# PCB_KioskMB_r3_3-04.net
KiCad netlist of a schematic drawn in EAGLE
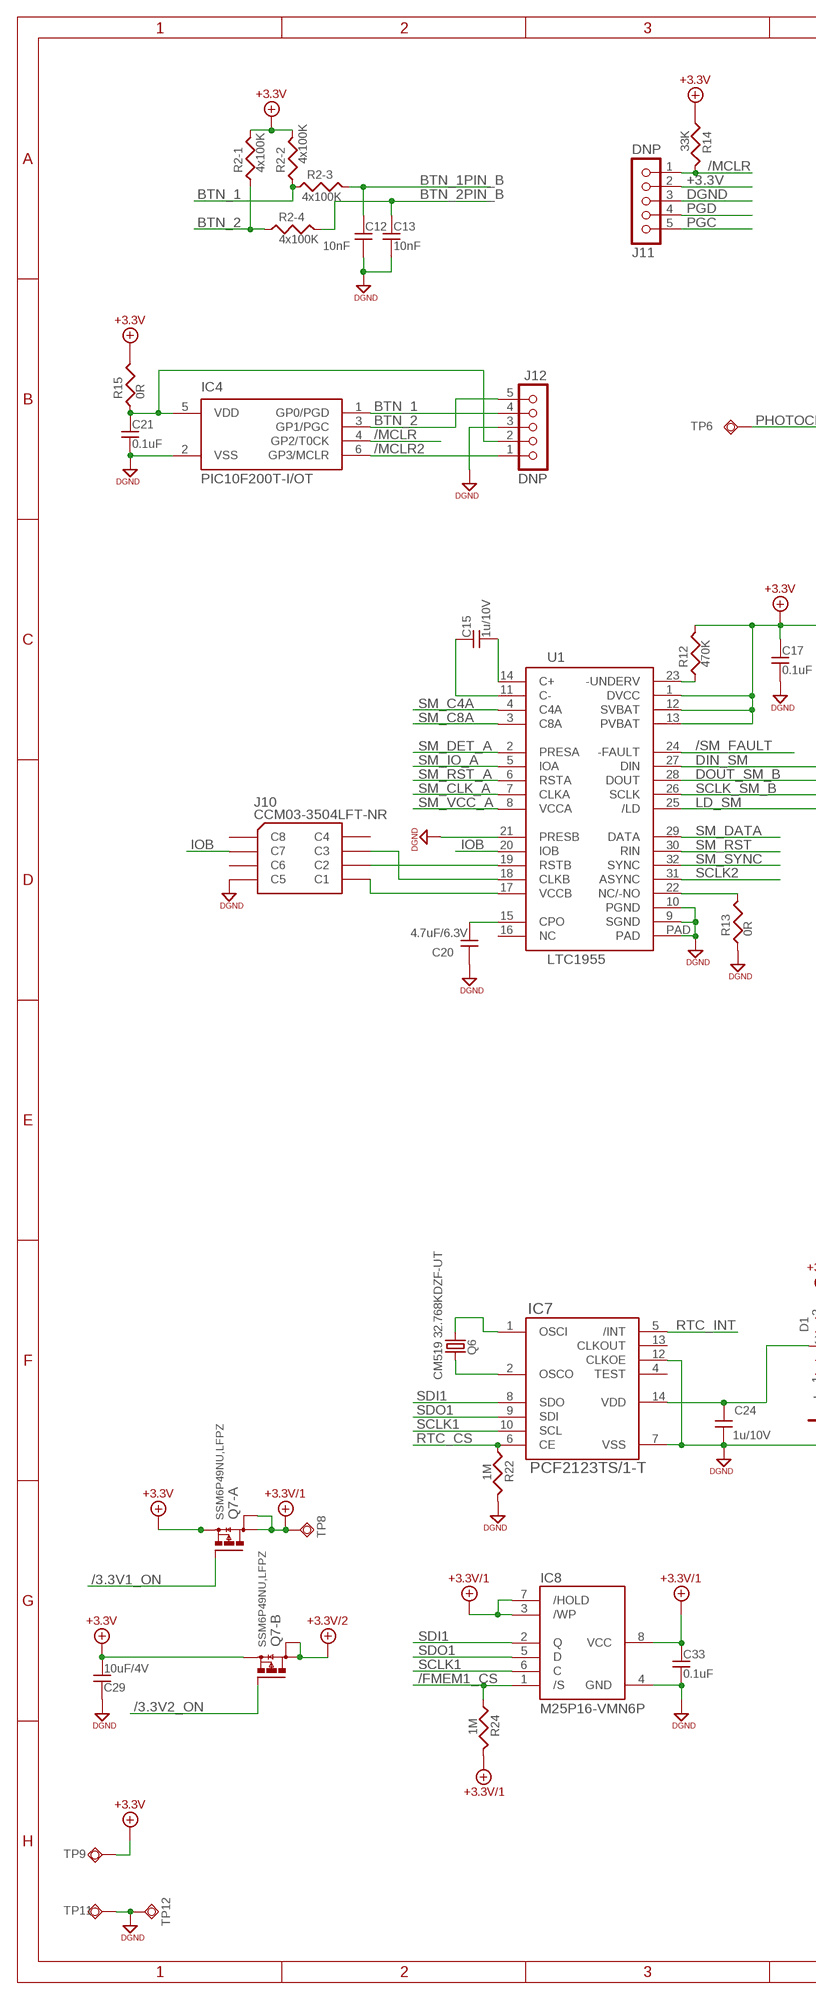
[diagram p0: schematic, sheet 1, part 1 of 2]
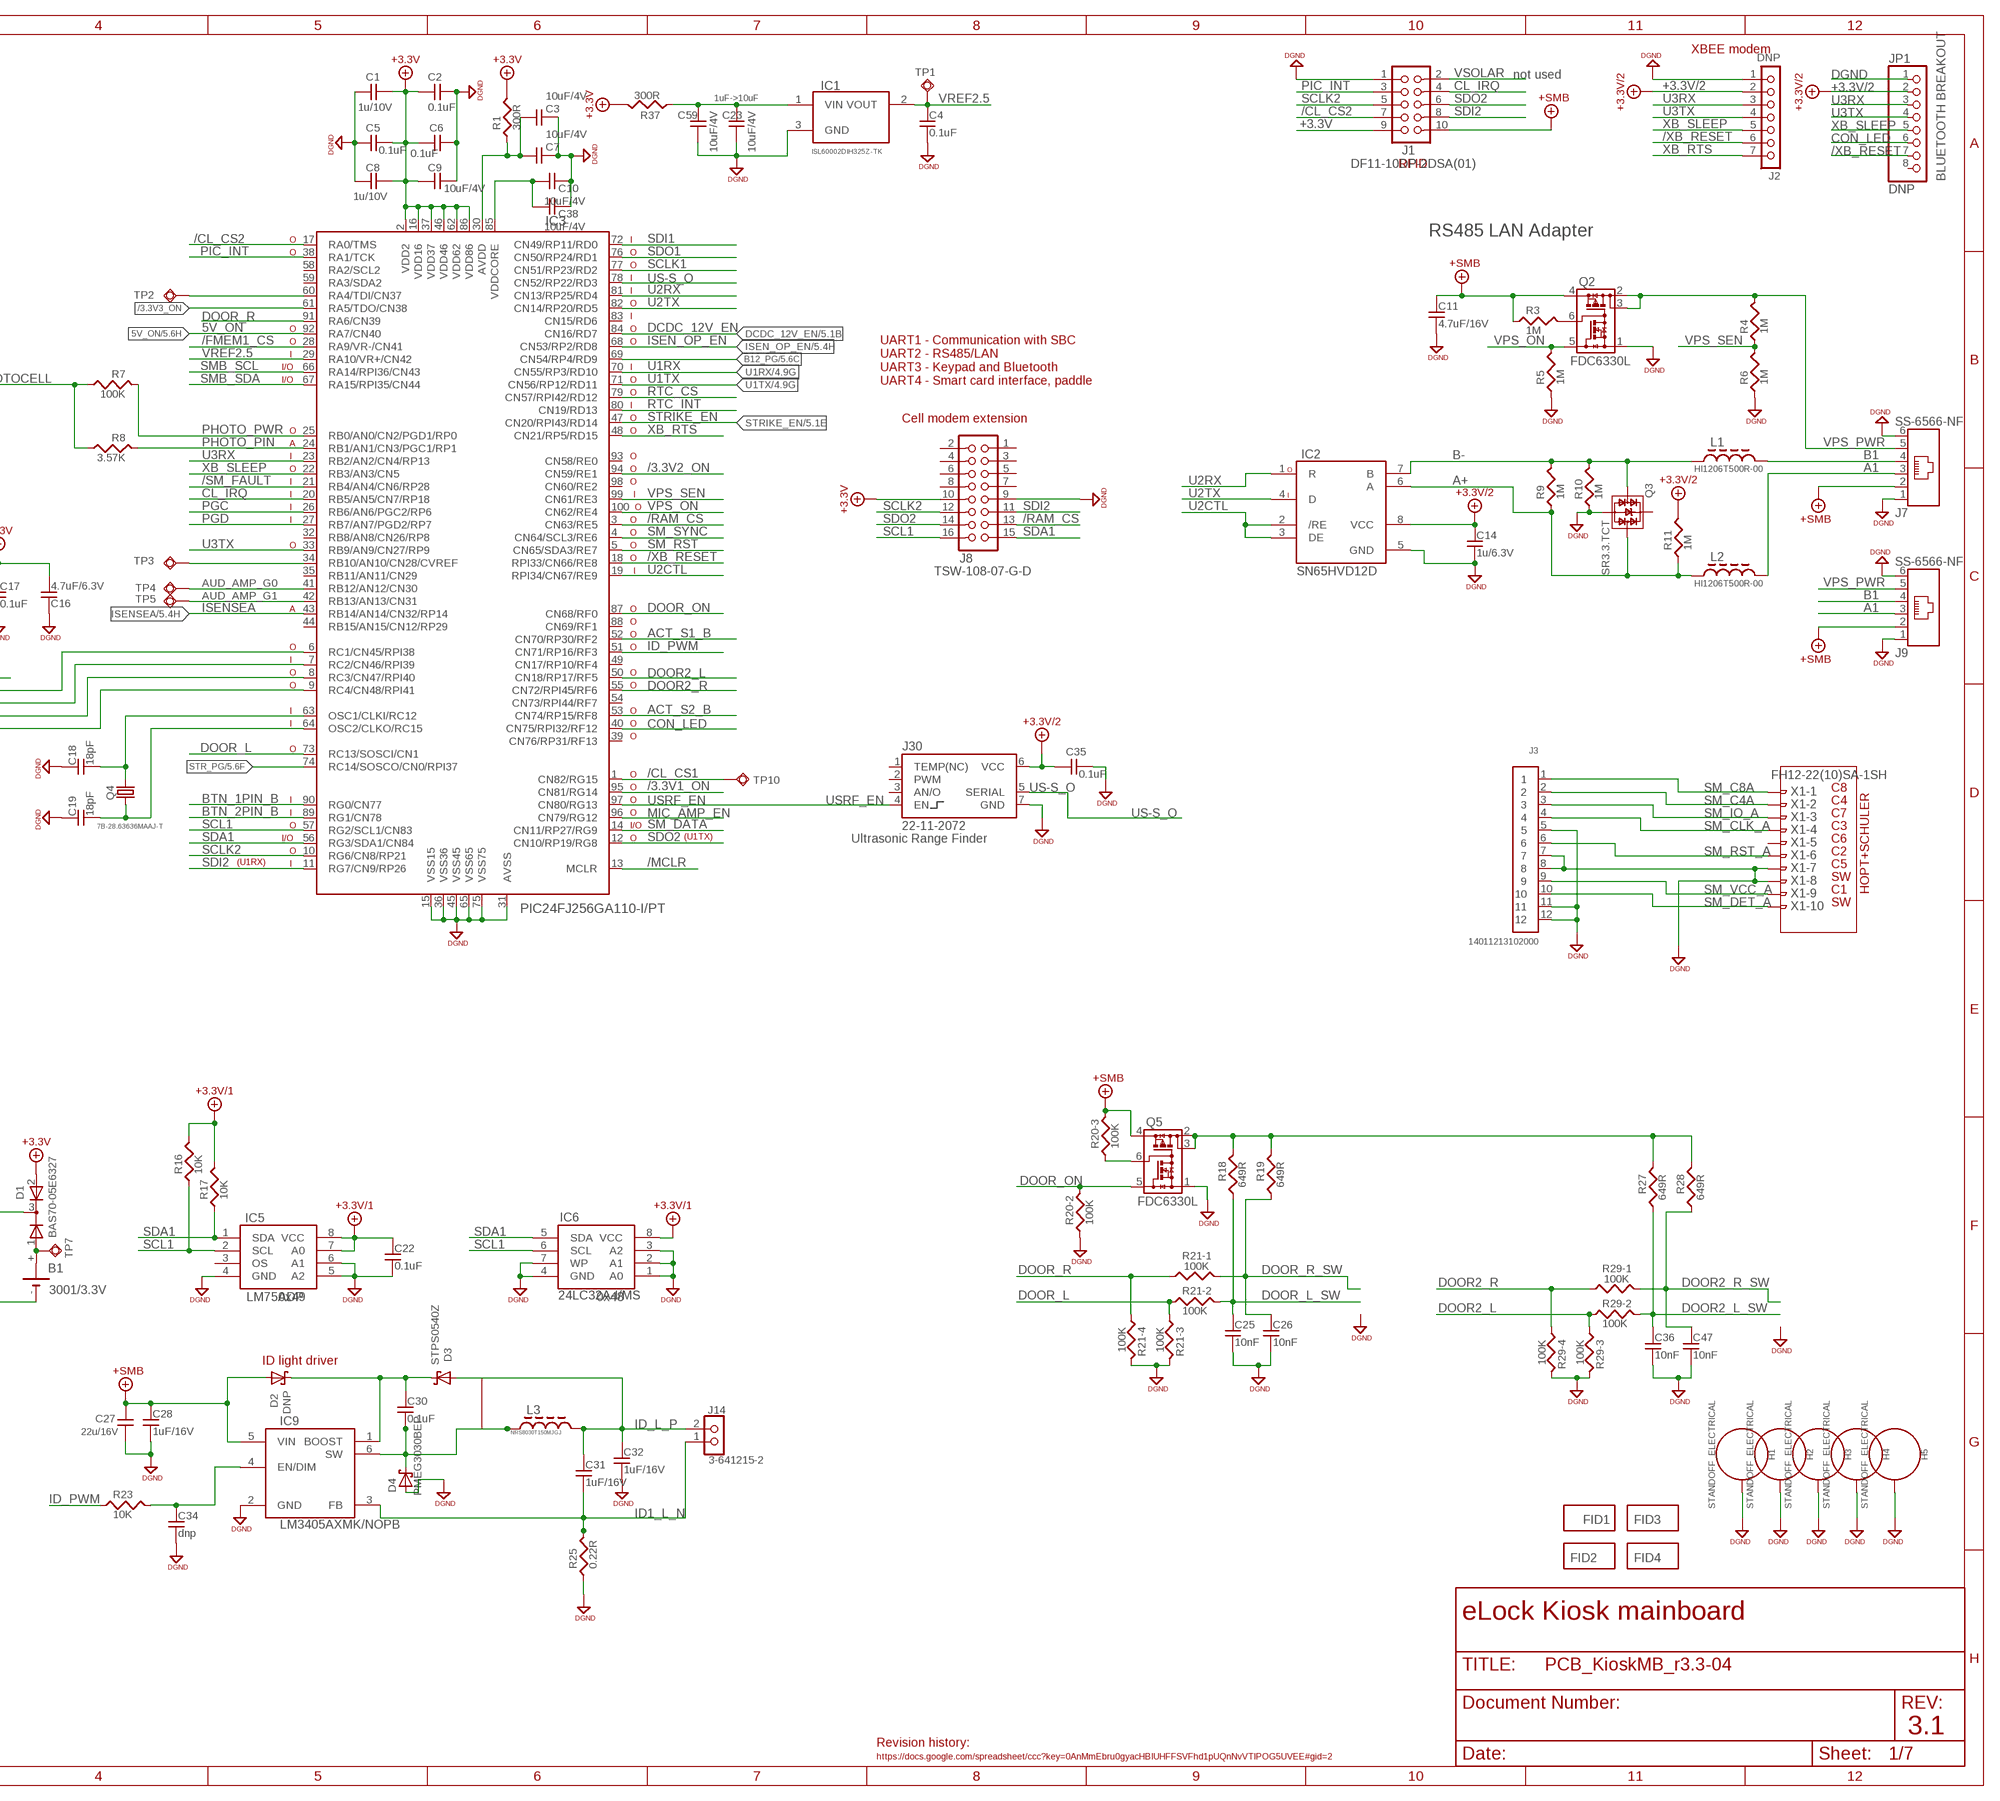
[diagram p1: schematic, sheet 1, part 2 of 2]
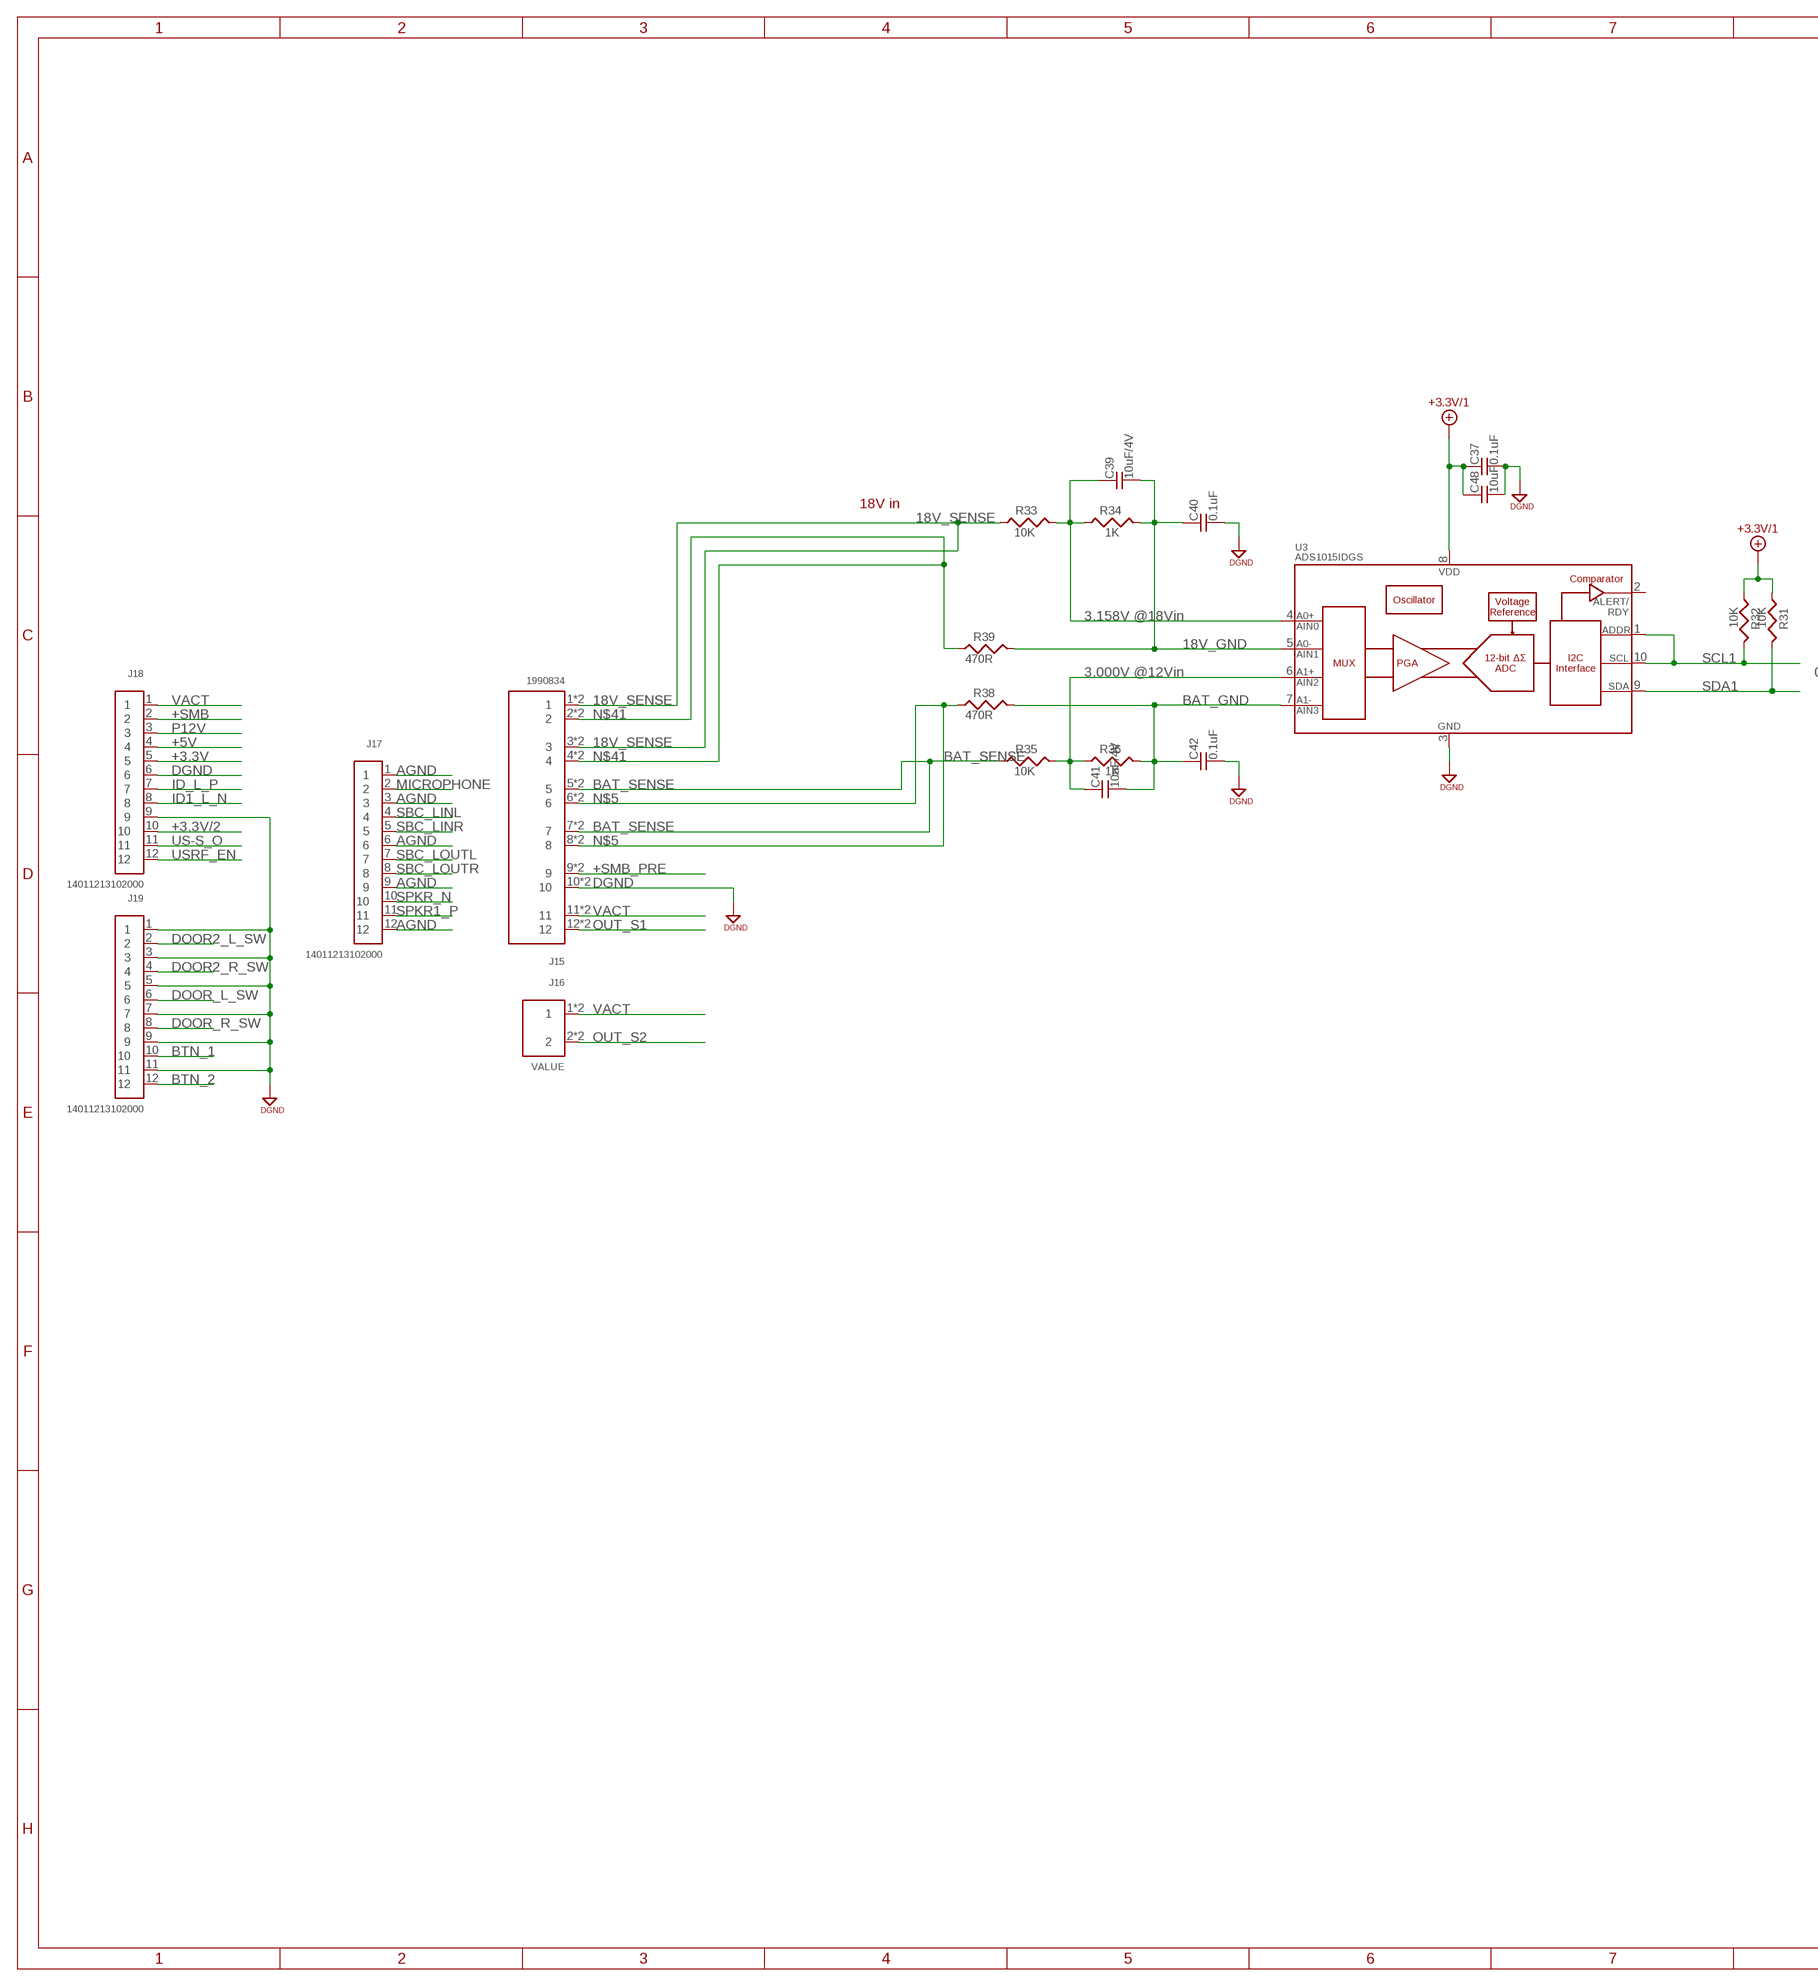
[diagram p2: schematic, sheet 2, part 1 of 2]
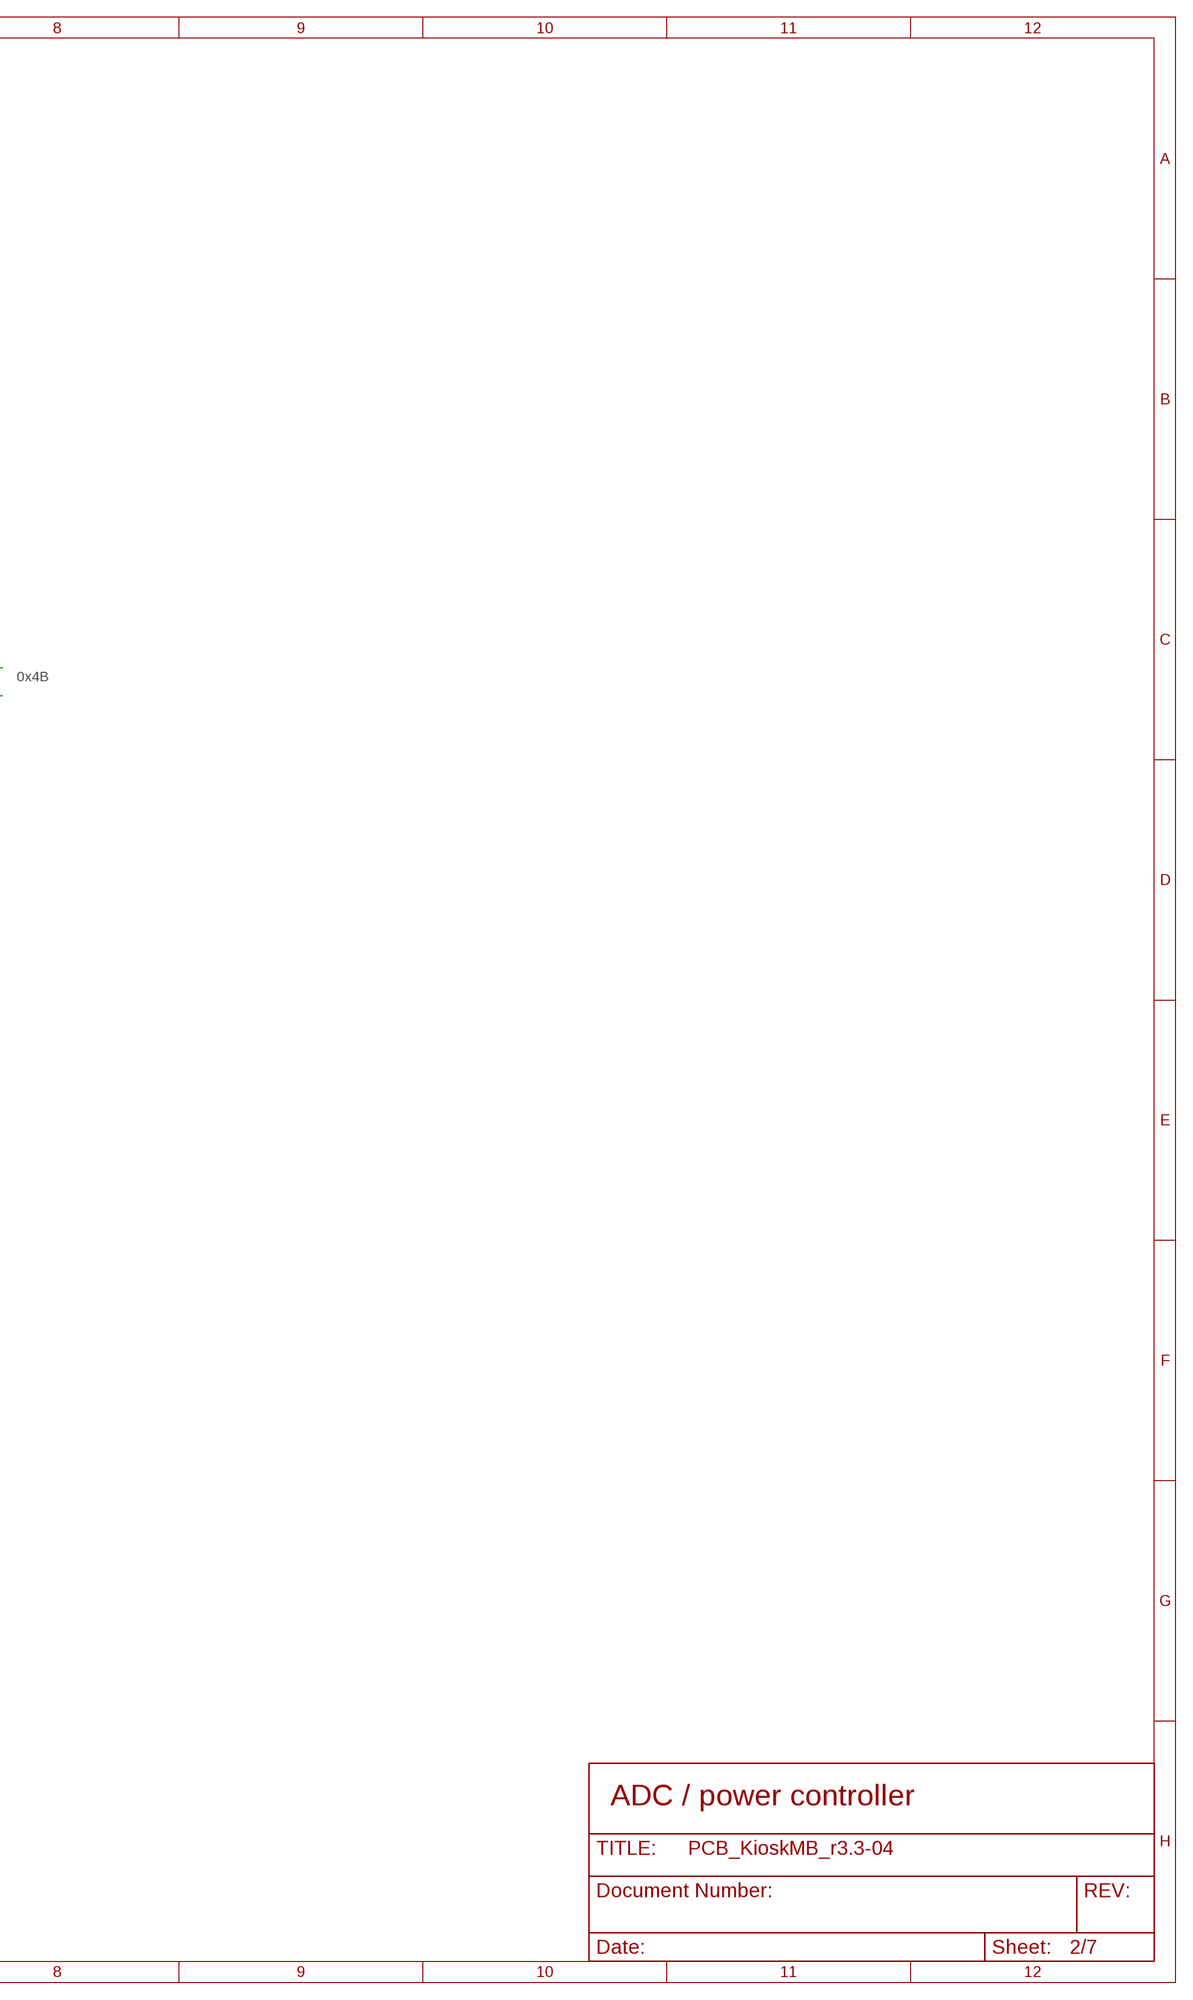
[diagram p3: schematic, sheet 2, part 2 of 2]
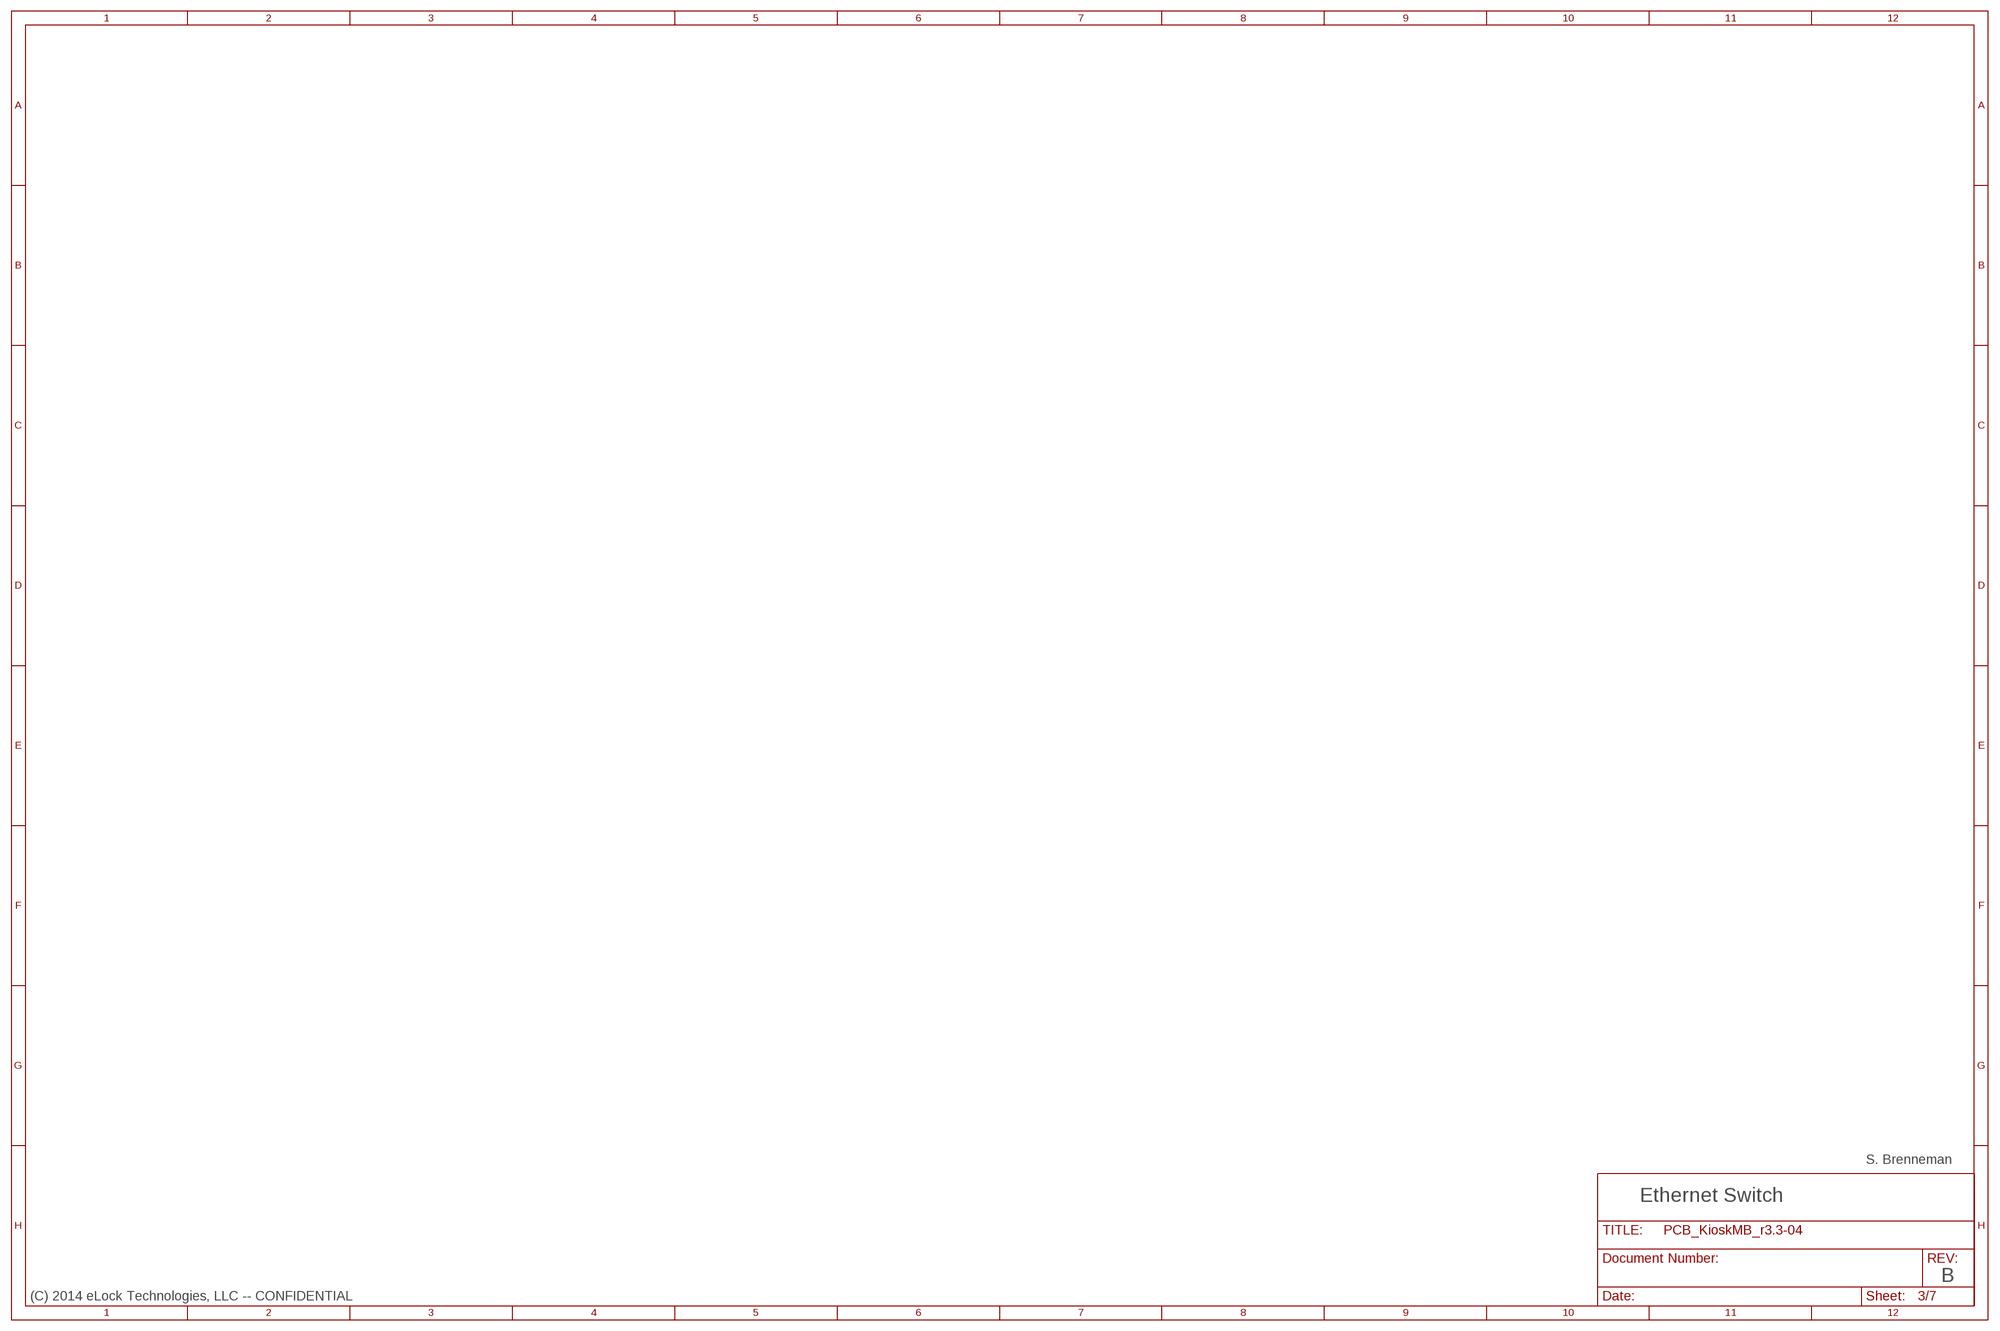
[diagram p4: schematic, sheet 3]
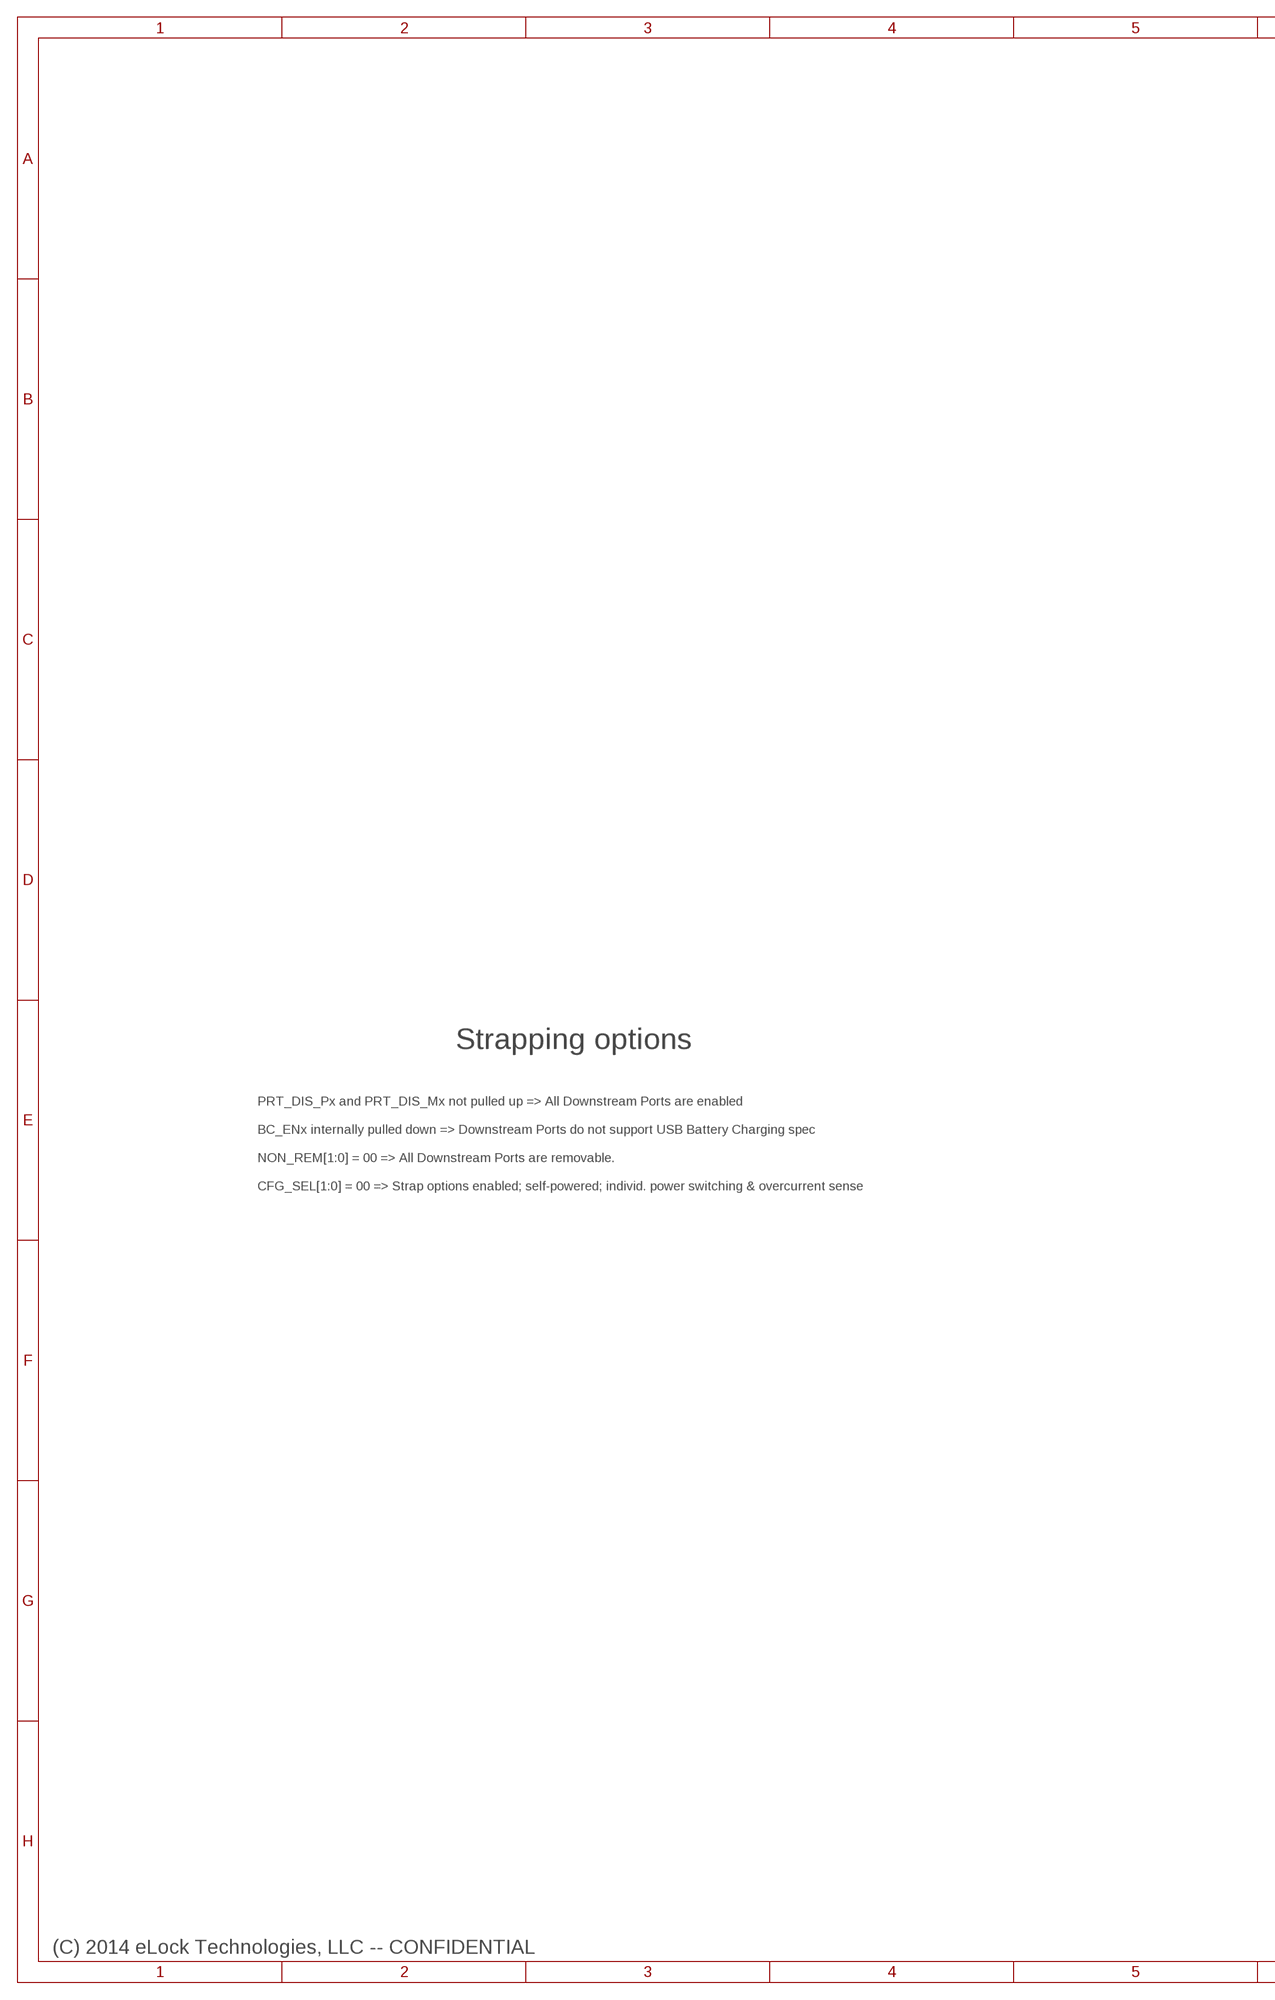
[diagram p5: schematic, sheet 4, part 1 of 2]
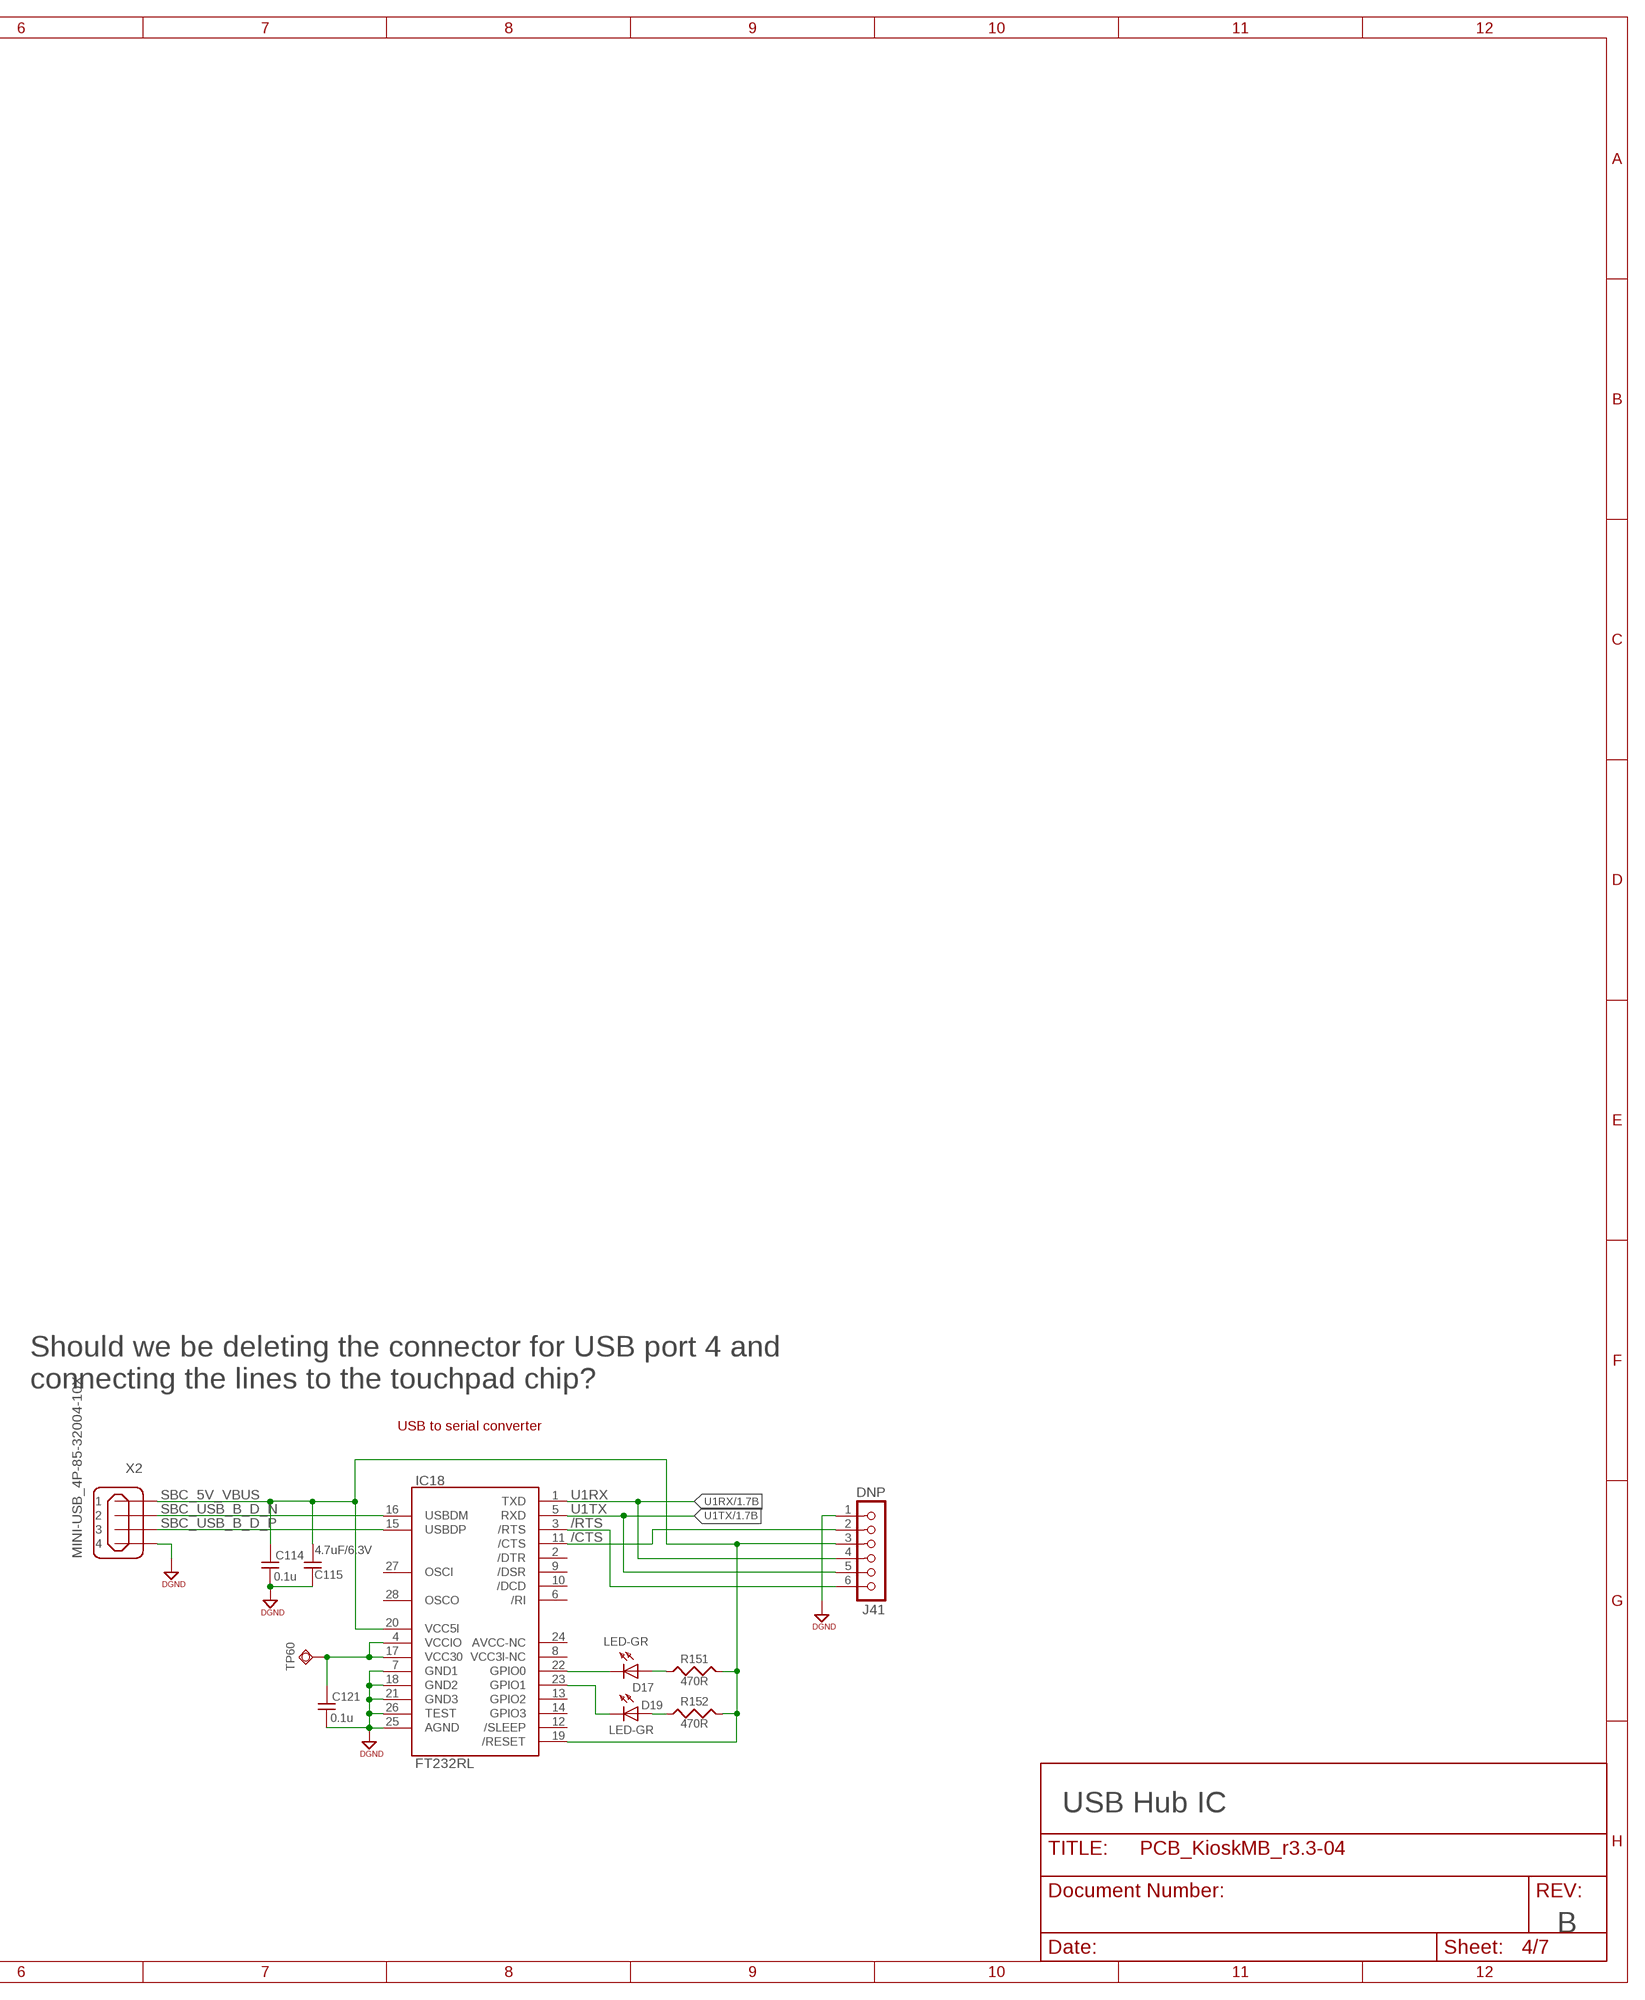
[diagram p6: schematic, sheet 4, part 2 of 2]
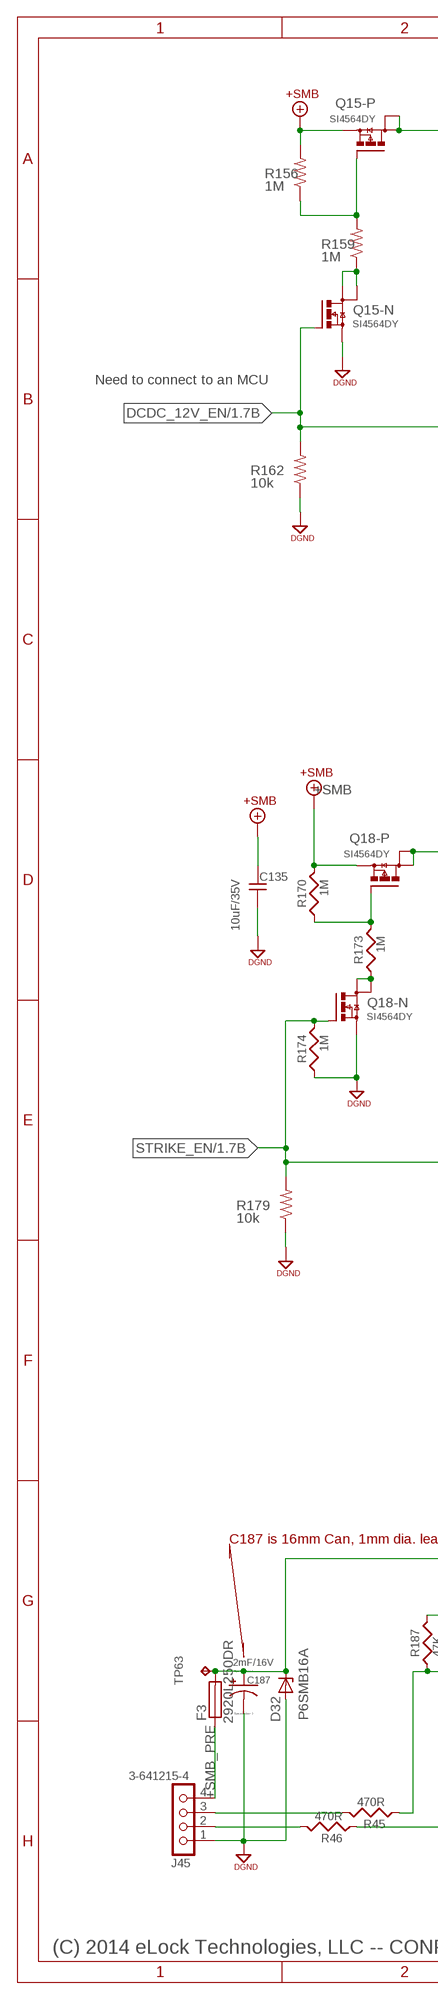
[diagram p7: schematic, sheet 5, part 1 of 2]
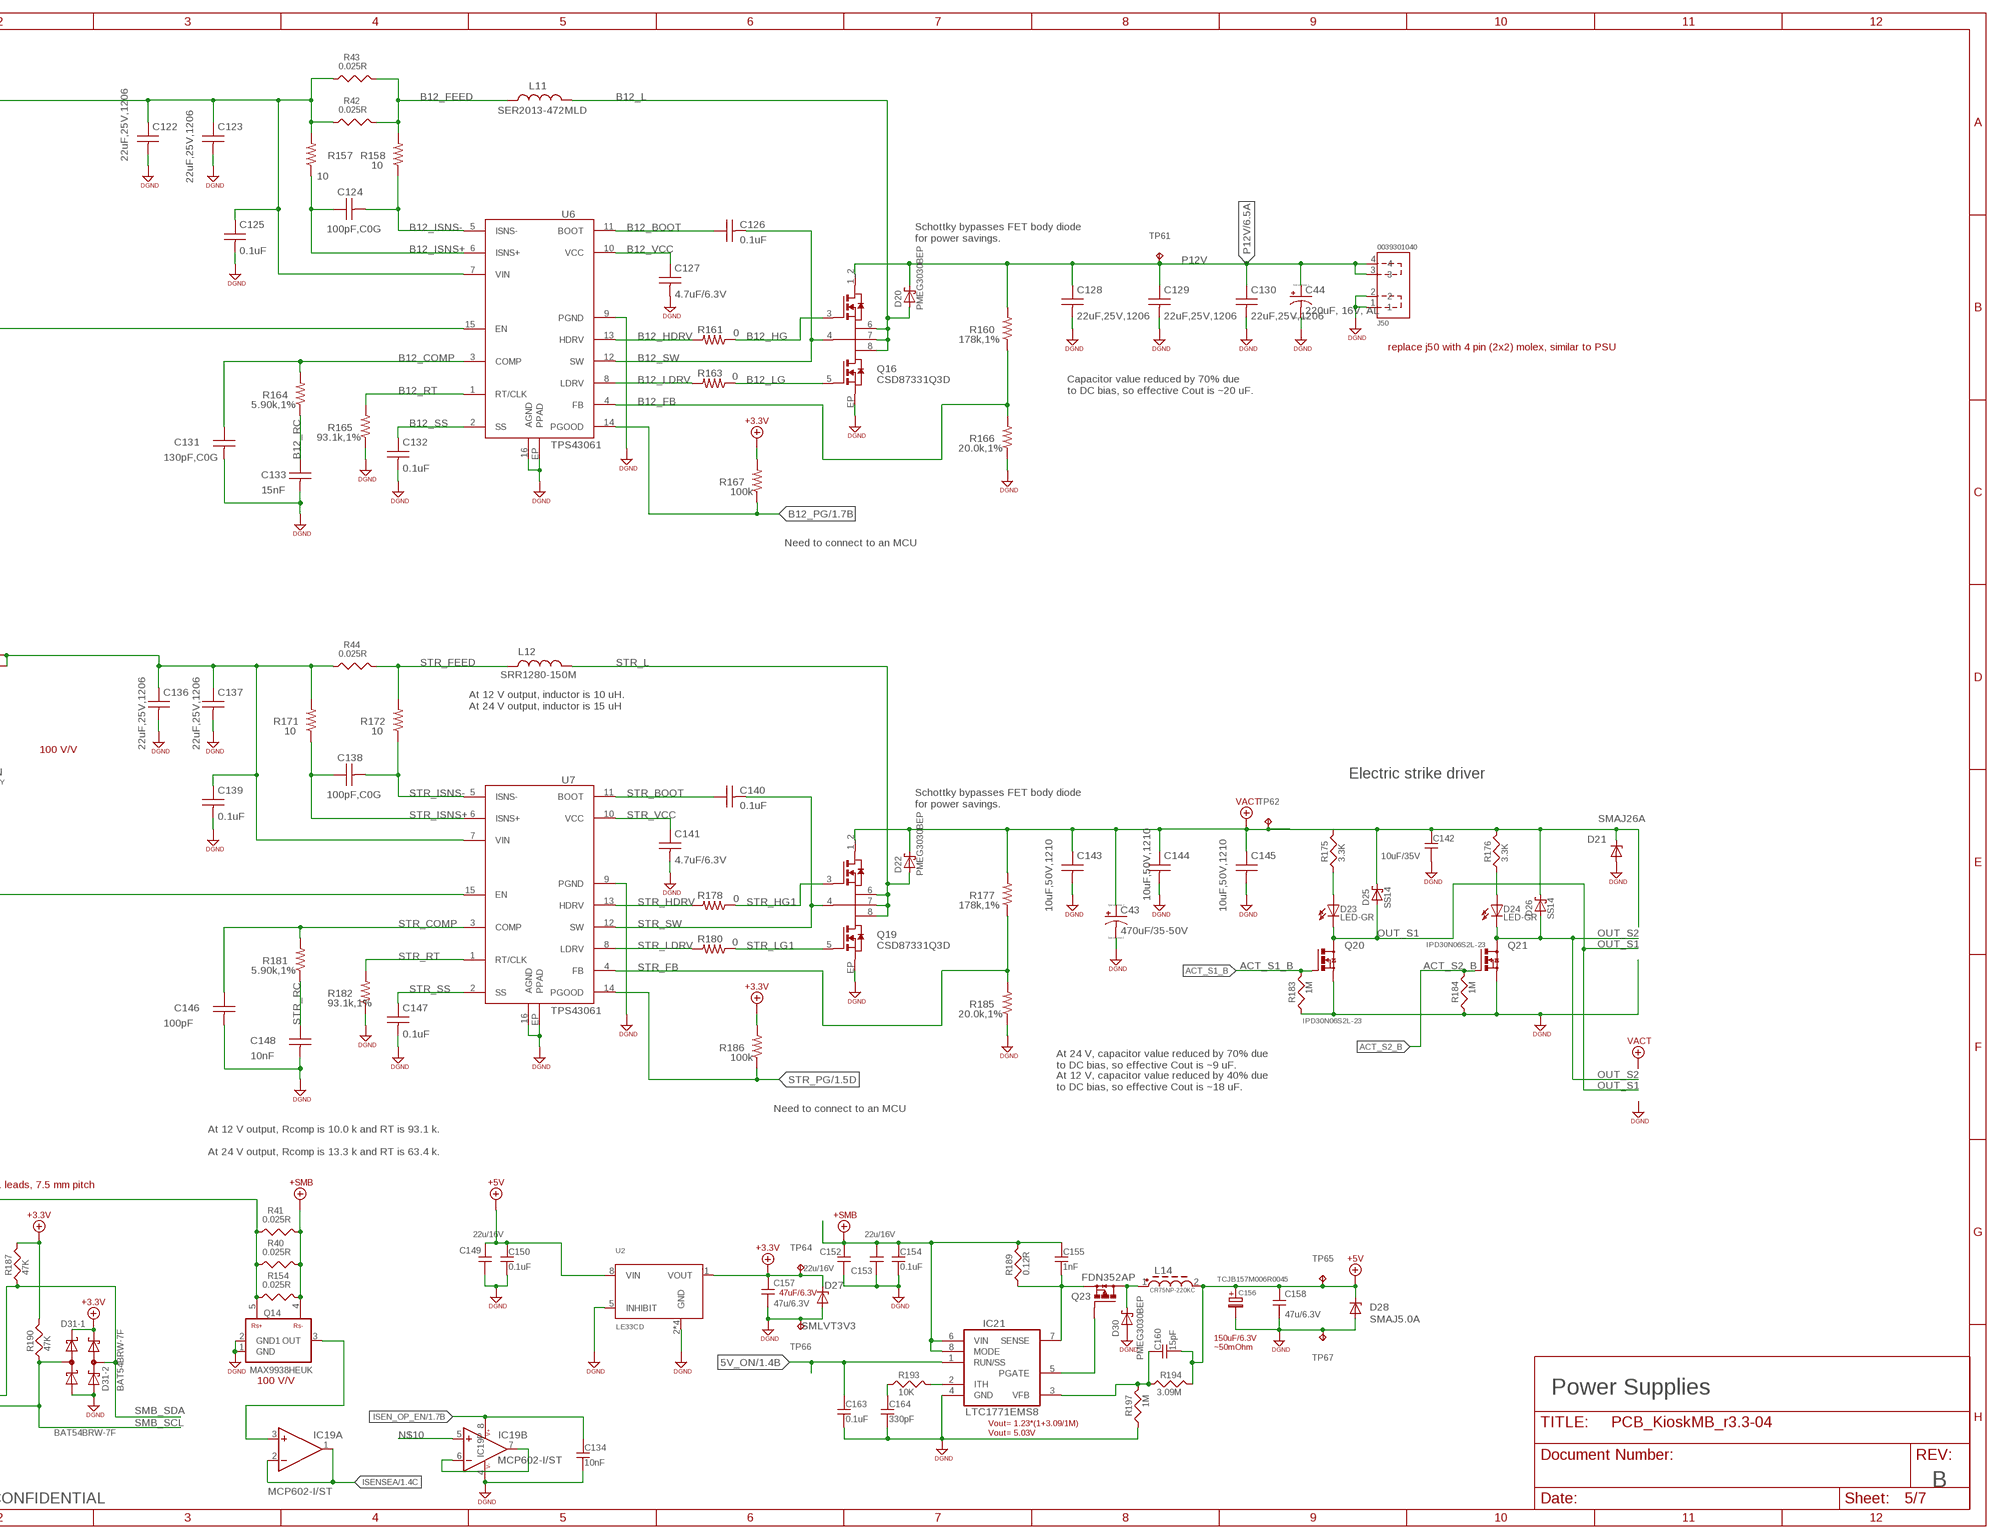
[diagram p8: schematic, sheet 5, part 2 of 2]
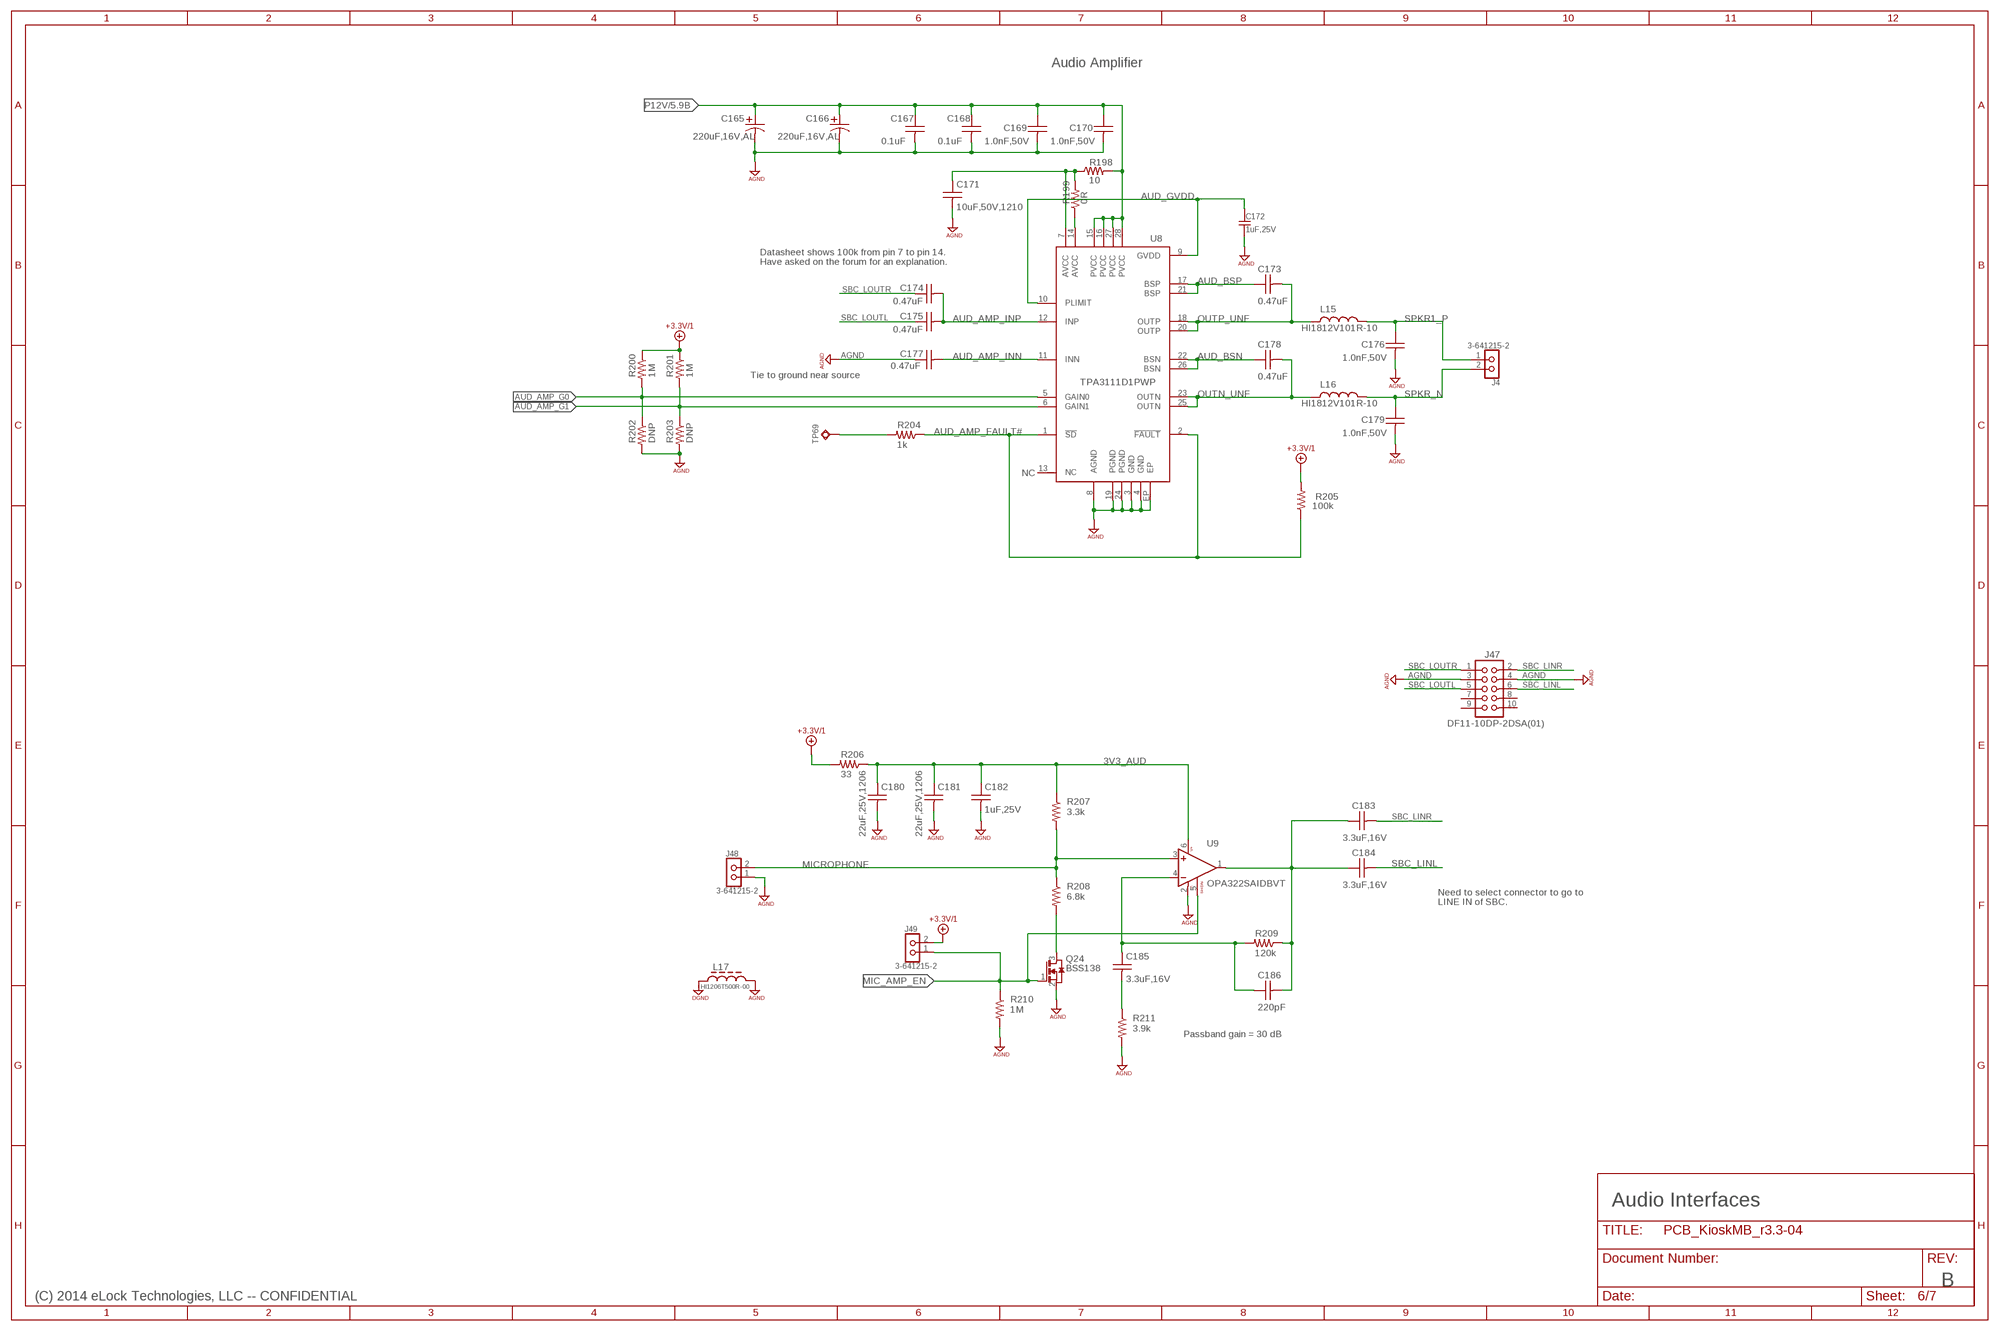
[diagram p9: schematic, sheet 6]
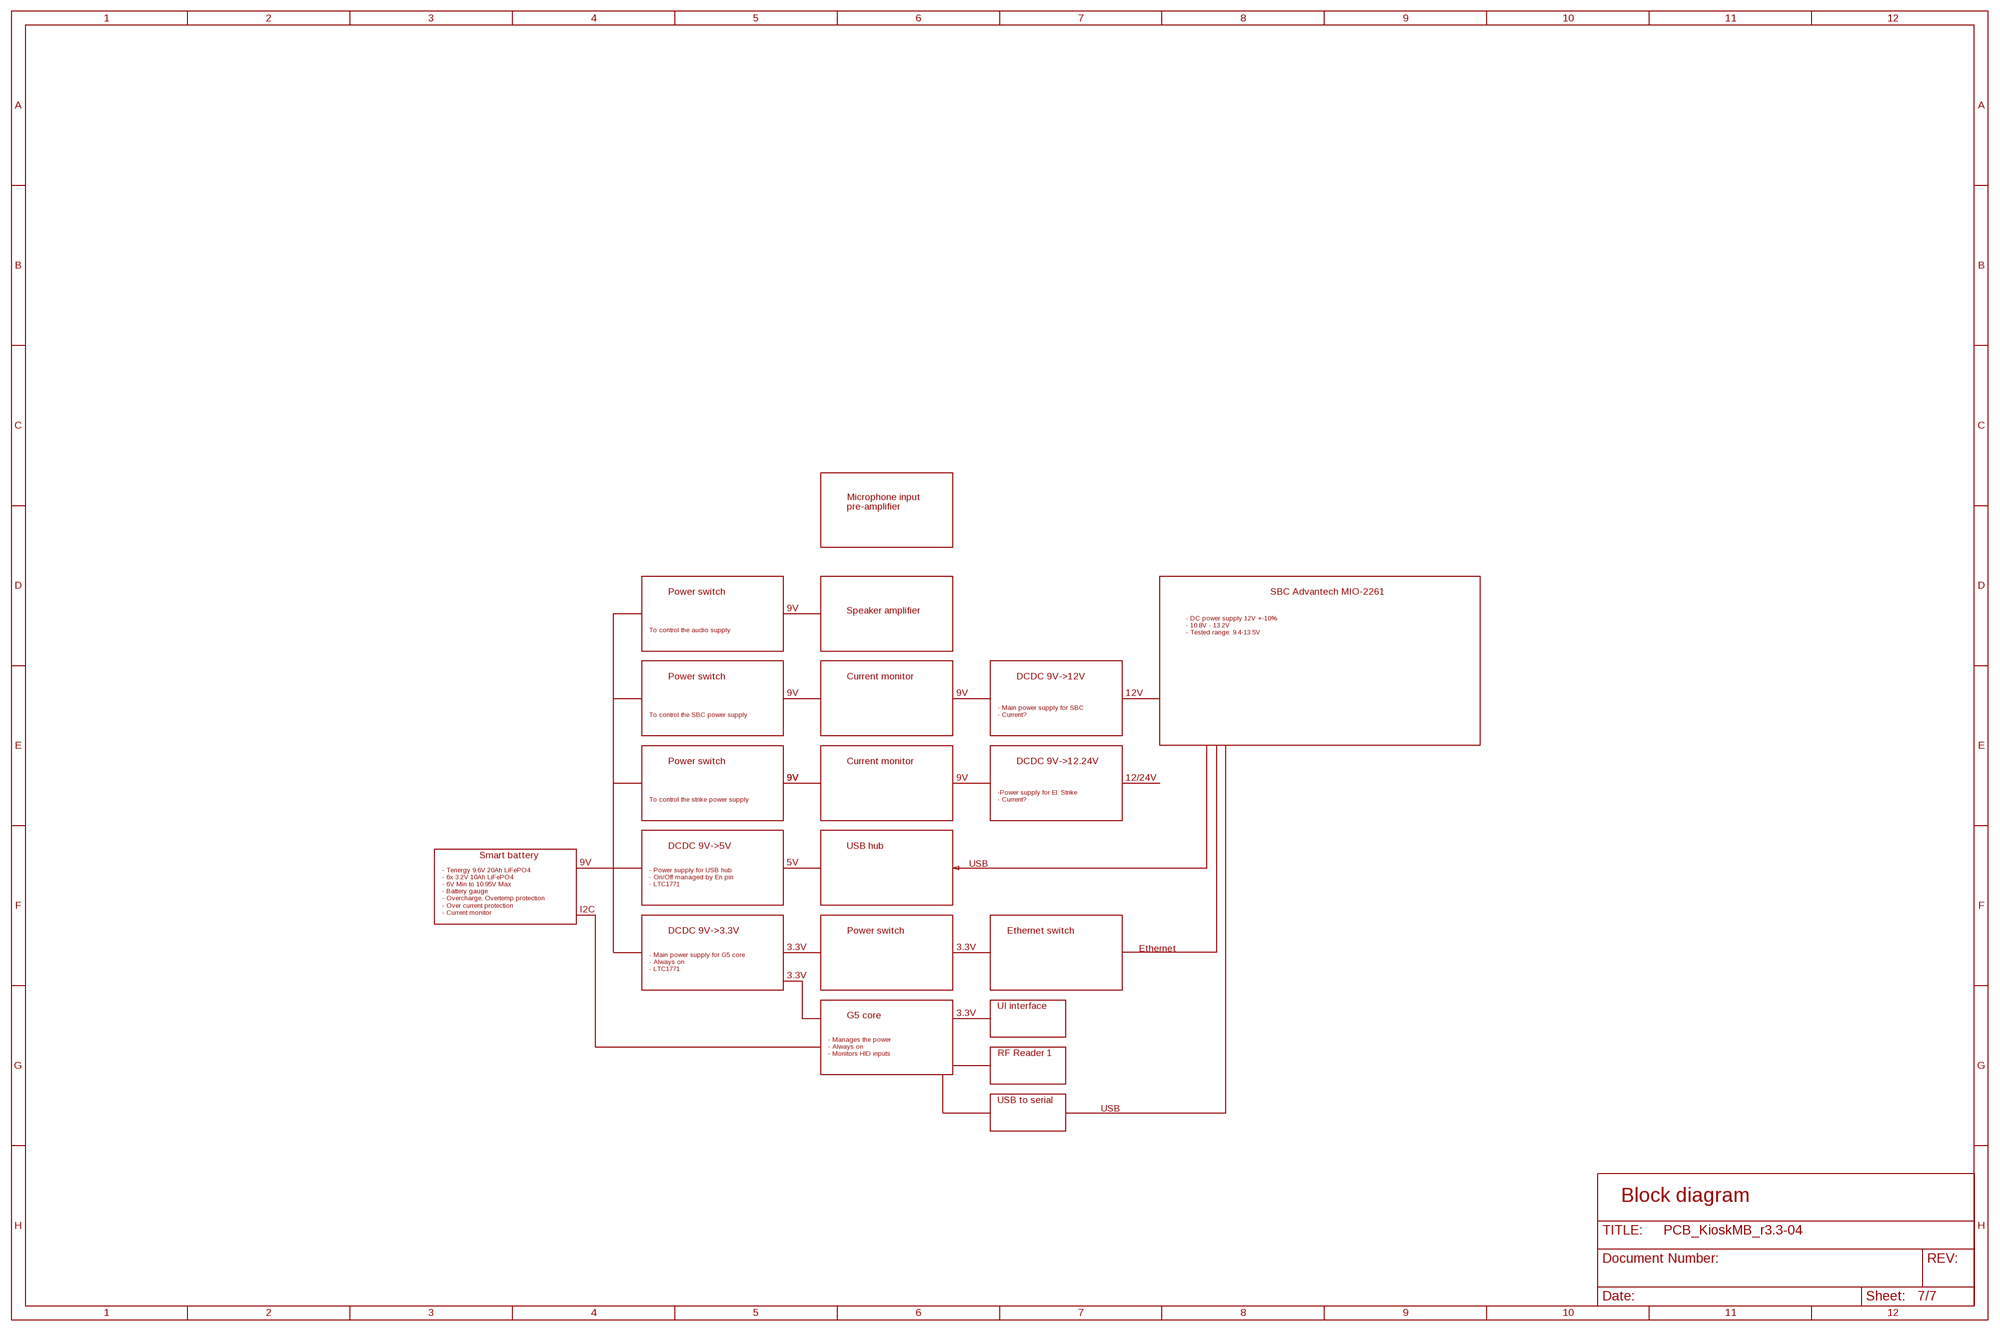
[diagram p10: schematic, sheet 7]

(export (version "E")
  (design (tool "Eeschema 10.0.6"))
  (components
    (comp (ref "C37")
      (value "0.1uF")
      (footprint "eagle-import:0603")
      (libsource (lib "eagle-import") (part "C-0603"))
    )
    (comp (ref "C39")
      (value "10uF/4V")
      (footprint "eagle-import:0603")
      (libsource (lib "eagle-import") (part "C-0603"))
    )
    (comp (ref "C40")
      (value "0.1uF")
      (footprint "eagle-import:0603")
      (libsource (lib "eagle-import") (part "C-0603"))
    )
    (comp (ref "C41")
      (value "10uF/4V")
      (footprint "eagle-import:0603")
      (libsource (lib "eagle-import") (part "C-0603"))
    )
    (comp (ref "C42")
      (value "0.1uF")
      (footprint "eagle-import:0603")
      (libsource (lib "eagle-import") (part "C-0603"))
    )
    (comp (ref "C48")
      (value "10uF")
      (footprint "eagle-import:0603")
      (libsource (lib "eagle-import") (part "C-0603"))
    )
    (comp (ref "J15")
      (value "1990834")
      (footprint "eagle-import:1990834")
      (libsource (lib "eagle-import") (part "1990834"))
    )
    (comp (ref "J16")
      (value "1990737")
      (footprint "eagle-import:1990737")
      (libsource (lib "eagle-import") (part "1990737"))
    )
    (comp (ref "J17")
      (value "14011213102000")
      (footprint "eagle-import:14011213102000")
      (libsource (lib "eagle-import") (part "14011213102000"))
    )
    (comp (ref "J18")
      (value "14011213102000")
      (footprint "eagle-import:14011213102000")
      (libsource (lib "eagle-import") (part "14011213102000"))
    )
    (comp (ref "J19")
      (value "14011213102000")
      (footprint "eagle-import:14011213102000")
      (libsource (lib "eagle-import") (part "14011213102000"))
    )
    (comp (ref "R31")
      (value "10K")
      (footprint "eagle-import:0603")
      (libsource (lib "eagle-import") (part "R-0603"))
    )
    (comp (ref "R32")
      (value "10K")
      (footprint "eagle-import:0603")
      (libsource (lib "eagle-import") (part "R-0603"))
    )
    (comp (ref "R33")
      (value "10K")
      (footprint "eagle-import:0603")
      (libsource (lib "eagle-import") (part "R-0603"))
    )
    (comp (ref "R34")
      (value "1K")
      (footprint "eagle-import:0603")
      (libsource (lib "eagle-import") (part "R-0603"))
    )
    (comp (ref "R35")
      (value "10K")
      (footprint "eagle-import:0603")
      (libsource (lib "eagle-import") (part "R-0603"))
    )
    (comp (ref "R36")
      (value "1K")
      (footprint "eagle-import:0603")
      (libsource (lib "eagle-import") (part "R-0603"))
    )
    (comp (ref "R38")
      (value "470R")
      (footprint "eagle-import:0603")
      (libsource (lib "eagle-import") (part "R-0603"))
    )
    (comp (ref "R39")
      (value "470R")
      (footprint "eagle-import:0603")
      (libsource (lib "eagle-import") (part "R-0603"))
    )
    (comp (ref "U3")
      (value "ADS1015IDGS")
      (footprint "eagle-import:MSOP10")
      (libsource (lib "eagle-import") (part "ADS1015"))
    )
    (comp (ref "B1")
      (value "3001/3.3V")
      (footprint "eagle-import:3001")
      (libsource (lib "eagle-import") (part "3001"))
    )
    (comp (ref "C1")
      (value "1u/10V")
      (footprint "eagle-import:0603")
      (libsource (lib "eagle-import") (part "C-0603"))
    )
    (comp (ref "C2")
      (value "0.1uF")
      (footprint "eagle-import:0603")
      (libsource (lib "eagle-import") (part "C-0603"))
    )
    (comp (ref "C3")
      (value "10uF/4V")
      (footprint "eagle-import:0603")
      (libsource (lib "eagle-import") (part "C-0603"))
    )
    (comp (ref "C4")
      (value "0.1uF")
      (footprint "eagle-import:0603")
      (libsource (lib "eagle-import") (part "C-0603"))
    )
    (comp (ref "C5")
      (value "0.1uF")
      (footprint "eagle-import:0603")
      (libsource (lib "eagle-import") (part "C-0603"))
    )
    (comp (ref "C6")
      (value "0.1uF")
      (footprint "eagle-import:0603")
      (libsource (lib "eagle-import") (part "C-0603"))
    )
    (comp (ref "C7")
      (value "10uF/4V")
      (footprint "eagle-import:0603")
      (libsource (lib "eagle-import") (part "C-0603"))
    )
    (comp (ref "C8")
      (value "1u/10V")
      (footprint "eagle-import:0603")
      (libsource (lib "eagle-import") (part "C-0603"))
    )
    (comp (ref "C9")
      (value "10uF/4V")
      (footprint "eagle-import:0603")
      (libsource (lib "eagle-import") (part "C-0603"))
    )
    (comp (ref "C10")
      (value "10uF/4V")
      (footprint "eagle-import:0603")
      (libsource (lib "eagle-import") (part "C-0603"))
    )
    (comp (ref "C11")
      (value "4.7uF/16V")
      (footprint "eagle-import:0805")
      (libsource (lib "eagle-import") (part "C-0805"))
    )
    (comp (ref "C12")
      (value "10nF")
      (footprint "eagle-import:0603")
      (libsource (lib "eagle-import") (part "C-0603"))
    )
    (comp (ref "C13")
      (value "10nF")
      (footprint "eagle-import:0603")
      (libsource (lib "eagle-import") (part "C-0603"))
    )
    (comp (ref "C14")
      (value "1u/6.3V")
      (footprint "eagle-import:0603")
      (libsource (lib "eagle-import") (part "C-0603"))
    )
    (comp (ref "C15")
      (value "1u/10V")
      (footprint "eagle-import:0603")
      (libsource (lib "eagle-import") (part "C-0603"))
    )
    (comp (ref "C16")
      (value "4.7uF/6.3V")
      (footprint "eagle-import:0603")
      (libsource (lib "eagle-import") (part "C-0603"))
    )
    (comp (ref "C17")
      (value "0.1uF")
      (footprint "eagle-import:0603")
      (libsource (lib "eagle-import") (part "C-0603"))
    )
    (comp (ref "C18")
      (value "18pF")
      (footprint "eagle-import:0603")
      (libsource (lib "eagle-import") (part "C-0603"))
    )
    (comp (ref "C19")
      (value "18pF")
      (footprint "eagle-import:0603")
      (libsource (lib "eagle-import") (part "C-0603"))
    )
    (comp (ref "C20")
      (value "4.7uF/6.3V")
      (footprint "eagle-import:0603")
      (libsource (lib "eagle-import") (part "C-0603"))
    )
    (comp (ref "C21")
      (value "0.1uF")
      (footprint "eagle-import:0603")
      (libsource (lib "eagle-import") (part "C-0603"))
    )
    (comp (ref "C22")
      (value "0.1uF")
      (footprint "eagle-import:0603")
      (libsource (lib "eagle-import") (part "C-0603"))
    )
    (comp (ref "C23")
      (value "10uF/4V")
      (footprint "eagle-import:0603")
      (libsource (lib "eagle-import") (part "C-0603"))
    )
    (comp (ref "C24")
      (value "1u/10V")
      (footprint "eagle-import:0603")
      (libsource (lib "eagle-import") (part "C-0603"))
    )
    (comp (ref "C25")
      (value "10nF")
      (footprint "eagle-import:0603")
      (libsource (lib "eagle-import") (part "C-0603"))
    )
    (comp (ref "C26")
      (value "10nF")
      (footprint "eagle-import:0603")
      (libsource (lib "eagle-import") (part "C-0603"))
    )
    (comp (ref "C27")
      (value "22u/16V")
      (footprint "eagle-import:1210")
      (libsource (lib "eagle-import") (part "C-1210"))
    )
    (comp (ref "C28")
      (value "1uF/16V")
      (footprint "eagle-import:0603")
      (libsource (lib "eagle-import") (part "C-0603"))
    )
    (comp (ref "C29")
      (value "10uF/4V")
      (footprint "eagle-import:0603")
      (libsource (lib "eagle-import") (part "C-0603"))
    )
    (comp (ref "C30")
      (value "0.1uF")
      (footprint "eagle-import:0603")
      (libsource (lib "eagle-import") (part "C-0603"))
    )
    (comp (ref "C31")
      (value "1uF/16V")
      (footprint "eagle-import:0603")
      (libsource (lib "eagle-import") (part "C-0603"))
    )
    (comp (ref "C32")
      (value "1uF/16V")
      (footprint "eagle-import:0603")
      (libsource (lib "eagle-import") (part "C-0603"))
    )
    (comp (ref "C33")
      (value "0.1uF")
      (footprint "eagle-import:0603")
      (libsource (lib "eagle-import") (part "C-0603"))
    )
    (comp (ref "C34")
      (value "dnp")
      (footprint "eagle-import:0603")
      (libsource (lib "eagle-import") (part "C-0603"))
    )
    (comp (ref "C35")
      (value "0.1uF")
      (footprint "eagle-import:0603")
      (libsource (lib "eagle-import") (part "C-0603"))
    )
    (comp (ref "C36")
      (value "10nF")
      (footprint "eagle-import:0603")
      (libsource (lib "eagle-import") (part "C-0603"))
    )
    (comp (ref "C38")
      (value "10uF/4V")
      (footprint "eagle-import:0603")
      (libsource (lib "eagle-import") (part "C-0603"))
    )
    (comp (ref "C47")
      (value "10nF")
      (footprint "eagle-import:0603")
      (libsource (lib "eagle-import") (part "C-0603"))
    )
    (comp (ref "C59")
      (value "10uF/4V")
      (footprint "eagle-import:0603")
      (libsource (lib "eagle-import") (part "C-0603"))
    )
    (comp (ref "D1")
      (value "BAS70-05E6327")
      (footprint "eagle-import:SOT-23")
      (libsource (lib "eagle-import") (part "BAS70-05E6327"))
    )
    (comp (ref "D2")
      (value "DNP")
      (footprint "eagle-import:SOD-123")
      (libsource (lib "eagle-import") (part "STPS0540Z"))
    )
    (comp (ref "D3")
      (value "STPS0540Z")
      (footprint "eagle-import:SOD-123")
      (libsource (lib "eagle-import") (part "STPS0540Z"))
    )
    (comp (ref "D4")
      (value "PMEG3030BEP")
      (footprint "eagle-import:SOD-128")
      (libsource (lib "eagle-import") (part "PMEG3030BEP"))
    )
    (comp (ref "FID1")
      (value "REF")
      (footprint "eagle-import:REF")
      (libsource (lib "eagle-import") (part "REF"))
    )
    (comp (ref "FID2")
      (value "REF")
      (footprint "eagle-import:REF")
      (libsource (lib "eagle-import") (part "REF"))
    )
    (comp (ref "FID3")
      (value "REF")
      (footprint "eagle-import:REF")
      (libsource (lib "eagle-import") (part "REF"))
    )
    (comp (ref "FID4")
      (value "REF")
      (footprint "eagle-import:REF")
      (libsource (lib "eagle-import") (part "REF"))
    )
    (comp (ref "H1")
      (value "STANDOFF_ELECTRICAL")
      (footprint "eagle-import:STANDOFF-ELECTRICAL")
      (libsource (lib "eagle-import") (part "STANDOFF_ELECTRICAL"))
    )
    (comp (ref "H2")
      (value "STANDOFF_ELECTRICAL")
      (footprint "eagle-import:STANDOFF-ELECTRICAL")
      (libsource (lib "eagle-import") (part "STANDOFF_ELECTRICAL"))
    )
    (comp (ref "H3")
      (value "STANDOFF_ELECTRICAL")
      (footprint "eagle-import:STANDOFF-ELECTRICAL")
      (libsource (lib "eagle-import") (part "STANDOFF_ELECTRICAL"))
    )
    (comp (ref "H4")
      (value "STANDOFF_ELECTRICAL")
      (footprint "eagle-import:STANDOFF-ELECTRICAL")
      (libsource (lib "eagle-import") (part "STANDOFF_ELECTRICAL"))
    )
    (comp (ref "H5")
      (value "STANDOFF_ELECTRICAL")
      (footprint "eagle-import:STANDOFF-ELECTRICAL")
      (libsource (lib "eagle-import") (part "STANDOFF_ELECTRICAL"))
    )
    (comp (ref "IC1")
      (value "ISL60002DIH325Z-TK")
      (footprint "eagle-import:SOT-23")
      (libsource (lib "eagle-import") (part "ISL60002DIH325Z-TK"))
    )
    (comp (ref "IC2")
      (value "SN65HVD12D")
      (footprint "eagle-import:SO08")
      (libsource (lib "eagle-import") (part "SN65HVD3082ED"))
    )
    (comp (ref "IC3")
      (value "PIC24FJ256GA110-I/PT")
      (footprint "eagle-import:SQFP-S-12X12-100")
      (libsource (lib "eagle-import") (part "PIC24FJ256GA110-I/PT"))
    )
    (comp (ref "IC4")
      (value "PIC10F200T-I/OT")
      (footprint "eagle-import:SOT23-6")
      (libsource (lib "eagle-import") (part "PIC10F200T-I/OT"))
    )
    (comp (ref "IC5")
      (value "LM75ADP")
      (footprint "eagle-import:TSSOP08-3")
      (libsource (lib "eagle-import") (part "LM75ADP"))
    )
    (comp (ref "IC6")
      (value "24LC32A-I/MS")
      (footprint "eagle-import:MSOP-08")
      (libsource (lib "eagle-import") (part "24-I/MS"))
    )
    (comp (ref "IC7")
      (value "PCF2123TS/1-T")
      (footprint "eagle-import:TSSOP014")
      (libsource (lib "eagle-import") (part "PCF2123TS/1-T"))
    )
    (comp (ref "IC8")
      (value "M25P16-VMN6P")
      (footprint "eagle-import:SO-08")
      (libsource (lib "eagle-import") (part "M25P16-VMN6P"))
    )
    (comp (ref "IC9")
      (value "LM3405AXMK/NOPB")
      (footprint "eagle-import:SOT23-6")
      (libsource (lib "eagle-import") (part "LM3405AXMK/NOPB"))
    )
    (comp (ref "J1")
      (value "DF11-10DP-2DSA(01)")
      (footprint "eagle-import:DF11-10DP-2DSA")
      (libsource (lib "eagle-import") (part "DF11-10DP-2DSA(01)"))
    )
    (comp (ref "J2")
      (value "DNP")
      (footprint "eagle-import:MA07-1")
      (libsource (lib "eagle-import") (part "MA07-1"))
    )
    (comp (ref "J3")
      (value "14011213102000")
      (footprint "eagle-import:14011213102000")
      (libsource (lib "eagle-import") (part "14011213102000"))
    )
    (comp (ref "J7")
      (value "SS-6566-NF")
      (footprint "eagle-import:SS-6566-NF")
      (libsource (lib "eagle-import") (part "SS-6566-NF"))
    )
    (comp (ref "J8")
      (value "TSW-108-07-G-D")
      (footprint "eagle-import:MA08-2")
      (libsource (lib "eagle-import") (part "MA08-2"))
    )
    (comp (ref "J9")
      (value "SS-6566-NF")
      (footprint "eagle-import:SS-6566-NF")
      (libsource (lib "eagle-import") (part "SS-6566-NF"))
    )
    (comp (ref "J10")
      (value "CCM03-3504LFT-NR")
      (footprint "eagle-import:CCM03-3504LFT-NR")
      (libsource (lib "eagle-import") (part "CCM03-3504LFT-NR"))
    )
    (comp (ref "J11")
      (value "DNP")
      (footprint "eagle-import:MA05-1")
      (libsource (lib "eagle-import") (part "MA05-1"))
    )
    (comp (ref "J12")
      (value "DNP")
      (footprint "eagle-import:MA05-1")
      (libsource (lib "eagle-import") (part "MA05-1"))
    )
    (comp (ref "J14")
      (value "3-641215-2")
      (footprint "eagle-import:3-641215-2")
      (libsource (lib "eagle-import") (part "3-641215-2"))
    )
    (comp (ref "J30")
      (value "22-11-2072")
      (footprint "eagle-import:HRXL-MAXSONAR-WRC-MB7387")
      (libsource (lib "eagle-import") (part "HRXL-MAXSONAR-WRC-MB7387"))
    )
    (comp (ref "JP1")
      (value "DNP")
      (footprint "eagle-import:1X08-LOCK")
      (libsource (lib "eagle-import") (part "PINHD-1X8LOCK"))
    )
    (comp (ref "L1")
      (value "HI1206T500R-00")
      (footprint "eagle-import:1206")
      (libsource (lib "eagle-import") (part "L-1206"))
    )
    (comp (ref "L2")
      (value "HI1206T500R-00")
      (footprint "eagle-import:1206")
      (libsource (lib "eagle-import") (part "L-1206"))
    )
    (comp (ref "L3")
      (value "NRS8030T150MJGJ")
      (footprint "eagle-import:NRS8030")
      (libsource (lib "eagle-import") (part "NRS8030T150MJGJ"))
    )
    (comp (ref "Q2")
      (value "FDC6330L")
      (footprint "eagle-import:SSOT-6")
      (libsource (lib "eagle-import") (part "FDC6330L"))
    )
    (comp (ref "Q3")
      (value "SR3.3.TCT")
      (footprint "eagle-import:SOT-143")
      (libsource (lib "eagle-import") (part "SR05.TCT"))
    )
    (comp (ref "Q4")
      (value "7B-28.63636MAAJ-T")
      (footprint "eagle-import:7B")
      (libsource (lib "eagle-import") (part "7B-27.120MAAJ-T"))
    )
    (comp (ref "Q5")
      (value "FDC6330L")
      (footprint "eagle-import:SSOT-6")
      (libsource (lib "eagle-import") (part "FDC6324L"))
    )
    (comp (ref "Q6")
      (value "CM519 32.768KDZF-UT")
      (footprint "eagle-import:CM519")
      (libsource (lib "eagle-import") (part "CM519"))
    )
    (comp (ref "Q7")
      (value "SSM6P49NU,LFPZ")
      (footprint "eagle-import:MICRO_FET")
      (libsource (lib "eagle-import") (part "SSM6P49PZNU,LF"))
    )
    (comp (ref "R1")
      (value "300R")
      (footprint "eagle-import:0603")
      (libsource (lib "eagle-import") (part "R-0603"))
    )
    (comp (ref "R2")
      (value "4x100K")
      (footprint "eagle-import:0603-ARRAY")
      (libsource (lib "eagle-import") (part "EXB-38"))
    )
    (comp (ref "R3")
      (value "1M")
      (footprint "eagle-import:0603")
      (libsource (lib "eagle-import") (part "R-0603"))
    )
    (comp (ref "R4")
      (value "1M")
      (footprint "eagle-import:0603")
      (libsource (lib "eagle-import") (part "R-0603"))
    )
    (comp (ref "R5")
      (value "1M")
      (footprint "eagle-import:0603")
      (libsource (lib "eagle-import") (part "R-0603"))
    )
    (comp (ref "R6")
      (value "1M")
      (footprint "eagle-import:0603")
      (libsource (lib "eagle-import") (part "R-0603"))
    )
    (comp (ref "R7")
      (value "100K")
      (footprint "eagle-import:0603")
      (libsource (lib "eagle-import") (part "R-0603"))
    )
    (comp (ref "R8")
      (value "3.57K")
      (footprint "eagle-import:0603")
      (libsource (lib "eagle-import") (part "R-0603"))
    )
    (comp (ref "R9")
      (value "1M")
      (footprint "eagle-import:0603")
      (libsource (lib "eagle-import") (part "R-0603"))
    )
    (comp (ref "R10")
      (value "1M")
      (footprint "eagle-import:0603")
      (libsource (lib "eagle-import") (part "R-0603"))
    )
    (comp (ref "R11")
      (value "1M")
      (footprint "eagle-import:0603")
      (libsource (lib "eagle-import") (part "R-0603"))
    )
    (comp (ref "R12")
      (value "470K")
      (footprint "eagle-import:0603-0RTOP")
      (libsource (lib "eagle-import") (part "R-0603-0RTOP"))
    )
    (comp (ref "R13")
      (value "0R")
      (footprint "eagle-import:0603-0RTOP")
      (libsource (lib "eagle-import") (part "R-0603-0RTOP"))
    )
    (comp (ref "R14")
      (value "33K")
      (footprint "eagle-import:0603")
      (libsource (lib "eagle-import") (part "R-0603"))
    )
    (comp (ref "R15")
      (value "0R")
      (footprint "eagle-import:0603-0RTOP")
      (libsource (lib "eagle-import") (part "R-0603-0RTOP"))
    )
    (comp (ref "R16")
      (value "10K")
      (footprint "eagle-import:0603-0RTOP")
      (libsource (lib "eagle-import") (part "R-0603-0RTOP"))
    )
    (comp (ref "R17")
      (value "10K")
      (footprint "eagle-import:0603-0RTOP")
      (libsource (lib "eagle-import") (part "R-0603-0RTOP"))
    )
    (comp (ref "R18")
      (value "649R")
      (footprint "eagle-import:0603")
      (libsource (lib "eagle-import") (part "R-0603"))
    )
    (comp (ref "R19")
      (value "649R")
      (footprint "eagle-import:0603")
      (libsource (lib "eagle-import") (part "R-0603"))
    )
    (comp (ref "R20")
      (value "100K")
      (footprint "eagle-import:0603-ARRAY")
      (libsource (lib "eagle-import") (part "EXB-38"))
    )
    (comp (ref "R21")
      (value "100K")
      (footprint "eagle-import:0603-ARRAY")
      (libsource (lib "eagle-import") (part "EXB-38"))
    )
    (comp (ref "R22")
      (value "1M")
      (footprint "eagle-import:0603")
      (libsource (lib "eagle-import") (part "R-0603"))
    )
    (comp (ref "R23")
      (value "10K")
      (footprint "eagle-import:0603-0RTOP")
      (libsource (lib "eagle-import") (part "R-0603-0RTOP"))
    )
    (comp (ref "R24")
      (value "1M")
      (footprint "eagle-import:0603")
      (libsource (lib "eagle-import") (part "R-0603"))
    )
    (comp (ref "R25")
      (value "0.22R")
      (footprint "eagle-import:0603-0RTOP")
      (libsource (lib "eagle-import") (part "R-0603-0RTOP"))
    )
    (comp (ref "R27")
      (value "649R")
      (footprint "eagle-import:0603")
      (libsource (lib "eagle-import") (part "R-0603"))
    )
    (comp (ref "R28")
      (value "649R")
      (footprint "eagle-import:0603")
      (libsource (lib "eagle-import") (part "R-0603"))
    )
    (comp (ref "R29")
      (value "100K")
      (footprint "eagle-import:0603-ARRAY")
      (libsource (lib "eagle-import") (part "EXB-38"))
    )
    (comp (ref "R37")
      (value "300R")
      (footprint "eagle-import:0603")
      (libsource (lib "eagle-import") (part "R-0603"))
    )
    (comp (ref "TP1")
      (value "ROUND_SMD1MM")
      (footprint "eagle-import:SMD_ROUND_1MM")
      (libsource (lib "eagle-import") (part "ROUND_SMD1MM"))
    )
    (comp (ref "TP2")
      (value "ROUND_SMD1MM")
      (footprint "eagle-import:SMD_ROUND_1MM")
      (libsource (lib "eagle-import") (part "ROUND_SMD1MM"))
    )
    (comp (ref "TP3")
      (value "ROUND_SMD1MM")
      (footprint "eagle-import:SMD_ROUND_1MM")
      (libsource (lib "eagle-import") (part "ROUND_SMD1MM"))
    )
    (comp (ref "TP4")
      (value "ROUND_SMD1MM")
      (footprint "eagle-import:SMD_ROUND_1MM")
      (libsource (lib "eagle-import") (part "ROUND_SMD1MM"))
    )
    (comp (ref "TP5")
      (value "ROUND_SMD1MM")
      (footprint "eagle-import:SMD_ROUND_1MM")
      (libsource (lib "eagle-import") (part "ROUND_SMD1MM"))
    )
    (comp (ref "TP6")
      (value "ROUND_SMD1MM")
      (footprint "eagle-import:SMD_ROUND_1MM")
      (libsource (lib "eagle-import") (part "ROUND_SMD1MM"))
    )
    (comp (ref "TP7")
      (value "ROUND_SMD1MM")
      (footprint "eagle-import:SMD_ROUND_1MM")
      (libsource (lib "eagle-import") (part "ROUND_SMD1MM"))
    )
    (comp (ref "TP8")
      (value "ROUND_SMD1MM")
      (footprint "eagle-import:SMD_ROUND_1MM")
      (libsource (lib "eagle-import") (part "ROUND_SMD1MM"))
    )
    (comp (ref "TP9")
      (value "ROUND_SMD0.7MM")
      (footprint "eagle-import:SMD_ROUND_07MM")
      (libsource (lib "eagle-import") (part "ROUND_SMD0.7MM"))
    )
    (comp (ref "TP10")
      (value "ROUND_SMD1MM")
      (footprint "eagle-import:SMD_ROUND_1MM")
      (libsource (lib "eagle-import") (part "ROUND_SMD1MM"))
    )
    (comp (ref "TP11")
      (value "ROUND_SMD0.7MM")
      (footprint "eagle-import:SMD_ROUND_07MM")
      (libsource (lib "eagle-import") (part "ROUND_SMD0.7MM"))
    )
    (comp (ref "TP12")
      (value "TP_0812")
      (footprint "eagle-import:TP_0.8_1.2")
      (libsource (lib "eagle-import") (part "TP_0812"))
    )
    (comp (ref "U1")
      (value "LTC1955")
      (footprint "eagle-import:LFCSP_5X5_032")
      (libsource (lib "eagle-import") (part "LTC1955"))
    )
    (comp (ref "X1")
      (value "FH12-22(10)SA-1SH")
      (footprint "eagle-import:CON-FPC-1.0MM-10POS")
      (libsource (lib "eagle-import") (part "FH12-10S-0.5S1.00MM"))
    )
    (comp (ref "C165")
      (value "220uF,16V,AL")
      (footprint "eagle-import:CAP_6.3MM_DIA_SMT")
      (fields (field (name "MANUFACTURER") "Kemet") (field (name "MFR_PN") "EEV227M016A9HAA"))
      (libsource (lib "eagle-import") (part "CAP_ELEC_6.3MM_SMD"))
    )
    (comp (ref "C166")
      (value "220uF,16V,AL")
      (footprint "eagle-import:CAP_6.3MM_DIA_SMT")
      (fields (field (name "MANUFACTURER") "Kemet") (field (name "MFR_PN") "EEV227M016A9HAA"))
      (libsource (lib "eagle-import") (part "CAP_ELEC_6.3MM_SMD"))
    )
    (comp (ref "C167")
      (value "0.1uF")
      (footprint "eagle-import:C0603")
      (libsource (lib "eagle-import") (part "C-US-NP0603"))
    )
    (comp (ref "C168")
      (value "0.1uF")
      (footprint "eagle-import:C0603")
      (libsource (lib "eagle-import") (part "C-US-NP0603"))
    )
    (comp (ref "C169")
      (value "1.0nF,50V")
      (footprint "eagle-import:C0603")
      (fields (field (name "MANUFACTURER") "Samsung"))
      (libsource (lib "eagle-import") (part "C-US-NP0603"))
    )
    (comp (ref "C170")
      (value "1.0nF,50V")
      (footprint "eagle-import:C0603")
      (fields (field (name "MANUFACTURER") "Samsung"))
      (libsource (lib "eagle-import") (part "C-US-NP0603"))
    )
    (comp (ref "C171")
      (value "10uF,50V,1210")
      (footprint "eagle-import:C1210")
      (fields (field (name "MANUFACTURER") "Samsung"))
      (libsource (lib "eagle-import") (part "C-US-NP1210"))
    )
    (comp (ref "C172")
      (value "1uF,25V")
      (footprint "eagle-import:0603")
      (libsource (lib "eagle-import") (part "C-0603"))
    )
    (comp (ref "C173")
      (value "0.47uF")
      (footprint "eagle-import:C0603")
      (fields (field (name "MANUFACTURER") "Taiyo Yuden"))
      (libsource (lib "eagle-import") (part "C-US-NP0603"))
    )
    (comp (ref "C174")
      (value "0.47uF")
      (footprint "eagle-import:C0603")
      (fields (field (name "MANUFACTURER") "Samsung"))
      (libsource (lib "eagle-import") (part "C-US-NP0603"))
    )
    (comp (ref "C175")
      (value "0.47uF")
      (footprint "eagle-import:C0603")
      (fields (field (name "MANUFACTURER") "Samsung"))
      (libsource (lib "eagle-import") (part "C-US-NP0603"))
    )
    (comp (ref "C176")
      (value "1.0nF,50V")
      (footprint "eagle-import:C0603")
      (fields (field (name "MANUFACTURER") "Samsung"))
      (libsource (lib "eagle-import") (part "C-US-NP0603"))
    )
    (comp (ref "C177")
      (value "0.47uF")
      (footprint "eagle-import:C0603")
      (fields (field (name "MANUFACTURER") "Samsung"))
      (libsource (lib "eagle-import") (part "C-US-NP0603"))
    )
    (comp (ref "C178")
      (value "0.47uF")
      (footprint "eagle-import:C0603")
      (fields (field (name "MANUFACTURER") "Taiyo Yuden"))
      (libsource (lib "eagle-import") (part "C-US-NP0603"))
    )
    (comp (ref "C179")
      (value "1.0nF,50V")
      (footprint "eagle-import:C0603")
      (fields (field (name "MANUFACTURER") "Samsung"))
      (libsource (lib "eagle-import") (part "C-US-NP0603"))
    )
    (comp (ref "C180")
      (value "22uF,25V,1206")
      (footprint "eagle-import:C1206")
      (fields (field (name "MANUFACTURER") "Samsung"))
      (libsource (lib "eagle-import") (part "C-US-NP1206"))
    )
    (comp (ref "C181")
      (value "22uF,25V,1206")
      (footprint "eagle-import:C1206")
      (fields (field (name "MANUFACTURER") "Samsung"))
      (libsource (lib "eagle-import") (part "C-US-NP1206"))
    )
    (comp (ref "C182")
      (value "1uF,25V")
      (footprint "eagle-import:C0603")
      (libsource (lib "eagle-import") (part "C-US-NP0603"))
    )
    (comp (ref "C183")
      (value "3.3uF,16V")
      (footprint "eagle-import:C0603")
      (libsource (lib "eagle-import") (part "C-US-NP0603"))
    )
    (comp (ref "C184")
      (value "3.3uF,16V")
      (footprint "eagle-import:C0603")
      (libsource (lib "eagle-import") (part "C-US-NP0603"))
    )
    (comp (ref "C185")
      (value "3.3uF,16V")
      (footprint "eagle-import:C0603")
      (libsource (lib "eagle-import") (part "C-US-NP0603"))
    )
    (comp (ref "C186")
      (value "220pF")
      (footprint "eagle-import:C0603")
      (libsource (lib "eagle-import") (part "C-US-NP0603"))
    )
    (comp (ref "J4")
      (value "3-641215-2")
      (footprint "eagle-import:3-641215-2")
      (libsource (lib "eagle-import") (part "3-641215-2"))
    )
    (comp (ref "J47")
      (value "DF11-10DP-2DSA(01)")
      (footprint "eagle-import:DF11-10DP-2DSA")
      (libsource (lib "eagle-import") (part "DF11-10DP-2DSA(01)"))
    )
    (comp (ref "J48")
      (value "3-641215-2")
      (footprint "eagle-import:3-641215-2")
      (libsource (lib "eagle-import") (part "3-641215-2"))
    )
    (comp (ref "J49")
      (value "3-641215-2")
      (footprint "eagle-import:3-641215-2")
      (libsource (lib "eagle-import") (part "3-641215-2"))
    )
    (comp (ref "L15")
      (value "HI1812V101R-10")
      (footprint "eagle-import:L1812")
      (fields (field (name "MANUFACTURER") "Laird") (field (name "MFR_PN") "HI1812V101R-10"))
      (libsource (lib "eagle-import") (part "L1812"))
    )
    (comp (ref "L16")
      (value "HI1812V101R-10")
      (footprint "eagle-import:L1812")
      (fields (field (name "MANUFACTURER") "Laird") (field (name "MFR_PN") "HI1812V101R-10"))
      (libsource (lib "eagle-import") (part "L1812"))
    )
    (comp (ref "L17")
      (value "HI1206T500R-00")
      (footprint "eagle-import:1206")
      (libsource (lib "eagle-import") (part "L-1206"))
    )
    (comp (ref "Q24")
      (value "BSS138")
      (footprint "eagle-import:SOT23")
      (libsource (lib "eagle-import") (part "BSS138"))
    )
    (comp (ref "R198")
      (value "10")
      (footprint "eagle-import:R0603")
      (fields (field (name "MANUFACTURER") "Rohm"))
      (libsource (lib "eagle-import") (part "R-US_R0603"))
    )
    (comp (ref "R199")
      (value "0R")
      (footprint "eagle-import:R0603")
      (fields (field (name "MANUFACTURER") "Rohm"))
      (libsource (lib "eagle-import") (part "R-US_R0603"))
    )
    (comp (ref "R200")
      (value "1M")
      (footprint "eagle-import:R0603")
      (libsource (lib "eagle-import") (part "R-US_R0603"))
    )
    (comp (ref "R201")
      (value "1M")
      (footprint "eagle-import:R0603")
      (libsource (lib "eagle-import") (part "R-US_R0603"))
    )
    (comp (ref "R202")
      (value "DNP")
      (footprint "eagle-import:R0603")
      (libsource (lib "eagle-import") (part "R-US_R0603"))
    )
    (comp (ref "R203")
      (value "DNP")
      (footprint "eagle-import:R0603")
      (libsource (lib "eagle-import") (part "R-US_R0603"))
    )
    (comp (ref "R204")
      (value "1k")
      (footprint "eagle-import:R0603")
      (libsource (lib "eagle-import") (part "R-US_R0603"))
    )
    (comp (ref "R205")
      (value "100k")
      (footprint "eagle-import:R0603")
      (libsource (lib "eagle-import") (part "R-US_R0603"))
    )
    (comp (ref "R206")
      (value "33")
      (footprint "eagle-import:R0603")
      (libsource (lib "eagle-import") (part "R-US_R0603"))
    )
    (comp (ref "R207")
      (value "3.3k")
      (footprint "eagle-import:R0603")
      (libsource (lib "eagle-import") (part "R-US_R0603"))
    )
    (comp (ref "R208")
      (value "6.8k")
      (footprint "eagle-import:R0603")
      (libsource (lib "eagle-import") (part "R-US_R0603"))
    )
    (comp (ref "R209")
      (value "120k")
      (footprint "eagle-import:R0603")
      (libsource (lib "eagle-import") (part "R-US_R0603"))
    )
    (comp (ref "R210")
      (value "1M")
      (footprint "eagle-import:R0603")
      (libsource (lib "eagle-import") (part "R-US_R0603"))
    )
    (comp (ref "R211")
      (value "3.9k")
      (footprint "eagle-import:R0603")
      (libsource (lib "eagle-import") (part "R-US_R0603"))
    )
    (comp (ref "TP69")
      (value "P1-13")
      (footprint "eagle-import:P1-13@1")
      (libsource (lib "eagle-import") (part "P1-13"))
    )
    (comp (ref "U8")
      (value "TPA3111D1PWP")
      (footprint "eagle-import:TSSOP28_EP")
      (fields (field (name "MANUFACTURER") "TI"))
      (libsource (lib "eagle-import") (part "IC_TI_TPA3111D1PWP"))
    )
    (comp (ref "U9")
      (value "OPA322SAIDBVT")
      (footprint "eagle-import:SOT23-6")
      (fields (field (name "MANUFACTURER") "TI"))
      (libsource (lib "eagle-import") (part "IC_TI_OPA322SDBVAI"))
    )
    (comp (ref "C43")
      (value "470uF/35-50V")
      (footprint "eagle-import:E5-13")
      (libsource (lib "eagle-import") (part "CPOL-USE5-13"))
    )
    (comp (ref "C44")
      (value "220uF, 16V, AL")
      (footprint "eagle-import:153CLV-0605")
      (libsource (lib "eagle-import") (part "CPOL-US153CLV-0605"))
    )
    (comp (ref "C122")
      (value "22uF,25V,1206")
      (footprint "eagle-import:C1206")
      (fields (field (name "MANUFACTURER") "Samsung"))
      (libsource (lib "eagle-import") (part "C-US-NP1206"))
    )
    (comp (ref "C123")
      (value "22uF,25V,1206")
      (footprint "eagle-import:C1206")
      (fields (field (name "MANUFACTURER") "Samsung"))
      (libsource (lib "eagle-import") (part "C-US-NP1206"))
    )
    (comp (ref "C124")
      (value "100pF,C0G")
      (footprint "eagle-import:C0603")
      (fields (field (name "MANUFACTURER") "Samsung"))
      (libsource (lib "eagle-import") (part "C-US-NP0603"))
    )
    (comp (ref "C125")
      (value "0.1uF")
      (footprint "eagle-import:C0603")
      (fields (field (name "MANUFACTURER") "Murata"))
      (libsource (lib "eagle-import") (part "C-US-NP0603"))
    )
    (comp (ref "C126")
      (value "0.1uF")
      (footprint "eagle-import:C0603")
      (fields (field (name "MANUFACTURER") "Murata"))
      (libsource (lib "eagle-import") (part "C-US-NP0603"))
    )
    (comp (ref "C127")
      (value "4.7uF/6.3V")
      (footprint "eagle-import:C0603")
      (fields (field (name "MANUFACTURER") "Samsung"))
      (libsource (lib "eagle-import") (part "C-US-NP0603"))
    )
    (comp (ref "C128")
      (value "22uF,25V,1206")
      (footprint "eagle-import:C1206")
      (fields (field (name "MANUFACTURER") "Samsung"))
      (libsource (lib "eagle-import") (part "C-US-NP1206"))
    )
    (comp (ref "C129")
      (value "22uF,25V,1206")
      (footprint "eagle-import:C1206")
      (fields (field (name "MANUFACTURER") "Samsung"))
      (libsource (lib "eagle-import") (part "C-US-NP1206"))
    )
    (comp (ref "C130")
      (value "22uF,25V,1206")
      (footprint "eagle-import:C1206")
      (fields (field (name "MANUFACTURER") "Samsung"))
      (libsource (lib "eagle-import") (part "C-US-NP1206"))
    )
    (comp (ref "C131")
      (value "130pF,C0G")
      (footprint "eagle-import:C0603")
      (fields (field (name "MANUFACTURER") "Samsung"))
      (libsource (lib "eagle-import") (part "C-US-NP0603"))
    )
    (comp (ref "C132")
      (value "0.1uF")
      (footprint "eagle-import:C0603")
      (fields (field (name "MANUFACTURER") "Murata"))
      (libsource (lib "eagle-import") (part "C-US-NP0603"))
    )
    (comp (ref "C133")
      (value "15nF")
      (footprint "eagle-import:C0603")
      (fields (field (name "MANUFACTURER") "Samsung"))
      (libsource (lib "eagle-import") (part "C-US-NP0603"))
    )
    (comp (ref "C134")
      (value "10nF")
      (footprint "eagle-import:0603")
      (libsource (lib "eagle-import") (part "C-0603"))
    )
    (comp (ref "C135")
      (value "10uF/35V")
      (footprint "eagle-import:1206")
      (libsource (lib "eagle-import") (part "C-1206"))
    )
    (comp (ref "C136")
      (value "22uF,25V,1206")
      (footprint "eagle-import:C1206")
      (fields (field (name "MANUFACTURER") "Samsung"))
      (libsource (lib "eagle-import") (part "C-US-NP1206"))
    )
    (comp (ref "C137")
      (value "22uF,25V,1206")
      (footprint "eagle-import:C1206")
      (fields (field (name "MANUFACTURER") "Samsung"))
      (libsource (lib "eagle-import") (part "C-US-NP1206"))
    )
    (comp (ref "C138")
      (value "100pF,C0G")
      (footprint "eagle-import:C0603")
      (fields (field (name "MANUFACTURER") "Samsung"))
      (libsource (lib "eagle-import") (part "C-US-NP0603"))
    )
    (comp (ref "C139")
      (value "0.1uF")
      (footprint "eagle-import:C0603")
      (fields (field (name "MANUFACTURER") "Murata"))
      (libsource (lib "eagle-import") (part "C-US-NP0603"))
    )
    (comp (ref "C140")
      (value "0.1uF")
      (footprint "eagle-import:C0603")
      (fields (field (name "MANUFACTURER") "Murata"))
      (libsource (lib "eagle-import") (part "C-US-NP0603"))
    )
    (comp (ref "C141")
      (value "4.7uF/6.3V")
      (footprint "eagle-import:C0603")
      (fields (field (name "MANUFACTURER") "Samsung"))
      (libsource (lib "eagle-import") (part "C-US-NP0603"))
    )
    (comp (ref "C142")
      (value "10uF/35V")
      (footprint "eagle-import:1206")
      (libsource (lib "eagle-import") (part "C-1206"))
    )
    (comp (ref "C143")
      (value "10uF,50V,1210")
      (footprint "eagle-import:C1210")
      (fields (field (name "MANUFACTURER") "Samsung"))
      (libsource (lib "eagle-import") (part "C-US-NP1210"))
    )
    (comp (ref "C144")
      (value "10uF,50V,1210")
      (footprint "eagle-import:C1210")
      (fields (field (name "MANUFACTURER") "Samsung"))
      (libsource (lib "eagle-import") (part "C-US-NP1210"))
    )
    (comp (ref "C145")
      (value "10uF,50V,1210")
      (footprint "eagle-import:C1210")
      (fields (field (name "MANUFACTURER") "Samsung"))
      (libsource (lib "eagle-import") (part "C-US-NP1210"))
    )
    (comp (ref "C146")
      (value "100pF")
      (footprint "eagle-import:C0603")
      (fields (field (name "MANUFACTURER") "Samsung"))
      (libsource (lib "eagle-import") (part "C-US-NP0603"))
    )
    (comp (ref "C147")
      (value "0.1uF")
      (footprint "eagle-import:C0603")
      (fields (field (name "MANUFACTURER") "Murata"))
      (libsource (lib "eagle-import") (part "C-US-NP0603"))
    )
    (comp (ref "C148")
      (value "10nF")
      (footprint "eagle-import:C0603")
      (fields (field (name "MANUFACTURER") "Samsung"))
      (libsource (lib "eagle-import") (part "C-US-NP0603"))
    )
    (comp (ref "C149")
      (value "22u/16V")
      (footprint "eagle-import:1210")
      (libsource (lib "eagle-import") (part "C-1210"))
    )
    (comp (ref "C150")
      (value "0.1uF")
      (footprint "eagle-import:0603")
      (libsource (lib "eagle-import") (part "C-0603"))
    )
    (comp (ref "C152")
      (value "22u/16V")
      (footprint "eagle-import:1210")
      (libsource (lib "eagle-import") (part "C-1210"))
    )
    (comp (ref "C153")
      (value "22u/16V")
      (footprint "eagle-import:1210")
      (libsource (lib "eagle-import") (part "C-1210"))
    )
    (comp (ref "C154")
      (value "0.1uF")
      (footprint "eagle-import:0603")
      (libsource (lib "eagle-import") (part "C-0603"))
    )
    (comp (ref "C155")
      (value "1nF")
      (footprint "eagle-import:0603")
      (libsource (lib "eagle-import") (part "C-0603"))
    )
    (comp (ref "C156")
      (value "TCJB157M006R0045")
      (footprint "eagle-import:3528-POL")
      (libsource (lib "eagle-import") (part "C-POL-3528"))
    )
    (comp (ref "C157")
      (value "47u/6.3V")
      (footprint "eagle-import:1210")
      (libsource (lib "eagle-import") (part "C-1210"))
    )
    (comp (ref "C158")
      (value "47u/6.3V")
      (footprint "eagle-import:1210")
      (libsource (lib "eagle-import") (part "C-1210"))
    )
    (comp (ref "C160")
      (value "15pF")
      (footprint "eagle-import:0603")
      (libsource (lib "eagle-import") (part "C-0603"))
    )
    (comp (ref "C163")
      (value "0.1uF")
      (footprint "eagle-import:0603")
      (libsource (lib "eagle-import") (part "C-0603"))
    )
    (comp (ref "C164")
      (value "330pF")
      (footprint "eagle-import:0603")
      (libsource (lib "eagle-import") (part "C-0603"))
    )
    (comp (ref "C187")
      (value "2mF/16V")
      (footprint "eagle-import:E7,5-18")
      (libsource (lib "eagle-import") (part "CPOL-USE7.5-18"))
    )
    (comp (ref "D20")
      (value "PMEG3030BEP")
      (footprint "eagle-import:SOD-128")
      (libsource (lib "eagle-import") (part "PMEG3030BEP"))
    )
    (comp (ref "D21")
      (value "SMAJ26A")
      (footprint "eagle-import:SMA")
      (libsource (lib "eagle-import") (part "SMAJ5.0A"))
    )
    (comp (ref "D22")
      (value "PMEG3030BEP")
      (footprint "eagle-import:SOD-128")
      (libsource (lib "eagle-import") (part "PMEG3030BEP"))
    )
    (comp (ref "D23")
      (value "LED-GR")
      (footprint "eagle-import:0805-POL")
      (libsource (lib "eagle-import") (part "LED-0805"))
    )
    (comp (ref "D24")
      (value "LED-GR")
      (footprint "eagle-import:0805-POL")
      (libsource (lib "eagle-import") (part "LED-0805"))
    )
    (comp (ref "D25")
      (value "SS14")
      (footprint "eagle-import:SMA")
      (libsource (lib "eagle-import") (part "SS14"))
    )
    (comp (ref "D26")
      (value "SS14")
      (footprint "eagle-import:SMA")
      (libsource (lib "eagle-import") (part "SS14"))
    )
    (comp (ref "D27")
      (value "SMLVT3V3")
      (footprint "eagle-import:SMA")
      (libsource (lib "eagle-import") (part "SMLVT3V3"))
    )
    (comp (ref "D28")
      (value "SMAJ5.0A")
      (footprint "eagle-import:SMA")
      (libsource (lib "eagle-import") (part "SMAJ5.0A"))
    )
    (comp (ref "D30")
      (value "PMEG3030BEP")
      (footprint "eagle-import:SOD-128")
      (libsource (lib "eagle-import") (part "PMEG3030BEP"))
    )
    (comp (ref "D31")
      (value "BAT54BRW-7F")
      (footprint "eagle-import:SOT-363")
      (libsource (lib "eagle-import") (part "BAT54BRW-7F"))
    )
    (comp (ref "D32")
      (value "P6SMB16A")
      (footprint "eagle-import:SMB")
      (libsource (lib "eagle-import") (part "P6SMB16A"))
    )
    (comp (ref "F3")
      (value "2920L250DR")
      (footprint "eagle-import:1812")
      (libsource (lib "eagle-import") (part "1812L014DR"))
    )
    (comp (ref "IC19")
      (value "MCP602-I/ST")
      (footprint "eagle-import:TSSOP8")
      (libsource (lib "eagle-import") (part "MCP6022-I/ST"))
    )
    (comp (ref "IC21")
      (value "LTC1771EMS8")
      (footprint "eagle-import:MSOP-08")
      (libsource (lib "eagle-import") (part "LTC1771EMS8"))
    )
    (comp (ref "J45")
      (value "3-641215-4")
      (footprint "eagle-import:3-641215-4")
      (libsource (lib "eagle-import") (part "3-641215-4"))
    )
    (comp (ref "J50")
      (value "0039301040")
      (footprint "eagle-import:0039301040")
      (libsource (lib "eagle-import") (part "0039301040"))
    )
    (comp (ref "L11")
      (value "SER2013-472MLD")
      (footprint "eagle-import:L_SER20XX")
      (fields (field (name "MANUFACTURER") "Coilcraft"))
      (libsource (lib "eagle-import") (part "LSER20XX"))
    )
    (comp (ref "L12")
      (value "SRR1280-150M")
      (footprint "eagle-import:L_SRR1280")
      (fields (field (name "MANUFACTURER") "Bourns") (field (name "MFR_PN") "SRR1280-1x0M"))
      (libsource (lib "eagle-import") (part "LSRR1280"))
    )
    (comp (ref "L14")
      (value "CR75NP-220KC")
      (footprint "eagle-import:CR75")
      (libsource (lib "eagle-import") (part "CR75-330KC"))
    )
    (comp (ref "Q14")
      (value "MAX9938HEUK")
      (footprint "eagle-import:SOT23-5")
      (libsource (lib "eagle-import") (part "TSM9938HEUK+T"))
    )
    (comp (ref "Q15")
      (value "SI4564DY")
      (footprint "eagle-import:SO-08")
      (libsource (lib "eagle-import") (part "SI4564DY"))
    )
    (comp (ref "Q16")
      (value "CSD87331Q3D")
      (footprint "eagle-import:SON8_3.3X3.3_TI")
      (fields (field (name "MANUFACTURER") "TI") (field (name "MFR_PN") "CSD87331Q3D"))
      (libsource (lib "eagle-import") (part "TRANS_DUAL_NFET_HALF-BRQ3D"))
    )
    (comp (ref "Q18")
      (value "SI4564DY")
      (footprint "eagle-import:SO-08")
      (libsource (lib "eagle-import") (part "SI4564DY"))
    )
    (comp (ref "Q19")
      (value "CSD87331Q3D")
      (footprint "eagle-import:SON8_3.3X3.3_TI")
      (fields (field (name "MANUFACTURER") "TI") (field (name "MFR_PN") "CSD87331Q3D"))
      (libsource (lib "eagle-import") (part "TRANS_DUAL_NFET_HALF-BRQ3D"))
    )
    (comp (ref "Q20")
      (value "IPD30N06S2L-23")
      (footprint "eagle-import:TO252")
      (libsource (lib "eagle-import") (part "IPD30N06S2L-23"))
    )
    (comp (ref "Q21")
      (value "IPD30N06S2L-23")
      (footprint "eagle-import:TO252")
      (libsource (lib "eagle-import") (part "IPD30N06S2L-23"))
    )
    (comp (ref "Q23")
      (value "FDN352AP")
      (footprint "eagle-import:SOT-23")
      (libsource (lib "eagle-import") (part "FDN352AP"))
    )
    (comp (ref "R40")
      (value "0.025R")
      (footprint "eagle-import:0805")
      (libsource (lib "eagle-import") (part "R-0805"))
    )
    (comp (ref "R41")
      (value "0.025R")
      (footprint "eagle-import:0805")
      (libsource (lib "eagle-import") (part "R-0805"))
    )
    (comp (ref "R42")
      (value "0.025R")
      (footprint "eagle-import:0805")
      (libsource (lib "eagle-import") (part "R-0805"))
    )
    (comp (ref "R43")
      (value "0.025R")
      (footprint "eagle-import:0805")
      (libsource (lib "eagle-import") (part "R-0805"))
    )
    (comp (ref "R44")
      (value "0.025R")
      (footprint "eagle-import:0805")
      (libsource (lib "eagle-import") (part "R-0805"))
    )
    (comp (ref "R45")
      (value "470R")
      (footprint "eagle-import:0603")
      (libsource (lib "eagle-import") (part "R-0603"))
    )
    (comp (ref "R46")
      (value "470R")
      (footprint "eagle-import:0603")
      (libsource (lib "eagle-import") (part "R-0603"))
    )
    (comp (ref "R154")
      (value "0.025R")
      (footprint "eagle-import:0805")
      (libsource (lib "eagle-import") (part "R-0805"))
    )
    (comp (ref "R156")
      (value "1M")
      (footprint "eagle-import:R0603")
      (fields (field (name "MANUFACTURER") "Panasonic"))
      (libsource (lib "eagle-import") (part "R-US_R0603"))
    )
    (comp (ref "R157")
      (value "10")
      (footprint "eagle-import:R0603")
      (fields (field (name "MANUFACTURER") "Rohm"))
      (libsource (lib "eagle-import") (part "R-US_R0603"))
    )
    (comp (ref "R158")
      (value "10")
      (footprint "eagle-import:R0603")
      (fields (field (name "MANUFACTURER") "Rohm"))
      (libsource (lib "eagle-import") (part "R-US_R0603"))
    )
    (comp (ref "R159")
      (value "1M")
      (footprint "eagle-import:R0603")
      (fields (field (name "MANUFACTURER") "Panasonic"))
      (libsource (lib "eagle-import") (part "R-US_R0603"))
    )
    (comp (ref "R160")
      (value "178k,1%")
      (footprint "eagle-import:R0603")
      (fields (field (name "MANUFACTURER") "Panasonic"))
      (libsource (lib "eagle-import") (part "R-US_R0603"))
    )
    (comp (ref "R161")
      (value "0")
      (footprint "eagle-import:R0603")
      (fields (field (name "MANUFACTURER") "Panasonic"))
      (libsource (lib "eagle-import") (part "R-US_R0603"))
    )
    (comp (ref "R162")
      (value "10k")
      (footprint "eagle-import:R0603")
      (fields (field (name "MANUFACTURER") "Panasonic"))
      (libsource (lib "eagle-import") (part "R-US_R0603"))
    )
    (comp (ref "R163")
      (value "0")
      (footprint "eagle-import:R0603")
      (fields (field (name "MANUFACTURER") "Panasonic"))
      (libsource (lib "eagle-import") (part "R-US_R0603"))
    )
    (comp (ref "R164")
      (value "5.90k,1%")
      (footprint "eagle-import:R0603")
      (fields (field (name "MANUFACTURER") "Panasonic"))
      (libsource (lib "eagle-import") (part "R-US_R0603"))
    )
    (comp (ref "R165")
      (value "93.1k,1%")
      (footprint "eagle-import:R0603")
      (fields (field (name "MANUFACTURER") "Panasonic"))
      (libsource (lib "eagle-import") (part "R-US_R0603"))
    )
    (comp (ref "R166")
      (value "20.0k,1%")
      (footprint "eagle-import:R0603")
      (fields (field (name "MANUFACTURER") "Panasonic"))
      (libsource (lib "eagle-import") (part "R-US_R0603"))
    )
    (comp (ref "R167")
      (value "100k")
      (footprint "eagle-import:R0603")
      (fields (field (name "MANUFACTURER") "Panasonic"))
      (libsource (lib "eagle-import") (part "R-US_R0603"))
    )
    (comp (ref "R170")
      (value "1M")
      (footprint "eagle-import:0603")
      (libsource (lib "eagle-import") (part "R-0603"))
    )
    (comp (ref "R171")
      (value "10")
      (footprint "eagle-import:R0603")
      (fields (field (name "MANUFACTURER") "Rohm"))
      (libsource (lib "eagle-import") (part "R-US_R0603"))
    )
    (comp (ref "R172")
      (value "10")
      (footprint "eagle-import:R0603")
      (fields (field (name "MANUFACTURER") "Rohm"))
      (libsource (lib "eagle-import") (part "R-US_R0603"))
    )
    (comp (ref "R173")
      (value "1M")
      (footprint "eagle-import:0603")
      (libsource (lib "eagle-import") (part "R-0603"))
    )
    (comp (ref "R174")
      (value "1M")
      (footprint "eagle-import:0603")
      (libsource (lib "eagle-import") (part "R-0603"))
    )
    (comp (ref "R175")
      (value "3.3K")
      (footprint "eagle-import:0805")
      (libsource (lib "eagle-import") (part "R-0805"))
    )
    (comp (ref "R176")
      (value "3.3K")
      (footprint "eagle-import:0805")
      (libsource (lib "eagle-import") (part "R-0805"))
    )
    (comp (ref "R177")
      (value "178k,1%")
      (footprint "eagle-import:R0603")
      (fields (field (name "MANUFACTURER") "Panasonic"))
      (libsource (lib "eagle-import") (part "R-US_R0603"))
    )
    (comp (ref "R178")
      (value "0")
      (footprint "eagle-import:R0603")
      (fields (field (name "MANUFACTURER") "Panasonic"))
      (libsource (lib "eagle-import") (part "R-US_R0603"))
    )
    (comp (ref "R179")
      (value "10k")
      (footprint "eagle-import:R0603")
      (fields (field (name "MANUFACTURER") "Panasonic"))
      (libsource (lib "eagle-import") (part "R-US_R0603"))
    )
    (comp (ref "R180")
      (value "0")
      (footprint "eagle-import:R0603")
      (fields (field (name "MANUFACTURER") "Panasonic"))
      (libsource (lib "eagle-import") (part "R-US_R0603"))
    )
    (comp (ref "R181")
      (value "5.90k,1%")
      (footprint "eagle-import:R0603")
      (fields (field (name "MANUFACTURER") "Panasonic"))
      (libsource (lib "eagle-import") (part "R-US_R0603"))
    )
    (comp (ref "R182")
      (value "93.1k,1%")
      (footprint "eagle-import:R0603")
      (fields (field (name "MANUFACTURER") "Panasonic"))
      (libsource (lib "eagle-import") (part "R-US_R0603"))
    )
    (comp (ref "R183")
      (value "1M")
      (footprint "eagle-import:0603")
      (libsource (lib "eagle-import") (part "R-0603"))
    )
    (comp (ref "R184")
      (value "1M")
      (footprint "eagle-import:0603")
      (libsource (lib "eagle-import") (part "R-0603"))
    )
    (comp (ref "R185")
      (value "20.0k,1%")
      (footprint "eagle-import:R0603")
      (fields (field (name "MANUFACTURER") "Panasonic"))
      (libsource (lib "eagle-import") (part "R-US_R0603"))
    )
    (comp (ref "R186")
      (value "100k")
      (footprint "eagle-import:R0603")
      (fields (field (name "MANUFACTURER") "Panasonic"))
      (libsource (lib "eagle-import") (part "R-US_R0603"))
    )
    (comp (ref "R187")
      (value "47K")
      (footprint "eagle-import:0603")
      (libsource (lib "eagle-import") (part "R-0603"))
    )
    (comp (ref "R189")
      (value "0.12R")
      (footprint "eagle-import:0805")
      (libsource (lib "eagle-import") (part "R-0805"))
    )
    (comp (ref "R190")
      (value "47K")
      (footprint "eagle-import:0603")
      (libsource (lib "eagle-import") (part "R-0603"))
    )
    (comp (ref "R193")
      (value "10K")
      (footprint "eagle-import:0603")
      (libsource (lib "eagle-import") (part "R-0603"))
    )
    (comp (ref "R194")
      (value "3.09M")
      (footprint "eagle-import:0603")
      (libsource (lib "eagle-import") (part "R-0603"))
    )
    (comp (ref "R197")
      (value "1M")
      (footprint "eagle-import:0603")
      (libsource (lib "eagle-import") (part "R-0603"))
    )
    (comp (ref "TP61")
      (value "TPB1,27")
      (footprint "eagle-import:B1,27")
      (libsource (lib "eagle-import") (part "TPB1,27"))
    )
    (comp (ref "TP62")
      (value "TPB1,27")
      (footprint "eagle-import:B1,27")
      (libsource (lib "eagle-import") (part "TPB1,27"))
    )
    (comp (ref "TP63")
      (value "TPB1,27")
      (footprint "eagle-import:B1,27")
      (libsource (lib "eagle-import") (part "TPB1,27"))
    )
    (comp (ref "TP64")
      (value "TPB1,27")
      (footprint "eagle-import:B1,27")
      (libsource (lib "eagle-import") (part "TPB1,27"))
    )
    (comp (ref "TP65")
      (value "TPB1,27")
      (footprint "eagle-import:B1,27")
      (libsource (lib "eagle-import") (part "TPB1,27"))
    )
    (comp (ref "TP66")
      (value "TPB1,27")
      (footprint "eagle-import:B1,27")
      (libsource (lib "eagle-import") (part "TPB1,27"))
    )
    (comp (ref "TP67")
      (value "TPB1,27")
      (footprint "eagle-import:B1,27")
      (libsource (lib "eagle-import") (part "TPB1,27"))
    )
    (comp (ref "U2")
      (value "LE33CD")
      (footprint "eagle-import:LE33")
      (libsource (lib "eagle-import") (part "LE33"))
    )
    (comp (ref "U6")
      (value "TPS43061")
      (footprint "eagle-import:QFN16_3X3_EP")
      (fields (field (name "MANUFACTURER") "TI"))
      (libsource (lib "eagle-import") (part "IC_TI_TPS43061RTE"))
    )
    (comp (ref "U7")
      (value "TPS43061")
      (footprint "eagle-import:QFN16_3X3_EP")
      (fields (field (name "MANUFACTURER") "TI"))
      (libsource (lib "eagle-import") (part "IC_TI_TPS43061RTE"))
    )
    (comp (ref "C114")
      (value "0.1u")
      (footprint "eagle-import:0603")
      (libsource (lib "eagle-import") (part "C-0603"))
    )
    (comp (ref "C115")
      (value "4.7uF/6.3V")
      (footprint "eagle-import:0603")
      (libsource (lib "eagle-import") (part "C-0603"))
    )
    (comp (ref "C121")
      (value "0.1u")
      (footprint "eagle-import:0603")
      (libsource (lib "eagle-import") (part "C-0603"))
    )
    (comp (ref "D17")
      (value "LED-GR")
      (footprint "eagle-import:0805-POL")
      (libsource (lib "eagle-import") (part "LED-0805"))
    )
    (comp (ref "D19")
      (value "LED-GR")
      (footprint "eagle-import:0805-POL")
      (libsource (lib "eagle-import") (part "LED-0805"))
    )
    (comp (ref "IC18")
      (value "FT232RL")
      (footprint "eagle-import:SSOP28DB")
      (libsource (lib "eagle-import") (part "FT232RL"))
    )
    (comp (ref "J41")
      (value "DNP")
      (footprint "eagle-import:MA06-1")
      (libsource (lib "eagle-import") (part "MA06-1"))
    )
    (comp (ref "R151")
      (value "470R")
      (footprint "eagle-import:0603")
      (libsource (lib "eagle-import") (part "R-0603"))
    )
    (comp (ref "R152")
      (value "470R")
      (footprint "eagle-import:0603")
      (libsource (lib "eagle-import") (part "R-0603"))
    )
    (comp (ref "TP60")
      (value "ROUND_SMD0.7MM")
      (footprint "eagle-import:SMD_ROUND_07MM")
      (libsource (lib "eagle-import") (part "ROUND_SMD0.7MM"))
    )
    (comp (ref "X2")
      (value "MINI-USB_4P-85-32004-10X")
      (footprint "eagle-import:85-32004-10X")
      (libsource (lib "eagle-import") (part "MINI-USB_4P-85-32004-10X"))
    )
  )
  (nets
    (net (code "1") (name "+3.3V") (class "Default")
      (node (ref "C1") (pin "1") (pinfunction "1_1") (pintype "passive"))
      (node (ref "C157") (pin "1") (pinfunction "1_1") (pintype "passive"))
      (node (ref "C16") (pin "2") (pinfunction "2_2") (pintype "passive"))
      (node (ref "C17") (pin "1") (pinfunction "1_1") (pintype "passive"))
      (node (ref "C2") (pin "1") (pinfunction "1_1") (pintype "passive"))
      (node (ref "C29") (pin "2") (pinfunction "2_2") (pintype "passive"))
      (node (ref "C5") (pin "1") (pinfunction "1_1") (pintype "passive"))
      (node (ref "C6") (pin "1") (pinfunction "1_1") (pintype "passive"))
      (node (ref "C8") (pin "1") (pinfunction "1_1") (pintype "passive"))
      (node (ref "C9") (pin "1") (pinfunction "1_1") (pintype "passive"))
      (node (ref "D1") (pin "2") (pinfunction "A2_2") (pintype "passive"))
      (node (ref "D27") (pin "+") (pinfunction "C_+") (pintype "passive"))
      (node (ref "D31") (pin "4") (pinfunction "K_4") (pintype "passive"))
      (node (ref "D31") (pin "5") (pinfunction "K_5") (pintype "passive"))
      (node (ref "IC3") (pin "16") (pinfunction "VDD16_16") (pintype "power_in"))
      (node (ref "IC3") (pin "2") (pinfunction "VDD2_2") (pintype "power_in"))
      (node (ref "IC3") (pin "37") (pinfunction "VDD37_37") (pintype "power_in"))
      (node (ref "IC3") (pin "46") (pinfunction "VDD46_46") (pintype "power_in"))
      (node (ref "IC3") (pin "62") (pinfunction "VDD62_62") (pintype "power_in"))
      (node (ref "IC3") (pin "86") (pinfunction "VDD86_86") (pintype "power_in"))
      (node (ref "J1") (pin "9") (pinfunction "9_9") (pintype "passive"))
      (node (ref "J11") (pin "2") (pinfunction "2_2") (pintype "passive"))
      (node (ref "J18") (pin "5") (pinfunction "5_5") (pintype "bidirectional"))
      (node (ref "J8") (pin "10") (pinfunction "10_10") (pintype "passive"))
      (node (ref "Q7") (pin "1") (pinfunction "S_1") (pintype "passive"))
      (node (ref "Q7") (pin "4") (pinfunction "S_4") (pintype "passive"))
      (node (ref "R1") (pin "2") (pinfunction "2_2") (pintype "passive"))
      (node (ref "R12") (pin "2") (pinfunction "2_2") (pintype "passive"))
      (node (ref "R14") (pin "2") (pinfunction "2_2") (pintype "passive"))
      (node (ref "R15") (pin "2") (pinfunction "2_2") (pintype "passive"))
      (node (ref "R167") (pin "2") (pinfunction "2_2") (pintype "passive"))
      (node (ref "R186") (pin "2") (pinfunction "2_2") (pintype "passive"))
      (node (ref "R187") (pin "2") (pinfunction "2_2") (pintype "passive"))
      (node (ref "R190") (pin "2") (pinfunction "2_2") (pintype "passive"))
      (node (ref "R2") (pin "7") (pinfunction "2_7") (pintype "passive"))
      (node (ref "R2") (pin "8") (pinfunction "2_8") (pintype "passive"))
      (node (ref "R37") (pin "2") (pinfunction "2_2") (pintype "passive"))
      (node (ref "TP64") (pin "TP") (pinfunction "TP_TP") (pintype "input"))
      (node (ref "TP9") (pin "P$1") (pinfunction "TP_P$1") (pintype "passive"))
      (node (ref "U1") (pin "1") (pinfunction "DVCC_1") (pintype "bidirectional"))
      (node (ref "U1") (pin "12") (pinfunction "SVBAT_12") (pintype "bidirectional"))
      (node (ref "U1") (pin "13") (pinfunction "PVBAT_13") (pintype "bidirectional"))
      (node (ref "U2") (pin "1") (pinfunction "VOUT_1") (pintype "bidirectional"))
    )
    (net (code "2") (name "+3.3V{slash}1") (class "Default")
      (node (ref "C22") (pin "1") (pinfunction "1_1") (pintype "passive"))
      (node (ref "C33") (pin "1") (pinfunction "1_1") (pintype "passive"))
      (node (ref "C37") (pin "1") (pinfunction "1_1") (pintype "passive"))
      (node (ref "C48") (pin "1") (pinfunction "1_1") (pintype "passive"))
      (node (ref "IC5") (pin "7") (pinfunction "A0_7") (pintype "input"))
      (node (ref "IC5") (pin "8") (pinfunction "VCC_8") (pintype "power_in"))
      (node (ref "IC6") (pin "8") (pinfunction "VCC_8") (pintype "power_in"))
      (node (ref "IC8") (pin "3") (pinfunction "/WP_3") (pintype "input"))
      (node (ref "IC8") (pin "7") (pinfunction "/HOLD_7") (pintype "input"))
      (node (ref "IC8") (pin "8") (pinfunction "VCC_8") (pintype "power_in"))
      (node (ref "J49") (pin "2") (pinfunction "2_2") (pintype "passive"))
      (node (ref "Q7") (pin "6") (pinfunction "D_6") (pintype "passive"))
      (node (ref "Q7") (pin "P1") (pinfunction "D1_P1") (pintype "passive"))
      (node (ref "R16") (pin "2") (pinfunction "2_2") (pintype "passive"))
      (node (ref "R17") (pin "2") (pinfunction "2_2") (pintype "passive"))
      (node (ref "R200") (pin "1") (pinfunction "1_1") (pintype "passive"))
      (node (ref "R201") (pin "1") (pinfunction "1_1") (pintype "passive"))
      (node (ref "R205") (pin "2") (pinfunction "2_2") (pintype "passive"))
      (node (ref "R206") (pin "2") (pinfunction "2_2") (pintype "passive"))
      (node (ref "R24") (pin "1") (pinfunction "1_1") (pintype "passive"))
      (node (ref "R31") (pin "2") (pinfunction "2_2") (pintype "passive"))
      (node (ref "R32") (pin "2") (pinfunction "2_2") (pintype "passive"))
      (node (ref "TP8") (pin "P$1") (pinfunction "TP_P$1") (pintype "passive"))
      (node (ref "U3") (pin "8") (pinfunction "VDD_8") (pintype "bidirectional"))
    )
    (net (code "3") (name "+3.3V{slash}2") (class "Default")
      (node (ref "C14") (pin "1") (pinfunction "1_1") (pintype "passive"))
      (node (ref "C35") (pin "2") (pinfunction "2_2") (pintype "passive"))
      (node (ref "IC2") (pin "8") (pinfunction "VCC_8") (pintype "power_in"))
      (node (ref "J18") (pin "10") (pinfunction "10_10") (pintype "bidirectional"))
      (node (ref "J2") (pin "2") (pinfunction "2_2") (pintype "passive"))
      (node (ref "J30") (pin "6") (pinfunction "VCC_6") (pintype "bidirectional"))
      (node (ref "JP1") (pin "2") (pinfunction "2_2") (pintype "passive"))
      (node (ref "Q7") (pin "3") (pinfunction "D_3") (pintype "passive"))
      (node (ref "Q7") (pin "P2") (pinfunction "D1_P2") (pintype "passive"))
      (node (ref "R11") (pin "2") (pinfunction "2_2") (pintype "passive"))
    )
    (net (code "4") (name "+5V") (class "Default")
      (node (ref "C149") (pin "1") (pinfunction "1_1") (pintype "passive"))
      (node (ref "C150") (pin "1") (pinfunction "1_1") (pintype "passive"))
      (node (ref "C156") (pin "1") (pinfunction "PIN+_1") (pintype "passive"))
      (node (ref "C158") (pin "1") (pinfunction "1_1") (pintype "passive"))
      (node (ref "C160") (pin "2") (pinfunction "2_2") (pintype "passive"))
      (node (ref "D28") (pin "+") (pinfunction "C_+") (pintype "passive"))
      (node (ref "J18") (pin "4") (pinfunction "4_4") (pintype "bidirectional"))
      (node (ref "L14") (pin "2") (pinfunction "2_2") (pintype "passive"))
      (node (ref "R194") (pin "1") (pinfunction "1_1") (pintype "passive"))
      (node (ref "TP65") (pin "TP") (pinfunction "TP_TP") (pintype "input"))
      (node (ref "U2") (pin "8") (pinfunction "VIN_8") (pintype "bidirectional"))
    )
    (net (code "5") (name "+SMB") (class "Default")
      (node (ref "C11") (pin "1") (pinfunction "1_1") (pintype "passive"))
      (node (ref "C135") (pin "1") (pinfunction "1_1") (pintype "passive"))
      (node (ref "C152") (pin "1") (pinfunction "1_1") (pintype "passive"))
      (node (ref "C153") (pin "1") (pinfunction "1_1") (pintype "passive"))
      (node (ref "C154") (pin "1") (pinfunction "1_1") (pintype "passive"))
      (node (ref "C155") (pin "1") (pinfunction "1_1") (pintype "passive"))
      (node (ref "C27") (pin "1") (pinfunction "1_1") (pintype "passive"))
      (node (ref "C28") (pin "1") (pinfunction "1_1") (pintype "passive"))
      (node (ref "D2") (pin "A") (pinfunction "A_A") (pintype "passive"))
      (node (ref "IC21") (pin "6") (pinfunction "VIN_6") (pintype "power_in"))
      (node (ref "IC21") (pin "8") (pinfunction "MODE_8") (pintype "input"))
      (node (ref "IC9") (pin "5") (pinfunction "VIN_5") (pintype "power_in"))
      (node (ref "J1") (pin "10") (pinfunction "10_10") (pintype "passive"))
      (node (ref "J18") (pin "2") (pinfunction "2_2") (pintype "bidirectional"))
      (node (ref "J7") (pin "2") (pinfunction "2_2") (pintype "passive"))
      (node (ref "J9") (pin "2") (pinfunction "2_2") (pintype "passive"))
      (node (ref "Q14") (pin "4") (pinfunction "VIN-_4") (pintype "input"))
      (node (ref "Q15") (pin "3") (pinfunction "S_3") (pintype "passive"))
      (node (ref "Q18") (pin "3") (pinfunction "S_3") (pintype "passive"))
      (node (ref "Q2") (pin "4") (pinfunction "Q2S_4") (pintype "bidirectional"))
      (node (ref "Q5") (pin "4") (pinfunction "Q2S_4") (pintype "bidirectional"))
      (node (ref "R154") (pin "2") (pinfunction "2_2") (pintype "passive"))
      (node (ref "R156") (pin "2") (pinfunction "2_2") (pintype "passive"))
      (node (ref "R170") (pin "1") (pinfunction "1_1") (pintype "passive"))
      (node (ref "R189") (pin "2") (pinfunction "2_2") (pintype "passive"))
      (node (ref "R20") (pin "6") (pinfunction "2_6") (pintype "passive"))
      (node (ref "R3") (pin "1") (pinfunction "1_1") (pintype "passive"))
      (node (ref "R40") (pin "2") (pinfunction "2_2") (pintype "passive"))
      (node (ref "R41") (pin "2") (pinfunction "2_2") (pintype "passive"))
    )
    (net (code "6") (name "+SMB_PRE") (class "Default")
      (node (ref "F3") (pin "1") (pinfunction "1_1") (pintype "passive"))
      (node (ref "J15") (pin "9") (pinfunction "9_9") (pintype "bidirectional"))
      (node (ref "J15") (pin "9A") (pinfunction "9_9A") (pintype "bidirectional"))
      (node (ref "J45") (pin "4") (pinfunction "4_4") (pintype "passive"))
    )
    (net (code "7") (name "3V3_AUD") (class "Default")
      (node (ref "C180") (pin "1") (pinfunction "1_1") (pintype "passive"))
      (node (ref "C181") (pin "1") (pinfunction "1_1") (pintype "passive"))
      (node (ref "C182") (pin "1") (pinfunction "1_1") (pintype "passive"))
      (node (ref "R206") (pin "1") (pinfunction "1_1") (pintype "passive"))
      (node (ref "R207") (pin "1") (pinfunction "1_1") (pintype "passive"))
      (node (ref "U9") (pin "6") (pinfunction "V+_6") (pintype "power_in"))
    )
    (net (code "8") (name "5V_ON") (class "Default")
      (node (ref "C163") (pin "1") (pinfunction "1_1") (pintype "passive"))
      (node (ref "IC21") (pin "1") (pinfunction "RUN/SS_1") (pintype "input"))
      (node (ref "IC3") (pin "92") (pinfunction "RA7/CN40_92") (pintype "bidirectional"))
    )
    (net (code "9") (name "18V_GND") (class "Default")
      (node (ref "C39") (pin "2") (pinfunction "2_2") (pintype "passive"))
      (node (ref "C40") (pin "1") (pinfunction "1_1") (pintype "passive"))
      (node (ref "R34") (pin "1") (pinfunction "1_1") (pintype "passive"))
      (node (ref "R39") (pin "1") (pinfunction "1_1") (pintype "passive"))
      (node (ref "U3") (pin "5") (pinfunction "AIN1_5") (pintype "bidirectional"))
    )
    (net (code "10") (name "18V_SENSE") (class "Default")
      (node (ref "J15") (pin "1") (pinfunction "1_1") (pintype "bidirectional"))
      (node (ref "J15") (pin "1A") (pinfunction "1_1A") (pintype "bidirectional"))
      (node (ref "J15") (pin "3") (pinfunction "3_3") (pintype "bidirectional"))
      (node (ref "J15") (pin "3A") (pinfunction "3_3A") (pintype "bidirectional"))
      (node (ref "R33") (pin "2") (pinfunction "2_2") (pintype "passive"))
    )
    (net (code "11") (name "A+") (class "Default")
      (node (ref "IC2") (pin "6") (pinfunction "A_6") (pintype "bidirectional"))
      (node (ref "L2") (pin "1") (pinfunction "1_1") (pintype "passive"))
      (node (ref "Q3") (pin "3") (pinfunction "3_3") (pintype "passive"))
      (node (ref "R11") (pin "1") (pinfunction "1_1") (pintype "passive"))
      (node (ref "R9") (pin "1") (pinfunction "1_1") (pintype "passive"))
    )
    (net (code "12") (name "A1") (class "Default")
      (node (ref "J7") (pin "3") (pinfunction "3_3") (pintype "passive"))
      (node (ref "J9") (pin "3") (pinfunction "3_3") (pintype "passive"))
      (node (ref "L2") (pin "2") (pinfunction "2_2") (pintype "passive"))
    )
    (net (code "13") (name "ACT_S1_B") (class "Default")
      (node (ref "IC3") (pin "52") (pinfunction "CN70/RP30/RF2_52") (pintype "bidirectional"))
      (node (ref "Q20") (pin "1") (pinfunction "G_1") (pintype "passive"))
      (node (ref "R183") (pin "1") (pinfunction "1_1") (pintype "passive"))
    )
    (net (code "14") (name "ACT_S2_B") (class "Default")
      (node (ref "IC3") (pin "53") (pinfunction "CN74/RP15/RF8_53") (pintype "bidirectional"))
      (node (ref "Q21") (pin "1") (pinfunction "G_1") (pintype "passive"))
      (node (ref "R184") (pin "1") (pinfunction "1_1") (pintype "passive"))
    )
    (net (code "15") (name "AGND") (class "Default")
      (node (ref "C165") (pin "2") (pinfunction "2_2") (pintype "passive"))
      (node (ref "C166") (pin "2") (pinfunction "2_2") (pintype "passive"))
      (node (ref "C167") (pin "2") (pinfunction "2_2") (pintype "passive"))
      (node (ref "C168") (pin "2") (pinfunction "2_2") (pintype "passive"))
      (node (ref "C169") (pin "2") (pinfunction "2_2") (pintype "passive"))
      (node (ref "C170") (pin "2") (pinfunction "2_2") (pintype "passive"))
      (node (ref "C171") (pin "2") (pinfunction "2_2") (pintype "passive"))
      (node (ref "C172") (pin "2") (pinfunction "2_2") (pintype "passive"))
      (node (ref "C176") (pin "2") (pinfunction "2_2") (pintype "passive"))
      (node (ref "C177") (pin "1") (pinfunction "1_1") (pintype "passive"))
      (node (ref "C179") (pin "2") (pinfunction "2_2") (pintype "passive"))
      (node (ref "C180") (pin "2") (pinfunction "2_2") (pintype "passive"))
      (node (ref "C181") (pin "2") (pinfunction "2_2") (pintype "passive"))
      (node (ref "C182") (pin "2") (pinfunction "2_2") (pintype "passive"))
      (node (ref "J17") (pin "1") (pinfunction "1_1") (pintype "bidirectional"))
      (node (ref "J17") (pin "12") (pinfunction "12_12") (pintype "bidirectional"))
      (node (ref "J17") (pin "3") (pinfunction "3_3") (pintype "bidirectional"))
      (node (ref "J17") (pin "6") (pinfunction "6_6") (pintype "bidirectional"))
      (node (ref "J17") (pin "9") (pinfunction "9_9") (pintype "bidirectional"))
      (node (ref "J47") (pin "3") (pinfunction "3_3") (pintype "passive"))
      (node (ref "J47") (pin "4") (pinfunction "4_4") (pintype "passive"))
      (node (ref "J48") (pin "1") (pinfunction "1_1") (pintype "passive"))
      (node (ref "L17") (pin "2") (pinfunction "2_2") (pintype "passive"))
      (node (ref "Q24") (pin "2") (pinfunction "S_2") (pintype "passive"))
      (node (ref "R202") (pin "2") (pinfunction "2_2") (pintype "passive"))
      (node (ref "R203") (pin "2") (pinfunction "2_2") (pintype "passive"))
      (node (ref "R210") (pin "2") (pinfunction "2_2") (pintype "passive"))
      (node (ref "R211") (pin "2") (pinfunction "2_2") (pintype "passive"))
      (node (ref "U8") (pin "19") (pinfunction "PGND_19") (pintype "power_in"))
      (node (ref "U8") (pin "24") (pinfunction "PGND_24") (pintype "power_in"))
      (node (ref "U8") (pin "3") (pinfunction "GND_3") (pintype "power_in"))
      (node (ref "U8") (pin "4") (pinfunction "GND_4") (pintype "power_in"))
      (node (ref "U8") (pin "8") (pinfunction "AGND_8") (pintype "power_in"))
      (node (ref "U8") (pin "EP") (pinfunction "EP_EP") (pintype "power_in"))
      (node (ref "U9") (pin "2") (pinfunction "V-_2") (pintype "power_in"))
    )
    (net (code "16") (name "AUD_AMP_FAULT#") (class "Default")
      (node (ref "R204") (pin "1") (pinfunction "1_1") (pintype "passive"))
      (node (ref "R205") (pin "1") (pinfunction "1_1") (pintype "passive"))
      (node (ref "U8") (pin "1") (pinfunction "~{SD}_1") (pintype "input"))
      (node (ref "U8") (pin "2") (pinfunction "~{FAULT}_2") (pintype "output"))
    )
    (net (code "17") (name "AUD_AMP_G0") (class "Default")
      (node (ref "IC3") (pin "41") (pinfunction "RB12/AN12/CN30_41") (pintype "bidirectional"))
      (node (ref "R200") (pin "2") (pinfunction "2_2") (pintype "passive"))
      (node (ref "R202") (pin "1") (pinfunction "1_1") (pintype "passive"))
      (node (ref "TP4") (pin "P$1") (pinfunction "TP_P$1") (pintype "passive"))
      (node (ref "U8") (pin "5") (pinfunction "GAIN0_5") (pintype "input"))
    )
    (net (code "18") (name "AUD_AMP_G1") (class "Default")
      (node (ref "IC3") (pin "42") (pinfunction "RB13/AN13/CN31_42") (pintype "bidirectional"))
      (node (ref "R201") (pin "2") (pinfunction "2_2") (pintype "passive"))
      (node (ref "R203") (pin "1") (pinfunction "1_1") (pintype "passive"))
      (node (ref "TP5") (pin "P$1") (pinfunction "TP_P$1") (pintype "passive"))
      (node (ref "U8") (pin "6") (pinfunction "GAIN1_6") (pintype "input"))
    )
    (net (code "19") (name "AUD_AMP_INN") (class "Default")
      (node (ref "C177") (pin "2") (pinfunction "2_2") (pintype "passive"))
      (node (ref "U8") (pin "11") (pinfunction "INN_11") (pintype "input"))
    )
    (net (code "20") (name "AUD_AMP_INP") (class "Default")
      (node (ref "C174") (pin "2") (pinfunction "2_2") (pintype "passive"))
      (node (ref "C175") (pin "2") (pinfunction "2_2") (pintype "passive"))
      (node (ref "U8") (pin "12") (pinfunction "INP_12") (pintype "input"))
    )
    (net (code "21") (name "AUD_BSN") (class "Default")
      (node (ref "C178") (pin "1") (pinfunction "1_1") (pintype "passive"))
      (node (ref "U8") (pin "22") (pinfunction "BSN_22") (pintype "input"))
      (node (ref "U8") (pin "26") (pinfunction "BSN_26") (pintype "input"))
    )
    (net (code "22") (name "AUD_BSP") (class "Default")
      (node (ref "C173") (pin "1") (pinfunction "1_1") (pintype "passive"))
      (node (ref "U8") (pin "17") (pinfunction "BSP_17") (pintype "input"))
      (node (ref "U8") (pin "21") (pinfunction "BSP_21") (pintype "input"))
    )
    (net (code "23") (name "AUD_GVDD") (class "Default")
      (node (ref "C172") (pin "1") (pinfunction "1_1") (pintype "passive"))
      (node (ref "U8") (pin "10") (pinfunction "PLIMIT_10") (pintype "input"))
      (node (ref "U8") (pin "9") (pinfunction "GVDD_9") (pintype "output"))
    )
    (net (code "24") (name "B-") (class "Default")
      (node (ref "IC2") (pin "7") (pinfunction "B_7") (pintype "bidirectional"))
      (node (ref "L1") (pin "1") (pinfunction "1_1") (pintype "passive"))
      (node (ref "Q3") (pin "2") (pinfunction "2_2") (pintype "passive"))
      (node (ref "R10") (pin "2") (pinfunction "2_2") (pintype "passive"))
      (node (ref "R9") (pin "2") (pinfunction "2_2") (pintype "passive"))
    )
    (net (code "25") (name "B1") (class "Default")
      (node (ref "J7") (pin "4") (pinfunction "4_4") (pintype "passive"))
      (node (ref "J9") (pin "4") (pinfunction "4_4") (pintype "passive"))
      (node (ref "L1") (pin "2") (pinfunction "2_2") (pintype "passive"))
    )
    (net (code "26") (name "B12_BOOT") (class "Default")
      (node (ref "C126") (pin "1") (pinfunction "1_1") (pintype "passive"))
      (node (ref "U6") (pin "11") (pinfunction "BOOT_11") (pintype "passive"))
    )
    (net (code "27") (name "B12_COMP") (class "Default")
      (node (ref "C131") (pin "1") (pinfunction "1_1") (pintype "passive"))
      (node (ref "R164") (pin "2") (pinfunction "2_2") (pintype "passive"))
      (node (ref "U6") (pin "3") (pinfunction "COMP_3") (pintype "passive"))
    )
    (net (code "28") (name "B12_FB") (class "Default")
      (node (ref "R160") (pin "1") (pinfunction "1_1") (pintype "passive"))
      (node (ref "R166") (pin "2") (pinfunction "2_2") (pintype "passive"))
      (node (ref "U6") (pin "4") (pinfunction "FB_4") (pintype "input"))
    )
    (net (code "29") (name "B12_FEED") (class "Default")
      (node (ref "L11") (pin "2") (pinfunction "2_2") (pintype "passive"))
      (node (ref "R158") (pin "2") (pinfunction "2_2") (pintype "passive"))
      (node (ref "R42") (pin "2") (pinfunction "2_2") (pintype "passive"))
      (node (ref "R43") (pin "2") (pinfunction "2_2") (pintype "passive"))
    )
    (net (code "30") (name "B12_HDRV") (class "Default")
      (node (ref "R161") (pin "2") (pinfunction "2_2") (pintype "passive"))
      (node (ref "U6") (pin "13") (pinfunction "HDRV_13") (pintype "output"))
    )
    (net (code "31") (name "B12_HG") (class "Default")
      (node (ref "Q16") (pin "3") (pinfunction "TG_3") (pintype "passive"))
      (node (ref "R161") (pin "1") (pinfunction "1_1") (pintype "passive"))
    )
    (net (code "32") (name "B12_ISNS+") (class "Default")
      (node (ref "C124") (pin "1") (pinfunction "1_1") (pintype "passive"))
      (node (ref "R157") (pin "1") (pinfunction "1_1") (pintype "passive"))
      (node (ref "U6") (pin "6") (pinfunction "ISNS+_6") (pintype "input"))
    )
    (net (code "33") (name "B12_ISNS-") (class "Default")
      (node (ref "C124") (pin "2") (pinfunction "2_2") (pintype "passive"))
      (node (ref "R158") (pin "1") (pinfunction "1_1") (pintype "passive"))
      (node (ref "U6") (pin "5") (pinfunction "ISNS-_5") (pintype "input"))
    )
    (net (code "34") (name "B12_L") (class "Default")
      (node (ref "D20") (pin "A") (pinfunction "A_A") (pintype "passive"))
      (node (ref "L11") (pin "1") (pinfunction "1_1") (pintype "passive"))
      (node (ref "Q16") (pin "6") (pinfunction "VSW_6") (pintype "passive"))
      (node (ref "Q16") (pin "7") (pinfunction "VSW_7") (pintype "passive"))
      (node (ref "Q16") (pin "8") (pinfunction "VSW_8") (pintype "passive"))
    )
    (net (code "35") (name "B12_LDRV") (class "Default")
      (node (ref "R163") (pin "2") (pinfunction "2_2") (pintype "passive"))
      (node (ref "U6") (pin "8") (pinfunction "LDRV_8") (pintype "output"))
    )
    (net (code "36") (name "B12_LG") (class "Default")
      (node (ref "Q16") (pin "5") (pinfunction "BG_5") (pintype "passive"))
      (node (ref "R163") (pin "1") (pinfunction "1_1") (pintype "passive"))
    )
    (net (code "37") (name "B12_PG") (class "Default")
      (node (ref "IC3") (pin "69") (pinfunction "CN54/RP4/RD9_69") (pintype "bidirectional"))
      (node (ref "R167") (pin "1") (pinfunction "1_1") (pintype "passive"))
      (node (ref "U6") (pin "14") (pinfunction "PGOOD_14") (pintype "open_collector"))
    )
    (net (code "38") (name "B12_RC") (class "Default")
      (node (ref "C133") (pin "1") (pinfunction "1_1") (pintype "passive"))
      (node (ref "R164") (pin "1") (pinfunction "1_1") (pintype "passive"))
    )
    (net (code "39") (name "B12_RT") (class "Default")
      (node (ref "R165") (pin "2") (pinfunction "2_2") (pintype "passive"))
      (node (ref "U6") (pin "1") (pinfunction "RT/CLK_1") (pintype "passive"))
    )
    (net (code "40") (name "B12_SS") (class "Default")
      (node (ref "C132") (pin "1") (pinfunction "1_1") (pintype "passive"))
      (node (ref "U6") (pin "2") (pinfunction "SS_2") (pintype "passive"))
    )
    (net (code "41") (name "B12_SW") (class "Default")
      (node (ref "C126") (pin "2") (pinfunction "2_2") (pintype "passive"))
      (node (ref "Q16") (pin "4") (pinfunction "TGR_4") (pintype "passive"))
      (node (ref "U6") (pin "12") (pinfunction "SW_12") (pintype "output"))
    )
    (net (code "42") (name "B12_VCC") (class "Default")
      (node (ref "C127") (pin "1") (pinfunction "1_1") (pintype "passive"))
      (node (ref "U6") (pin "10") (pinfunction "VCC_10") (pintype "output"))
    )
    (net (code "43") (name "BAT_GND") (class "Default")
      (node (ref "C41") (pin "2") (pinfunction "2_2") (pintype "passive"))
      (node (ref "C42") (pin "1") (pinfunction "1_1") (pintype "passive"))
      (node (ref "R36") (pin "1") (pinfunction "1_1") (pintype "passive"))
      (node (ref "R38") (pin "1") (pinfunction "1_1") (pintype "passive"))
      (node (ref "U3") (pin "7") (pinfunction "AIN3_7") (pintype "bidirectional"))
    )
    (net (code "44") (name "BAT_SENSE") (class "Default")
      (node (ref "J15") (pin "5") (pinfunction "5_5") (pintype "bidirectional"))
      (node (ref "J15") (pin "5A") (pinfunction "5_5A") (pintype "bidirectional"))
      (node (ref "J15") (pin "7") (pinfunction "7_7") (pintype "bidirectional"))
      (node (ref "J15") (pin "7A") (pinfunction "7_7A") (pintype "bidirectional"))
      (node (ref "R35") (pin "2") (pinfunction "2_2") (pintype "passive"))
    )
    (net (code "45") (name "BTN_1") (class "Default")
      (node (ref "IC4") (pin "1") (pinfunction "GP0/PGD_1") (pintype "bidirectional"))
      (node (ref "J12") (pin "4") (pinfunction "4_4") (pintype "passive"))
      (node (ref "J19") (pin "10") (pinfunction "10_10") (pintype "bidirectional"))
      (node (ref "R2") (pin "2") (pinfunction "1_2") (pintype "passive"))
      (node (ref "R2") (pin "3") (pinfunction "1_3") (pintype "passive"))
    )
    (net (code "46") (name "BTN_1PIN_B") (class "Default")
      (node (ref "C12") (pin "1") (pinfunction "1_1") (pintype "passive"))
      (node (ref "IC3") (pin "90") (pinfunction "RG0/CN77_90") (pintype "bidirectional"))
      (node (ref "R2") (pin "6") (pinfunction "2_6") (pintype "passive"))
    )
    (net (code "47") (name "BTN_2") (class "Default")
      (node (ref "IC4") (pin "3") (pinfunction "GP1/PGC_3") (pintype "bidirectional"))
      (node (ref "J12") (pin "5") (pinfunction "5_5") (pintype "passive"))
      (node (ref "J19") (pin "12") (pinfunction "12_12") (pintype "bidirectional"))
      (node (ref "R2") (pin "1") (pinfunction "1_1") (pintype "passive"))
      (node (ref "R2") (pin "4") (pinfunction "1_4") (pintype "passive"))
    )
    (net (code "48") (name "BTN_2PIN_B") (class "Default")
      (node (ref "C13") (pin "1") (pinfunction "1_1") (pintype "passive"))
      (node (ref "IC3") (pin "89") (pinfunction "RG1/CN78_89") (pintype "bidirectional"))
      (node (ref "R2") (pin "5") (pinfunction "2_5") (pintype "passive"))
    )
    (net (code "49") (name "CL_IRQ") (class "Default")
      (node (ref "IC3") (pin "20") (pinfunction "RB5/AN5/CN7/RP18_20") (pintype "bidirectional"))
      (node (ref "J1") (pin "4") (pinfunction "4_4") (pintype "passive"))
    )
    (net (code "50") (name "CON_LED") (class "Default")
      (node (ref "IC3") (pin "40") (pinfunction "CN75/RPI32/RF12_40") (pintype "bidirectional"))
      (node (ref "JP1") (pin "6") (pinfunction "6_6") (pintype "passive"))
    )
    (net (code "51") (name "DCDC_12V_EN") (class "Default")
      (node (ref "IC3") (pin "84") (pinfunction "CN16/RD7_84") (pintype "bidirectional"))
      (node (ref "Q15") (pin "2") (pinfunction "G_2") (pintype "passive"))
      (node (ref "R162") (pin "2") (pinfunction "2_2") (pintype "passive"))
      (node (ref "U6") (pin "15") (pinfunction "EN_15") (pintype "input"))
    )
    (net (code "52") (name "DGND") (class "Default")
      (node (ref "B1") (pin "-") (pinfunction "-_-") (pintype "passive"))
      (node (ref "C1") (pin "2") (pinfunction "2_2") (pintype "passive"))
      (node (ref "C10") (pin "1") (pinfunction "1_1") (pintype "passive"))
      (node (ref "C11") (pin "2") (pinfunction "2_2") (pintype "passive"))
      (node (ref "C114") (pin "1") (pinfunction "1_1") (pintype "passive"))
      (node (ref "C115") (pin "1") (pinfunction "1_1") (pintype "passive"))
      (node (ref "C12") (pin "2") (pinfunction "2_2") (pintype "passive"))
      (node (ref "C121") (pin "1") (pinfunction "1_1") (pintype "passive"))
      (node (ref "C122") (pin "2") (pinfunction "2_2") (pintype "passive"))
      (node (ref "C123") (pin "2") (pinfunction "2_2") (pintype "passive"))
      (node (ref "C125") (pin "2") (pinfunction "2_2") (pintype "passive"))
      (node (ref "C127") (pin "2") (pinfunction "2_2") (pintype "passive"))
      (node (ref "C128") (pin "2") (pinfunction "2_2") (pintype "passive"))
      (node (ref "C129") (pin "2") (pinfunction "2_2") (pintype "passive"))
      (node (ref "C13") (pin "2") (pinfunction "2_2") (pintype "passive"))
      (node (ref "C130") (pin "2") (pinfunction "2_2") (pintype "passive"))
      (node (ref "C131") (pin "2") (pinfunction "2_2") (pintype "passive"))
      (node (ref "C132") (pin "2") (pinfunction "2_2") (pintype "passive"))
      (node (ref "C133") (pin "2") (pinfunction "2_2") (pintype "passive"))
      (node (ref "C134") (pin "2") (pinfunction "2_2") (pintype "passive"))
      (node (ref "C135") (pin "2") (pinfunction "2_2") (pintype "passive"))
      (node (ref "C136") (pin "2") (pinfunction "2_2") (pintype "passive"))
      (node (ref "C137") (pin "2") (pinfunction "2_2") (pintype "passive"))
      (node (ref "C139") (pin "2") (pinfunction "2_2") (pintype "passive"))
      (node (ref "C14") (pin "2") (pinfunction "2_2") (pintype "passive"))
      (node (ref "C141") (pin "2") (pinfunction "2_2") (pintype "passive"))
      (node (ref "C142") (pin "2") (pinfunction "2_2") (pintype "passive"))
      (node (ref "C143") (pin "2") (pinfunction "2_2") (pintype "passive"))
      (node (ref "C144") (pin "2") (pinfunction "2_2") (pintype "passive"))
      (node (ref "C145") (pin "2") (pinfunction "2_2") (pintype "passive"))
      (node (ref "C146") (pin "2") (pinfunction "2_2") (pintype "passive"))
      (node (ref "C147") (pin "2") (pinfunction "2_2") (pintype "passive"))
      (node (ref "C148") (pin "2") (pinfunction "2_2") (pintype "passive"))
      (node (ref "C149") (pin "2") (pinfunction "2_2") (pintype "passive"))
      (node (ref "C150") (pin "2") (pinfunction "2_2") (pintype "passive"))
      (node (ref "C152") (pin "2") (pinfunction "2_2") (pintype "passive"))
      (node (ref "C153") (pin "2") (pinfunction "2_2") (pintype "passive"))
      (node (ref "C154") (pin "2") (pinfunction "2_2") (pintype "passive"))
      (node (ref "C156") (pin "2") (pinfunction "PIN-_2") (pintype "passive"))
      (node (ref "C157") (pin "2") (pinfunction "2_2") (pintype "passive"))
      (node (ref "C158") (pin "2") (pinfunction "2_2") (pintype "passive"))
      (node (ref "C16") (pin "1") (pinfunction "1_1") (pintype "passive"))
      (node (ref "C163") (pin "2") (pinfunction "2_2") (pintype "passive"))
      (node (ref "C164") (pin "2") (pinfunction "2_2") (pintype "passive"))
      (node (ref "C17") (pin "2") (pinfunction "2_2") (pintype "passive"))
      (node (ref "C18") (pin "1") (pinfunction "1_1") (pintype "passive"))
      (node (ref "C187") (pin "-") (pinfunction "-_-") (pintype "passive"))
      (node (ref "C19") (pin "1") (pinfunction "1_1") (pintype "passive"))
      (node (ref "C2") (pin "2") (pinfunction "2_2") (pintype "passive"))
      (node (ref "C20") (pin "1") (pinfunction "1_1") (pintype "passive"))
      (node (ref "C21") (pin "2") (pinfunction "2_2") (pintype "passive"))
      (node (ref "C22") (pin "2") (pinfunction "2_2") (pintype "passive"))
      (node (ref "C23") (pin "2") (pinfunction "2_2") (pintype "passive"))
      (node (ref "C24") (pin "2") (pinfunction "2_2") (pintype "passive"))
      (node (ref "C25") (pin "2") (pinfunction "2_2") (pintype "passive"))
      (node (ref "C26") (pin "2") (pinfunction "2_2") (pintype "passive"))
      (node (ref "C27") (pin "2") (pinfunction "2_2") (pintype "passive"))
      (node (ref "C28") (pin "2") (pinfunction "2_2") (pintype "passive"))
      (node (ref "C29") (pin "1") (pinfunction "1_1") (pintype "passive"))
      (node (ref "C3") (pin "2") (pinfunction "2_2") (pintype "passive"))
      (node (ref "C32") (pin "2") (pinfunction "2_2") (pintype "passive"))
      (node (ref "C33") (pin "2") (pinfunction "2_2") (pintype "passive"))
      (node (ref "C34") (pin "2") (pinfunction "2_2") (pintype "passive"))
      (node (ref "C35") (pin "1") (pinfunction "1_1") (pintype "passive"))
      (node (ref "C36") (pin "2") (pinfunction "2_2") (pintype "passive"))
      (node (ref "C37") (pin "2") (pinfunction "2_2") (pintype "passive"))
      (node (ref "C38") (pin "1") (pinfunction "1_1") (pintype "passive"))
      (node (ref "C4") (pin "2") (pinfunction "2_2") (pintype "passive"))
      (node (ref "C40") (pin "2") (pinfunction "2_2") (pintype "passive"))
      (node (ref "C42") (pin "2") (pinfunction "2_2") (pintype "passive"))
      (node (ref "C43") (pin "-") (pinfunction "-_-") (pintype "passive"))
      (node (ref "C44") (pin "-") (pinfunction "-_-") (pintype "passive"))
      (node (ref "C47") (pin "2") (pinfunction "2_2") (pintype "passive"))
      (node (ref "C48") (pin "2") (pinfunction "2_2") (pintype "passive"))
      (node (ref "C5") (pin "2") (pinfunction "2_2") (pintype "passive"))
      (node (ref "C59") (pin "2") (pinfunction "2_2") (pintype "passive"))
      (node (ref "C6") (pin "2") (pinfunction "2_2") (pintype "passive"))
      (node (ref "C7") (pin "2") (pinfunction "2_2") (pintype "passive"))
      (node (ref "C8") (pin "2") (pinfunction "2_2") (pintype "passive"))
      (node (ref "C9") (pin "2") (pinfunction "2_2") (pintype "passive"))
      (node (ref "D21") (pin "-") (pinfunction "A_-") (pintype "passive"))
      (node (ref "D27") (pin "-") (pinfunction "A_-") (pintype "passive"))
      (node (ref "D28") (pin "-") (pinfunction "A_-") (pintype "passive"))
      (node (ref "D30") (pin "A") (pinfunction "A_A") (pintype "passive"))
      (node (ref "D31") (pin "1") (pinfunction "A_1") (pintype "passive"))
      (node (ref "D31") (pin "2") (pinfunction "A_2") (pintype "passive"))
      (node (ref "D32") (pin "A") (pinfunction "A_A") (pintype "passive"))
      (node (ref "D4") (pin "A") (pinfunction "A_A") (pintype "passive"))
      (node (ref "H1") (pin "P1") (pinfunction "P$1_P1") (pintype "bidirectional"))
      (node (ref "H2") (pin "P1") (pinfunction "P$1_P1") (pintype "bidirectional"))
      (node (ref "H3") (pin "P1") (pinfunction "P$1_P1") (pintype "bidirectional"))
      (node (ref "H4") (pin "P1") (pinfunction "P$1_P1") (pintype "bidirectional"))
      (node (ref "H5") (pin "P1") (pinfunction "P$1_P1") (pintype "bidirectional"))
      (node (ref "IC1") (pin "3") (pinfunction "GND_3") (pintype "power_in"))
      (node (ref "IC18") (pin "18") (pinfunction "GND2_18") (pintype "power_in"))
      (node (ref "IC18") (pin "21") (pinfunction "GND3_21") (pintype "power_in"))
      (node (ref "IC18") (pin "25") (pinfunction "AGND_25") (pintype "power_in"))
      (node (ref "IC18") (pin "26") (pinfunction "TEST_26") (pintype "bidirectional"))
      (node (ref "IC18") (pin "7") (pinfunction "GND1_7") (pintype "power_in"))
      (node (ref "IC19") (pin "4") (pinfunction "V-_4") (pintype "power_in"))
      (node (ref "IC2") (pin "5") (pinfunction "GND_5") (pintype "power_in"))
      (node (ref "IC21") (pin "4") (pinfunction "GND_4") (pintype "power_in"))
      (node (ref "IC3") (pin "15") (pinfunction "VSS15_15") (pintype "power_in"))
      (node (ref "IC3") (pin "31") (pinfunction "AVSS_31") (pintype "power_in"))
      (node (ref "IC3") (pin "36") (pinfunction "VSS36_36") (pintype "power_in"))
      (node (ref "IC3") (pin "45") (pinfunction "VSS45_45") (pintype "power_in"))
      (node (ref "IC3") (pin "65") (pinfunction "VSS65_65") (pintype "power_in"))
      (node (ref "IC3") (pin "75") (pinfunction "VSS75_75") (pintype "power_in"))
      (node (ref "IC4") (pin "2") (pinfunction "VSS_2") (pintype "power_in"))
      (node (ref "IC5") (pin "4") (pinfunction "GND_4") (pintype "power_in"))
      (node (ref "IC5") (pin "5") (pinfunction "A2_5") (pintype "input"))
      (node (ref "IC5") (pin "6") (pinfunction "A1_6") (pintype "input"))
      (node (ref "IC6") (pin "1") (pinfunction "A0_1") (pintype "input"))
      (node (ref "IC6") (pin "2") (pinfunction "A1_2") (pintype "input"))
      (node (ref "IC6") (pin "3") (pinfunction "A2_3") (pintype "input"))
      (node (ref "IC6") (pin "4") (pinfunction "GND_4") (pintype "power_in"))
      (node (ref "IC6") (pin "7") (pinfunction "WP_7") (pintype "input"))
      (node (ref "IC7") (pin "12") (pinfunction "CLKOE_12") (pintype "input"))
      (node (ref "IC7") (pin "7") (pinfunction "VSS_7") (pintype "power_in"))
      (node (ref "IC8") (pin "4") (pinfunction "GND_4") (pintype "power_in"))
      (node (ref "IC9") (pin "2") (pinfunction "GND_2") (pintype "power_in"))
      (node (ref "J1") (pin "1") (pinfunction "1_1") (pintype "passive"))
      (node (ref "J10") (pin "C5") (pinfunction "C5_C5") (pintype "bidirectional"))
      (node (ref "J11") (pin "3") (pinfunction "3_3") (pintype "passive"))
      (node (ref "J12") (pin "3") (pinfunction "3_3") (pintype "passive"))
      (node (ref "J15") (pin "10") (pinfunction "10_10") (pintype "bidirectional"))
      (node (ref "J15") (pin "10A") (pinfunction "10_10A") (pintype "bidirectional"))
      (node (ref "J18") (pin "6") (pinfunction "6_6") (pintype "bidirectional"))
      (node (ref "J18") (pin "9") (pinfunction "9_9") (pintype "bidirectional"))
      (node (ref "J19") (pin "1") (pinfunction "1_1") (pintype "bidirectional"))
      (node (ref "J19") (pin "11") (pinfunction "11_11") (pintype "bidirectional"))
      (node (ref "J19") (pin "3") (pinfunction "3_3") (pintype "bidirectional"))
      (node (ref "J19") (pin "5") (pinfunction "5_5") (pintype "bidirectional"))
      (node (ref "J19") (pin "7") (pinfunction "7_7") (pintype "bidirectional"))
      (node (ref "J19") (pin "9") (pinfunction "9_9") (pintype "bidirectional"))
      (node (ref "J2") (pin "1") (pinfunction "1_1") (pintype "passive"))
      (node (ref "J3") (pin "11") (pinfunction "11_11") (pintype "bidirectional"))
      (node (ref "J3") (pin "12") (pinfunction "12_12") (pintype "bidirectional"))
      (node (ref "J3") (pin "5") (pinfunction "5_5") (pintype "bidirectional"))
      (node (ref "J3") (pin "7") (pinfunction "7_7") (pintype "bidirectional"))
      (node (ref "J3") (pin "8") (pinfunction "8_8") (pintype "bidirectional"))
      (node (ref "J30") (pin "7") (pinfunction "GND_7") (pintype "bidirectional"))
      (node (ref "J41") (pin "1") (pinfunction "1_1") (pintype "passive"))
      (node (ref "J45") (pin "1") (pinfunction "1_1") (pintype "passive"))
      (node (ref "J50") (pin "1") (pinfunction "1_1") (pintype "bidirectional"))
      (node (ref "J50") (pin "2") (pinfunction "2_2") (pintype "bidirectional"))
      (node (ref "J7") (pin "1") (pinfunction "1_1") (pintype "passive"))
      (node (ref "J7") (pin "6") (pinfunction "6_6") (pintype "passive"))
      (node (ref "J8") (pin "9") (pinfunction "9_9") (pintype "passive"))
      (node (ref "J9") (pin "1") (pinfunction "1_1") (pintype "passive"))
      (node (ref "J9") (pin "6") (pinfunction "6_6") (pintype "passive"))
      (node (ref "JP1") (pin "1") (pinfunction "1_1") (pintype "passive"))
      (node (ref "L17") (pin "1") (pinfunction "1_1") (pintype "passive"))
      (node (ref "Q14") (pin "1") (pinfunction "GND_1") (pintype "power_in"))
      (node (ref "Q14") (pin "2") (pinfunction "GND1_2") (pintype "power_in"))
      (node (ref "Q15") (pin "1") (pinfunction "S_1") (pintype "passive"))
      (node (ref "Q16") (pin "EP") (pinfunction "PGND_EP") (pintype "passive"))
      (node (ref "Q18") (pin "1") (pinfunction "S_1") (pintype "passive"))
      (node (ref "Q19") (pin "EP") (pinfunction "PGND_EP") (pintype "passive"))
      (node (ref "Q2") (pin "1") (pinfunction "Q1S_1") (pintype "bidirectional"))
      (node (ref "Q20") (pin "2") (pinfunction "S_2") (pintype "passive"))
      (node (ref "Q21") (pin "2") (pinfunction "S_2") (pintype "passive"))
      (node (ref "Q3") (pin "1") (pinfunction "1_1") (pintype "passive"))
      (node (ref "Q5") (pin "1") (pinfunction "Q1S_1") (pintype "bidirectional"))
      (node (ref "R10") (pin "1") (pinfunction "1_1") (pintype "passive"))
      (node (ref "R13") (pin "1") (pinfunction "1_1") (pintype "passive"))
      (node (ref "R162") (pin "1") (pinfunction "1_1") (pintype "passive"))
      (node (ref "R165") (pin "1") (pinfunction "1_1") (pintype "passive"))
      (node (ref "R166") (pin "1") (pinfunction "1_1") (pintype "passive"))
      (node (ref "R174") (pin "2") (pinfunction "2_2") (pintype "passive"))
      (node (ref "R179") (pin "1") (pinfunction "1_1") (pintype "passive"))
      (node (ref "R182") (pin "1") (pinfunction "1_1") (pintype "passive"))
      (node (ref "R183") (pin "2") (pinfunction "2_2") (pintype "passive"))
      (node (ref "R184") (pin "2") (pinfunction "2_2") (pintype "passive"))
      (node (ref "R185") (pin "1") (pinfunction "1_1") (pintype "passive"))
      (node (ref "R197") (pin "2") (pinfunction "2_2") (pintype "passive"))
      (node (ref "R20") (pin "2") (pinfunction "1_2") (pintype "passive"))
      (node (ref "R21") (pin "5") (pinfunction "2_5") (pintype "passive"))
      (node (ref "R21") (pin "6") (pinfunction "2_6") (pintype "passive"))
      (node (ref "R22") (pin "1") (pinfunction "1_1") (pintype "passive"))
      (node (ref "R25") (pin "1") (pinfunction "1_1") (pintype "passive"))
      (node (ref "R29") (pin "5") (pinfunction "2_5") (pintype "passive"))
      (node (ref "R29") (pin "6") (pinfunction "2_6") (pintype "passive"))
      (node (ref "R5") (pin "1") (pinfunction "1_1") (pintype "passive"))
      (node (ref "R6") (pin "1") (pinfunction "1_1") (pintype "passive"))
      (node (ref "TP11") (pin "P$1") (pinfunction "TP_P$1") (pintype "passive"))
      (node (ref "TP12") (pin "1") (pinfunction "TP_1") (pintype "passive"))
      (node (ref "TP66") (pin "TP") (pinfunction "TP_TP") (pintype "input"))
      (node (ref "TP67") (pin "TP") (pinfunction "TP_TP") (pintype "input"))
      (node (ref "U1") (pin "10") (pinfunction "PGND_10") (pintype "bidirectional"))
      (node (ref "U1") (pin "21") (pinfunction "PRESB_21") (pintype "bidirectional"))
      (node (ref "U1") (pin "9") (pinfunction "SGND_9") (pintype "bidirectional"))
      (node (ref "U1") (pin "PAD") (pinfunction "PAD_PAD") (pintype "bidirectional"))
      (node (ref "U2") (pin "2") (pinfunction "GND_2") (pintype "bidirectional"))
      (node (ref "U2") (pin "3") (pinfunction "GND_3") (pintype "bidirectional"))
      (node (ref "U2") (pin "5") (pinfunction "INHIBIT_5") (pintype "bidirectional"))
      (node (ref "U2") (pin "6") (pinfunction "GND_6") (pintype "bidirectional"))
      (node (ref "U2") (pin "7") (pinfunction "GND_7") (pintype "bidirectional"))
      (node (ref "U3") (pin "3") (pinfunction "VSS_3") (pintype "bidirectional"))
      (node (ref "U6") (pin "16") (pinfunction "AGND_16") (pintype "power_in"))
      (node (ref "U6") (pin "9") (pinfunction "PGND_9") (pintype "power_in"))
      (node (ref "U6") (pin "EP") (pinfunction "PPAD_EP") (pintype "power_in"))
      (node (ref "U7") (pin "16") (pinfunction "AGND_16") (pintype "power_in"))
      (node (ref "U7") (pin "9") (pinfunction "PGND_9") (pintype "power_in"))
      (node (ref "U7") (pin "EP") (pinfunction "PPAD_EP") (pintype "power_in"))
      (node (ref "X1") (pin "7") (pinfunction "1_7") (pintype "passive"))
      (node (ref "X1") (pin "8") (pinfunction "1_8") (pintype "passive"))
      (node (ref "X2") (pin "4") (pinfunction "4_4") (pintype "passive"))
    )
    (net (code "53") (name "DIN_SM") (class "Default")
      (node (ref "IC3") (pin "6") (pinfunction "RC1/CN45/RPI38_6") (pintype "bidirectional"))
      (node (ref "U1") (pin "27") (pinfunction "DIN_27") (pintype "bidirectional"))
    )
    (net (code "54") (name "DOOR2_L") (class "Default")
      (node (ref "IC3") (pin "50") (pinfunction "CN18/RP17/RF5_50") (pintype "bidirectional"))
      (node (ref "R29") (pin "2") (pinfunction "1_2") (pintype "passive"))
      (node (ref "R29") (pin "3") (pinfunction "1_3") (pintype "passive"))
    )
    (net (code "55") (name "DOOR2_L_SW") (class "Default")
      (node (ref "C36") (pin "1") (pinfunction "1_1") (pintype "passive"))
      (node (ref "J19") (pin "2") (pinfunction "2_2") (pintype "bidirectional"))
      (node (ref "R27") (pin "2") (pinfunction "2_2") (pintype "passive"))
      (node (ref "R29") (pin "7") (pinfunction "2_7") (pintype "passive"))
    )
    (net (code "56") (name "DOOR2_R") (class "Default")
      (node (ref "IC3") (pin "55") (pinfunction "CN72/RPI45/RF6_55") (pintype "bidirectional"))
      (node (ref "R29") (pin "1") (pinfunction "1_1") (pintype "passive"))
      (node (ref "R29") (pin "4") (pinfunction "1_4") (pintype "passive"))
    )
    (net (code "57") (name "DOOR2_R_SW") (class "Default")
      (node (ref "C47") (pin "1") (pinfunction "1_1") (pintype "passive"))
      (node (ref "J19") (pin "4") (pinfunction "4_4") (pintype "bidirectional"))
      (node (ref "R28") (pin "2") (pinfunction "2_2") (pintype "passive"))
      (node (ref "R29") (pin "8") (pinfunction "2_8") (pintype "passive"))
    )
    (net (code "58") (name "DOOR_L") (class "Default")
      (node (ref "IC3") (pin "73") (pinfunction "RC13/SOSCI/CN1_73") (pintype "bidirectional"))
      (node (ref "R21") (pin "2") (pinfunction "1_2") (pintype "passive"))
      (node (ref "R21") (pin "3") (pinfunction "1_3") (pintype "passive"))
    )
    (net (code "59") (name "DOOR_L_SW") (class "Default")
      (node (ref "C25") (pin "1") (pinfunction "1_1") (pintype "passive"))
      (node (ref "J19") (pin "6") (pinfunction "6_6") (pintype "bidirectional"))
      (node (ref "R18") (pin "2") (pinfunction "2_2") (pintype "passive"))
      (node (ref "R21") (pin "7") (pinfunction "2_7") (pintype "passive"))
    )
    (net (code "60") (name "DOOR_ON") (class "Default")
      (node (ref "IC3") (pin "87") (pinfunction "CN68/RF0_87") (pintype "bidirectional"))
      (node (ref "Q5") (pin "5") (pinfunction "Q1G_5") (pintype "input"))
      (node (ref "R20") (pin "7") (pinfunction "2_7") (pintype "passive"))
    )
    (net (code "61") (name "DOOR_R") (class "Default")
      (node (ref "IC3") (pin "91") (pinfunction "RA6/CN39_91") (pintype "bidirectional"))
      (node (ref "R21") (pin "1") (pinfunction "1_1") (pintype "passive"))
      (node (ref "R21") (pin "4") (pinfunction "1_4") (pintype "passive"))
    )
    (net (code "62") (name "DOOR_R_SW") (class "Default")
      (node (ref "C26") (pin "1") (pinfunction "1_1") (pintype "passive"))
      (node (ref "J19") (pin "8") (pinfunction "8_8") (pintype "bidirectional"))
      (node (ref "R19") (pin "2") (pinfunction "2_2") (pintype "passive"))
      (node (ref "R21") (pin "8") (pinfunction "2_8") (pintype "passive"))
    )
    (net (code "63") (name "DOUT_SM_B") (class "Default")
      (node (ref "IC3") (pin "7") (pinfunction "RC2/CN46/RPI39_7") (pintype "bidirectional"))
      (node (ref "U1") (pin "28") (pinfunction "DOUT_28") (pintype "bidirectional"))
    )
    (net (code "64") (name "ID1_L_N") (class "Default")
      (node (ref "C31") (pin "2") (pinfunction "2_2") (pintype "passive"))
      (node (ref "IC9") (pin "3") (pinfunction "FB_3") (pintype "input"))
      (node (ref "J14") (pin "1") (pinfunction "1_1") (pintype "passive"))
      (node (ref "J18") (pin "8") (pinfunction "8_8") (pintype "bidirectional"))
      (node (ref "R25") (pin "2") (pinfunction "2_2") (pintype "passive"))
    )
    (net (code "65") (name "ID_L_P") (class "Default")
      (node (ref "C31") (pin "1") (pinfunction "1_1") (pintype "passive"))
      (node (ref "C32") (pin "1") (pinfunction "1_1") (pintype "passive"))
      (node (ref "D3") (pin "A") (pinfunction "A_A") (pintype "passive"))
      (node (ref "J14") (pin "2") (pinfunction "2_2") (pintype "passive"))
      (node (ref "J18") (pin "7") (pinfunction "7_7") (pintype "bidirectional"))
      (node (ref "L3") (pin "2") (pinfunction "2_2") (pintype "passive"))
    )
    (net (code "66") (name "ID_PWM") (class "Default")
      (node (ref "IC3") (pin "51") (pinfunction "CN71/RP16/RF3_51") (pintype "bidirectional"))
      (node (ref "R23") (pin "1") (pinfunction "1_1") (pintype "passive"))
    )
    (net (code "67") (name "IOB") (class "Default")
      (node (ref "J10") (pin "C7") (pinfunction "C7_C7") (pintype "bidirectional"))
      (node (ref "U1") (pin "20") (pinfunction "IOB_20") (pintype "bidirectional"))
    )
    (net (code "68") (name "ISENSEA") (class "Default")
      (node (ref "IC19") (pin "1") (pinfunction "OUT_1") (pintype "output"))
      (node (ref "IC19") (pin "2") (pinfunction "-IN_2") (pintype "input"))
      (node (ref "IC3") (pin "43") (pinfunction "RB14/AN14/CN32/RP14_43") (pintype "bidirectional"))
    )
    (net (code "69") (name "ISEN_OP_EN") (class "Default")
      (node (ref "C134") (pin "1") (pinfunction "1_1") (pintype "passive"))
      (node (ref "IC19") (pin "8") (pinfunction "V+_8") (pintype "power_in"))
      (node (ref "IC3") (pin "68") (pinfunction "CN53/RP2/RD8_68") (pintype "bidirectional"))
    )
    (net (code "70") (name "LD_SM") (class "Default")
      (node (ref "IC3") (pin "9") (pinfunction "RC4/CN48/RPI41_9") (pintype "bidirectional"))
      (node (ref "U1") (pin "25") (pinfunction "/LD_25") (pintype "bidirectional"))
    )
    (net (code "71") (name "MICROPHONE") (class "Default")
      (node (ref "J17") (pin "2") (pinfunction "2_2") (pintype "bidirectional"))
      (node (ref "J48") (pin "2") (pinfunction "2_2") (pintype "passive"))
      (node (ref "R207") (pin "2") (pinfunction "2_2") (pintype "passive"))
      (node (ref "R208") (pin "1") (pinfunction "1_1") (pintype "passive"))
      (node (ref "U9") (pin "3") (pinfunction "+IN_3") (pintype "input"))
    )
    (net (code "72") (name "MIC_AMP_EN") (class "Default")
      (node (ref "IC3") (pin "96") (pinfunction "CN79/RG12_96") (pintype "bidirectional"))
      (node (ref "J49") (pin "1") (pinfunction "1_1") (pintype "passive"))
      (node (ref "Q24") (pin "1") (pinfunction "G_1") (pintype "passive"))
      (node (ref "R210") (pin "1") (pinfunction "1_1") (pintype "passive"))
      (node (ref "U9") (pin "5") (pinfunction "~{SHDN}_5") (pintype "power_in"))
    )
    (net (code "73") (name "N$5") (class "Default")
      (node (ref "J15") (pin "6") (pinfunction "6_6") (pintype "bidirectional"))
      (node (ref "J15") (pin "6A") (pinfunction "6_6A") (pintype "bidirectional"))
      (node (ref "J15") (pin "8") (pinfunction "8_8") (pintype "bidirectional"))
      (node (ref "J15") (pin "8A") (pinfunction "8_8A") (pintype "bidirectional"))
      (node (ref "R38") (pin "2") (pinfunction "2_2") (pintype "passive"))
    )
    (net (code "74") (name "N$10") (class "Default")
      (node (ref "IC19") (pin "3") (pinfunction "+IN_3") (pintype "input"))
      (node (ref "IC19") (pin "5") (pinfunction "+IN_5") (pintype "input"))
      (node (ref "Q14") (pin "3") (pinfunction "OUT_3") (pintype "output"))
    )
    (net (code "75") (name "N$41") (class "Default")
      (node (ref "J15") (pin "2") (pinfunction "2_2") (pintype "bidirectional"))
      (node (ref "J15") (pin "2A") (pinfunction "2_2A") (pintype "bidirectional"))
      (node (ref "J15") (pin "4") (pinfunction "4_4") (pintype "bidirectional"))
      (node (ref "J15") (pin "4A") (pinfunction "4_4A") (pintype "bidirectional"))
      (node (ref "R39") (pin "2") (pinfunction "2_2") (pintype "passive"))
    )
    (net (code "76") (name "Net-(C164-Pad1)") (class "Default")
      (node (ref "C164") (pin "1") (pinfunction "1_1") (pintype "passive"))
      (node (ref "R193") (pin "1") (pinfunction "1_1") (pintype "passive"))
    )
    (net (code "77") (name "Net-(C171-Pad1)") (class "Default")
      (node (ref "C171") (pin "1") (pinfunction "1_1") (pintype "passive"))
      (node (ref "R198") (pin "1") (pinfunction "1_1") (pintype "passive"))
      (node (ref "R199") (pin "2") (pinfunction "2_2") (pintype "passive"))
      (node (ref "U8") (pin "7") (pinfunction "AVCC_7") (pintype "power_in"))
    )
    (net (code "78") (name "Net-(C185-Pad2)") (class "Default")
      (node (ref "C185") (pin "2") (pinfunction "2_2") (pintype "passive"))
      (node (ref "R211") (pin "1") (pinfunction "1_1") (pintype "passive"))
    )
    (net (code "79") (name "Net-(D1-A1)") (class "Default")
      (node (ref "B1") (pin "+") (pinfunction "+_+") (pintype "passive"))
      (node (ref "D1") (pin "1") (pinfunction "A1_1") (pintype "passive"))
      (node (ref "TP7") (pin "P$1") (pinfunction "TP_P$1") (pintype "passive"))
    )
    (net (code "80") (name "Net-(D1-K)") (class "Default")
      (node (ref "C24") (pin "1") (pinfunction "1_1") (pintype "passive"))
      (node (ref "D1") (pin "3") (pinfunction "K_3") (pintype "passive"))
      (node (ref "IC7") (pin "14") (pinfunction "VDD_14") (pintype "power_in"))
    )
    (net (code "81") (name "Net-(D2-K)") (class "Default")
      (node (ref "C30") (pin "1") (pinfunction "1_1") (pintype "passive"))
      (node (ref "D2") (pin "C") (pinfunction "K_C") (pintype "passive"))
      (node (ref "D3") (pin "C") (pinfunction "K_C") (pintype "passive"))
      (node (ref "IC9") (pin "1") (pinfunction "BOOST_1") (pintype "input"))
    )
    (net (code "82") (name "Net-(D17-A)") (class "Default")
      (node (ref "D17") (pin "2") (pinfunction "A_2") (pintype "passive"))
      (node (ref "R151") (pin "1") (pinfunction "1_1") (pintype "passive"))
    )
    (net (code "83") (name "Net-(D17-K)") (class "Default")
      (node (ref "D17") (pin "1+") (pinfunction "K_1+") (pintype "passive"))
      (node (ref "IC18") (pin "22") (pinfunction "GPIO0_22") (pintype "output"))
    )
    (net (code "84") (name "Net-(D19-A)") (class "Default")
      (node (ref "D19") (pin "2") (pinfunction "A_2") (pintype "passive"))
      (node (ref "R152") (pin "1") (pinfunction "1_1") (pintype "passive"))
    )
    (net (code "85") (name "Net-(D19-K)") (class "Default")
      (node (ref "D19") (pin "1+") (pinfunction "K_1+") (pintype "passive"))
      (node (ref "IC18") (pin "23") (pinfunction "GPIO1_23") (pintype "output"))
    )
    (net (code "86") (name "Net-(D23-A)") (class "Default")
      (node (ref "D23") (pin "2") (pinfunction "A_2") (pintype "passive"))
      (node (ref "R175") (pin "1") (pinfunction "1_1") (pintype "passive"))
    )
    (net (code "87") (name "Net-(D24-A)") (class "Default")
      (node (ref "D24") (pin "2") (pinfunction "A_2") (pintype "passive"))
      (node (ref "R176") (pin "1") (pinfunction "1_1") (pintype "passive"))
    )
    (net (code "88") (name "Net-(IC1-VIN)") (class "Default")
      (node (ref "C23") (pin "1") (pinfunction "1_1") (pintype "passive"))
      (node (ref "C59") (pin "1") (pinfunction "1_1") (pintype "passive"))
      (node (ref "IC1") (pin "1") (pinfunction "VIN_1") (pintype "power_in"))
      (node (ref "R37") (pin "1") (pinfunction "1_1") (pintype "passive"))
    )
    (net (code "89") (name "Net-(IC3-AVDD)") (class "Default")
      (node (ref "C3") (pin "1") (pinfunction "1_1") (pintype "passive"))
      (node (ref "C7") (pin "1") (pinfunction "1_1") (pintype "passive"))
      (node (ref "IC3") (pin "30") (pinfunction "AVDD_30") (pintype "power_in"))
      (node (ref "R1") (pin "1") (pinfunction "1_1") (pintype "passive"))
    )
    (net (code "90") (name "Net-(IC3-OSC1{slash}CLKI{slash}RC12)") (class "Default")
      (node (ref "C18") (pin "2") (pinfunction "2_2") (pintype "passive"))
      (node (ref "IC3") (pin "63") (pinfunction "OSC1/CLKI/RC12_63") (pintype "bidirectional"))
      (node (ref "Q4") (pin "3") (pinfunction "2_3") (pintype "passive"))
    )
    (net (code "91") (name "Net-(IC3-OSC2{slash}CLKO{slash}RC15)") (class "Default")
      (node (ref "C19") (pin "2") (pinfunction "2_2") (pintype "passive"))
      (node (ref "IC3") (pin "64") (pinfunction "OSC2/CLKO/RC15_64") (pintype "bidirectional"))
      (node (ref "Q4") (pin "1") (pinfunction "1_1") (pintype "passive"))
    )
    (net (code "92") (name "Net-(IC3-RA4{slash}TDI{slash}CN37)") (class "Default")
      (node (ref "IC3") (pin "60") (pinfunction "RA4/TDI/CN37_60") (pintype "bidirectional"))
      (node (ref "TP2") (pin "P$1") (pinfunction "TP_P$1") (pintype "passive"))
    )
    (net (code "93") (name "Net-(IC3-RB10{slash}AN10{slash}CN28{slash}CVREF)") (class "Default")
      (node (ref "IC3") (pin "34") (pinfunction "RB10/AN10/CN28/CVREF_34") (pintype "bidirectional"))
      (node (ref "TP3") (pin "P$1") (pinfunction "TP_P$1") (pintype "passive"))
    )
    (net (code "94") (name "Net-(IC3-VDDCORE)") (class "Default")
      (node (ref "C10") (pin "2") (pinfunction "2_2") (pintype "passive"))
      (node (ref "C38") (pin "2") (pinfunction "2_2") (pintype "passive"))
      (node (ref "IC3") (pin "85") (pinfunction "VDDCORE_85") (pintype "passive"))
    )
    (net (code "95") (name "Net-(IC4-VDD)") (class "Default")
      (node (ref "C21") (pin "1") (pinfunction "1_1") (pintype "passive"))
      (node (ref "IC4") (pin "5") (pinfunction "VDD_5") (pintype "power_in"))
      (node (ref "J12") (pin "2") (pinfunction "2_2") (pintype "passive"))
      (node (ref "R15") (pin "1") (pinfunction "1_1") (pintype "passive"))
    )
    (net (code "96") (name "Net-(IC7-OSCI)") (class "Default")
      (node (ref "IC7") (pin "1") (pinfunction "OSCI_1") (pintype "input"))
      (node (ref "Q6") (pin "2") (pinfunction "2_2") (pintype "passive"))
    )
    (net (code "97") (name "Net-(IC7-OSCO)") (class "Default")
      (node (ref "IC7") (pin "2") (pinfunction "OSCO_2") (pintype "output"))
      (node (ref "Q6") (pin "1") (pinfunction "1_1") (pintype "passive"))
    )
    (net (code "98") (name "Net-(IC9-EN{slash}DIM)") (class "Default")
      (node (ref "C34") (pin "1") (pinfunction "1_1") (pintype "passive"))
      (node (ref "IC9") (pin "4") (pinfunction "EN/DIM_4") (pintype "input"))
      (node (ref "R23") (pin "2") (pinfunction "2_2") (pintype "passive"))
    )
    (net (code "99") (name "Net-(IC9-SW)") (class "Default")
      (node (ref "C30") (pin "2") (pinfunction "2_2") (pintype "passive"))
      (node (ref "D4") (pin "K") (pinfunction "K_K") (pintype "passive"))
      (node (ref "IC9") (pin "6") (pinfunction "SW_6") (pintype "output"))
      (node (ref "L3") (pin "1") (pinfunction "1_1") (pintype "passive"))
    )
    (net (code "100") (name "Net-(IC18-VCC30)") (class "Default")
      (node (ref "C121") (pin "2") (pinfunction "2_2") (pintype "passive"))
      (node (ref "IC18") (pin "17") (pinfunction "VCC30_17") (pintype "power_in"))
      (node (ref "IC18") (pin "4") (pinfunction "VCCIO_4") (pintype "power_in"))
      (node (ref "TP60") (pin "P$1") (pinfunction "TP_P$1") (pintype "passive"))
    )
    (net (code "101") (name "Net-(IC19B--IN)") (class "Default")
      (node (ref "IC19") (pin "6") (pinfunction "-IN_6") (pintype "input"))
      (node (ref "IC19") (pin "7") (pinfunction "OUT_7") (pintype "output"))
    )
    (net (code "102") (name "Net-(IC21-ITH)") (class "Default")
      (node (ref "IC21") (pin "2") (pinfunction "ITH_2") (pintype "input"))
      (node (ref "R193") (pin "2") (pinfunction "2_2") (pintype "passive"))
    )
    (net (code "103") (name "Net-(IC21-PGATE)") (class "Default")
      (node (ref "IC21") (pin "5") (pinfunction "PGATE_5") (pintype "output"))
      (node (ref "Q23") (pin "1") (pinfunction "G_1") (pintype "passive"))
    )
    (net (code "104") (name "Net-(IC21-SENSE)") (class "Default")
      (node (ref "C155") (pin "2") (pinfunction "2_2") (pintype "passive"))
      (node (ref "IC21") (pin "7") (pinfunction "SENSE_7") (pintype "input"))
      (node (ref "Q23") (pin "2") (pinfunction "S_2") (pintype "passive"))
      (node (ref "R189") (pin "1") (pinfunction "1_1") (pintype "passive"))
    )
    (net (code "105") (name "Net-(IC21-VFB)") (class "Default")
      (node (ref "C160") (pin "1") (pinfunction "1_1") (pintype "passive"))
      (node (ref "IC21") (pin "3") (pinfunction "VFB_3") (pintype "input"))
      (node (ref "R194") (pin "2") (pinfunction "2_2") (pintype "passive"))
      (node (ref "R197") (pin "1") (pinfunction "1_1") (pintype "passive"))
    )
    (net (code "106") (name "Net-(J45-Pad2)") (class "Default")
      (node (ref "J45") (pin "2") (pinfunction "2_2") (pintype "passive"))
      (node (ref "R46") (pin "2") (pinfunction "2_2") (pintype "passive"))
    )
    (net (code "107") (name "Net-(J45-Pad3)") (class "Default")
      (node (ref "J45") (pin "3") (pinfunction "3_3") (pintype "passive"))
      (node (ref "R45") (pin "2") (pinfunction "2_2") (pintype "passive"))
    )
    (net (code "108") (name "Net-(Q2-Q2G)") (class "Default")
      (node (ref "Q2") (pin "6") (pinfunction "Q2G_6") (pintype "input"))
      (node (ref "R3") (pin "2") (pinfunction "2_2") (pintype "passive"))
    )
    (net (code "109") (name "Net-(Q5-Q2D1)") (class "Default")
      (node (ref "Q5") (pin "2") (pinfunction "Q2D1_2") (pintype "bidirectional"))
      (node (ref "Q5") (pin "3") (pinfunction "Q2D2_3") (pintype "bidirectional"))
      (node (ref "R18") (pin "1") (pinfunction "1_1") (pintype "passive"))
      (node (ref "R19") (pin "1") (pinfunction "1_1") (pintype "passive"))
      (node (ref "R27") (pin "1") (pinfunction "1_1") (pintype "passive"))
      (node (ref "R28") (pin "1") (pinfunction "1_1") (pintype "passive"))
    )
    (net (code "110") (name "Net-(Q5-Q2G)") (class "Default")
      (node (ref "Q5") (pin "6") (pinfunction "Q2G_6") (pintype "input"))
      (node (ref "R20") (pin "3") (pinfunction "1_3") (pintype "passive"))
    )
    (net (code "111") (name "Net-(Q14-VIN+)") (class "Default")
      (node (ref "C187") (pin "+") (pinfunction "+_+") (pintype "passive"))
      (node (ref "D32") (pin "C") (pinfunction "C_C") (pintype "passive"))
      (node (ref "F3") (pin "2") (pinfunction "2_2") (pintype "passive"))
      (node (ref "Q14") (pin "5") (pinfunction "VIN+_5") (pintype "input"))
      (node (ref "R154") (pin "1") (pinfunction "1_1") (pintype "passive"))
      (node (ref "R40") (pin "1") (pinfunction "1_1") (pintype "passive"))
      (node (ref "R41") (pin "1") (pinfunction "1_1") (pintype "passive"))
      (node (ref "TP63") (pin "TP") (pinfunction "TP_TP") (pintype "input"))
    )
    (net (code "112") (name "Net-(Q15A-D)") (class "Default")
      (node (ref "Q15") (pin "7") (pinfunction "D_7") (pintype "passive"))
      (node (ref "Q15") (pin "8") (pinfunction "D1_8") (pintype "passive"))
      (node (ref "R159") (pin "1") (pinfunction "1_1") (pintype "passive"))
    )
    (net (code "113") (name "Net-(Q15B-D)") (class "Default")
      (node (ref "C122") (pin "1") (pinfunction "1_1") (pintype "passive"))
      (node (ref "C123") (pin "1") (pinfunction "1_1") (pintype "passive"))
      (node (ref "C125") (pin "1") (pinfunction "1_1") (pintype "passive"))
      (node (ref "Q15") (pin "5") (pinfunction "D_5") (pintype "passive"))
      (node (ref "Q15") (pin "6") (pinfunction "D1_6") (pintype "passive"))
      (node (ref "R157") (pin "2") (pinfunction "2_2") (pintype "passive"))
      (node (ref "R42") (pin "1") (pinfunction "1_1") (pintype "passive"))
      (node (ref "R43") (pin "1") (pinfunction "1_1") (pintype "passive"))
      (node (ref "U6") (pin "7") (pinfunction "VIN_7") (pintype "power_in"))
    )
    (net (code "114") (name "Net-(Q15B-G)") (class "Default")
      (node (ref "Q15") (pin "4") (pinfunction "G_4") (pintype "passive"))
      (node (ref "R156") (pin "1") (pinfunction "1_1") (pintype "passive"))
      (node (ref "R159") (pin "2") (pinfunction "2_2") (pintype "passive"))
    )
    (net (code "115") (name "Net-(Q18A-D)") (class "Default")
      (node (ref "Q18") (pin "7") (pinfunction "D_7") (pintype "passive"))
      (node (ref "Q18") (pin "8") (pinfunction "D1_8") (pintype "passive"))
      (node (ref "R173") (pin "2") (pinfunction "2_2") (pintype "passive"))
    )
    (net (code "116") (name "Net-(Q18B-D)") (class "Default")
      (node (ref "C136") (pin "1") (pinfunction "1_1") (pintype "passive"))
      (node (ref "C137") (pin "1") (pinfunction "1_1") (pintype "passive"))
      (node (ref "C139") (pin "1") (pinfunction "1_1") (pintype "passive"))
      (node (ref "Q18") (pin "5") (pinfunction "D_5") (pintype "passive"))
      (node (ref "Q18") (pin "6") (pinfunction "D1_6") (pintype "passive"))
      (node (ref "R171") (pin "2") (pinfunction "2_2") (pintype "passive"))
      (node (ref "R44") (pin "1") (pinfunction "1_1") (pintype "passive"))
      (node (ref "U7") (pin "7") (pinfunction "VIN_7") (pintype "power_in"))
    )
    (net (code "117") (name "Net-(Q18B-G)") (class "Default")
      (node (ref "Q18") (pin "4") (pinfunction "G_4") (pintype "passive"))
      (node (ref "R170") (pin "2") (pinfunction "2_2") (pintype "passive"))
      (node (ref "R173") (pin "1") (pinfunction "1_1") (pintype "passive"))
    )
    (net (code "118") (name "Net-(Q23-D)") (class "Default")
      (node (ref "D30") (pin "K") (pinfunction "K_K") (pintype "passive"))
      (node (ref "L14") (pin "1") (pinfunction "1_1") (pintype "passive"))
      (node (ref "Q23") (pin "3") (pinfunction "D_3") (pintype "passive"))
    )
    (net (code "119") (name "Net-(Q24-D)") (class "Default")
      (node (ref "Q24") (pin "3") (pinfunction "D_3") (pintype "passive"))
      (node (ref "R208") (pin "2") (pinfunction "2_2") (pintype "passive"))
    )
    (net (code "120") (name "Net-(R199-Pad1)") (class "Default")
      (node (ref "R199") (pin "1") (pinfunction "1_1") (pintype "passive"))
      (node (ref "U8") (pin "14") (pinfunction "AVCC_14") (pintype "power_in"))
    )
    (net (code "121") (name "Net-(TP69-TP)") (class "Default")
      (node (ref "R204") (pin "2") (pinfunction "2_2") (pintype "passive"))
      (node (ref "TP69") (pin "1") (pinfunction "TP_1") (pintype "passive"))
    )
    (net (code "122") (name "Net-(U1--UNDERV)") (class "Default")
      (node (ref "R12") (pin "1") (pinfunction "1_1") (pintype "passive"))
      (node (ref "U1") (pin "23") (pinfunction "-UNDERV_23") (pintype "bidirectional"))
    )
    (net (code "123") (name "Net-(U1-C+)") (class "Default")
      (node (ref "C15") (pin "2") (pinfunction "2_2") (pintype "passive"))
      (node (ref "U1") (pin "14") (pinfunction "C+_14") (pintype "bidirectional"))
    )
    (net (code "124") (name "Net-(U1-C-)") (class "Default")
      (node (ref "C15") (pin "1") (pinfunction "1_1") (pintype "passive"))
      (node (ref "U1") (pin "11") (pinfunction "C-_11") (pintype "bidirectional"))
    )
    (net (code "125") (name "Net-(U1-CLKB)") (class "Default")
      (node (ref "J10") (pin "C3") (pinfunction "C3_C3") (pintype "bidirectional"))
      (node (ref "U1") (pin "18") (pinfunction "CLKB_18") (pintype "bidirectional"))
    )
    (net (code "126") (name "Net-(U1-CPO)") (class "Default")
      (node (ref "C20") (pin "2") (pinfunction "2_2") (pintype "passive"))
      (node (ref "U1") (pin "15") (pinfunction "CPO_15") (pintype "bidirectional"))
    )
    (net (code "127") (name "Net-(U1-NC{slash}-NO)") (class "Default")
      (node (ref "R13") (pin "2") (pinfunction "2_2") (pintype "passive"))
      (node (ref "U1") (pin "22") (pinfunction "NC/-NO_22") (pintype "bidirectional"))
    )
    (net (code "128") (name "Net-(U1-RSTB)") (class "Default")
      (node (ref "J10") (pin "C2") (pinfunction "C2_C2") (pintype "bidirectional"))
      (node (ref "U1") (pin "19") (pinfunction "RSTB_19") (pintype "bidirectional"))
    )
    (net (code "129") (name "Net-(U1-VCCB)") (class "Default")
      (node (ref "J10") (pin "C1") (pinfunction "C1_C1") (pintype "bidirectional"))
      (node (ref "U1") (pin "17") (pinfunction "VCCB_17") (pintype "bidirectional"))
    )
    (net (code "130") (name "Net-(U3-AIN0)") (class "Default")
      (node (ref "C39") (pin "1") (pinfunction "1_1") (pintype "passive"))
      (node (ref "R33") (pin "1") (pinfunction "1_1") (pintype "passive"))
      (node (ref "R34") (pin "2") (pinfunction "2_2") (pintype "passive"))
      (node (ref "U3") (pin "4") (pinfunction "AIN0_4") (pintype "bidirectional"))
    )
    (net (code "131") (name "Net-(U3-AIN2)") (class "Default")
      (node (ref "C41") (pin "1") (pinfunction "1_1") (pintype "passive"))
      (node (ref "R35") (pin "1") (pinfunction "1_1") (pintype "passive"))
      (node (ref "R36") (pin "2") (pinfunction "2_2") (pintype "passive"))
      (node (ref "U3") (pin "6") (pinfunction "AIN2_6") (pintype "bidirectional"))
    )
    (net (code "132") (name "Net-(U9--IN)") (class "Default")
      (node (ref "C185") (pin "1") (pinfunction "1_1") (pintype "passive"))
      (node (ref "C186") (pin "1") (pinfunction "1_1") (pintype "passive"))
      (node (ref "R209") (pin "2") (pinfunction "2_2") (pintype "passive"))
      (node (ref "U9") (pin "4") (pinfunction "-IN_4") (pintype "input"))
    )
    (net (code "133") (name "Net-(U9-OUT)") (class "Default")
      (node (ref "C183") (pin "1") (pinfunction "1_1") (pintype "passive"))
      (node (ref "C184") (pin "1") (pinfunction "1_1") (pintype "passive"))
      (node (ref "C186") (pin "2") (pinfunction "2_2") (pintype "passive"))
      (node (ref "R209") (pin "1") (pinfunction "1_1") (pintype "passive"))
      (node (ref "U9") (pin "1") (pinfunction "OUT_1") (pintype "output"))
    )
    (net (code "134") (name "OUTN_UNF") (class "Default")
      (node (ref "C178") (pin "2") (pinfunction "2_2") (pintype "passive"))
      (node (ref "L16") (pin "2") (pinfunction "2_2") (pintype "passive"))
      (node (ref "U8") (pin "23") (pinfunction "OUTN_23") (pintype "output"))
      (node (ref "U8") (pin "25") (pinfunction "OUTN_25") (pintype "output"))
    )
    (net (code "135") (name "OUTP_UNF") (class "Default")
      (node (ref "C173") (pin "2") (pinfunction "2_2") (pintype "passive"))
      (node (ref "L15") (pin "2") (pinfunction "2_2") (pintype "passive"))
      (node (ref "U8") (pin "18") (pinfunction "OUTP_18") (pintype "output"))
      (node (ref "U8") (pin "20") (pinfunction "OUTP_20") (pintype "output"))
    )
    (net (code "136") (name "OUT_S1") (class "Default")
      (node (ref "D23") (pin "1+") (pinfunction "K_1+") (pintype "passive"))
      (node (ref "D25") (pin "A") (pinfunction "A_A") (pintype "passive"))
      (node (ref "J15") (pin "12") (pinfunction "12_12") (pintype "bidirectional"))
      (node (ref "J15") (pin "12A") (pinfunction "12_12A") (pintype "bidirectional"))
      (node (ref "Q20") (pin "3") (pinfunction "D_3") (pintype "passive"))
    )
    (net (code "137") (name "OUT_S2") (class "Default")
      (node (ref "D24") (pin "1+") (pinfunction "K_1+") (pintype "passive"))
      (node (ref "D26") (pin "A") (pinfunction "A_A") (pintype "passive"))
      (node (ref "J16") (pin "2") (pinfunction "2_2") (pintype "bidirectional"))
      (node (ref "J16") (pin "2A") (pinfunction "2_2A") (pintype "bidirectional"))
      (node (ref "Q21") (pin "3") (pinfunction "D_3") (pintype "passive"))
    )
    (net (code "138") (name "P12V") (class "Default")
      (node (ref "C128") (pin "1") (pinfunction "1_1") (pintype "passive"))
      (node (ref "C129") (pin "1") (pinfunction "1_1") (pintype "passive"))
      (node (ref "C130") (pin "1") (pinfunction "1_1") (pintype "passive"))
      (node (ref "C165") (pin "1") (pinfunction "1_1") (pintype "passive"))
      (node (ref "C166") (pin "1") (pinfunction "1_1") (pintype "passive"))
      (node (ref "C167") (pin "1") (pinfunction "1_1") (pintype "passive"))
      (node (ref "C168") (pin "1") (pinfunction "1_1") (pintype "passive"))
      (node (ref "C169") (pin "1") (pinfunction "1_1") (pintype "passive"))
      (node (ref "C170") (pin "1") (pinfunction "1_1") (pintype "passive"))
      (node (ref "C44") (pin "+") (pinfunction "+_+") (pintype "passive"))
      (node (ref "D20") (pin "K") (pinfunction "K_K") (pintype "passive"))
      (node (ref "J18") (pin "3") (pinfunction "3_3") (pintype "bidirectional"))
      (node (ref "J50") (pin "3") (pinfunction "3_3") (pintype "bidirectional"))
      (node (ref "J50") (pin "4") (pinfunction "4_4") (pintype "bidirectional"))
      (node (ref "Q16") (pin "1_2") (pinfunction "VIN_1_2") (pintype "passive"))
      (node (ref "R160") (pin "2") (pinfunction "2_2") (pintype "passive"))
      (node (ref "R198") (pin "2") (pinfunction "2_2") (pintype "passive"))
      (node (ref "TP61") (pin "TP") (pinfunction "TP_TP") (pintype "input"))
      (node (ref "U8") (pin "15") (pinfunction "PVCC_15") (pintype "power_in"))
      (node (ref "U8") (pin "16") (pinfunction "PVCC_16") (pintype "power_in"))
      (node (ref "U8") (pin "27") (pinfunction "PVCC_27") (pintype "power_in"))
      (node (ref "U8") (pin "28") (pinfunction "PVCC_28") (pintype "power_in"))
    )
    (net (code "139") (name "PGC") (class "Default")
      (node (ref "IC3") (pin "26") (pinfunction "RB6/AN6/PGC2/RP6_26") (pintype "bidirectional"))
      (node (ref "J11") (pin "5") (pinfunction "5_5") (pintype "passive"))
    )
    (net (code "140") (name "PGD") (class "Default")
      (node (ref "IC3") (pin "27") (pinfunction "RB7/AN7/PGD2/RP7_27") (pintype "bidirectional"))
      (node (ref "J11") (pin "4") (pinfunction "4_4") (pintype "passive"))
    )
    (net (code "141") (name "PHOTOCELL") (class "Default")
      (node (ref "R7") (pin "2") (pinfunction "2_2") (pintype "passive"))
      (node (ref "R8") (pin "2") (pinfunction "2_2") (pintype "passive"))
      (node (ref "TP6") (pin "P$1") (pinfunction "TP_P$1") (pintype "passive"))
    )
    (net (code "142") (name "PHOTO_PIN") (class "Default")
      (node (ref "IC3") (pin "24") (pinfunction "RB1/AN1/CN3/PGC1/RP1_24") (pintype "bidirectional"))
      (node (ref "R8") (pin "1") (pinfunction "1_1") (pintype "passive"))
    )
    (net (code "143") (name "PHOTO_PWR") (class "Default")
      (node (ref "IC3") (pin "25") (pinfunction "RB0/AN0/CN2/PGD1/RP0_25") (pintype "bidirectional"))
      (node (ref "R7") (pin "1") (pinfunction "1_1") (pintype "passive"))
    )
    (net (code "144") (name "PIC_INT") (class "Default")
      (node (ref "IC3") (pin "38") (pinfunction "RA1/TCK_38") (pintype "bidirectional"))
      (node (ref "J1") (pin "3") (pinfunction "3_3") (pintype "passive"))
    )
    (net (code "145") (name "RTC_CS") (class "Default")
      (node (ref "IC3") (pin "79") (pinfunction "CN57/RPI42/RD12_79") (pintype "bidirectional"))
      (node (ref "IC7") (pin "6") (pinfunction "CE_6") (pintype "input"))
      (node (ref "R22") (pin "2") (pinfunction "2_2") (pintype "passive"))
    )
    (net (code "146") (name "RTC_INT") (class "Default")
      (node (ref "IC3") (pin "80") (pinfunction "CN19/RD13_80") (pintype "bidirectional"))
      (node (ref "IC7") (pin "5") (pinfunction "/INT_5") (pintype "output"))
    )
    (net (code "147") (name "SBC_5V_VBUS") (class "Default")
      (node (ref "C114") (pin "2") (pinfunction "2_2") (pintype "passive"))
      (node (ref "C115") (pin "2") (pinfunction "2_2") (pintype "passive"))
      (node (ref "IC18") (pin "19") (pinfunction "/RESET_19") (pintype "bidirectional"))
      (node (ref "IC18") (pin "20") (pinfunction "VCC5I_20") (pintype "power_in"))
      (node (ref "J41") (pin "3") (pinfunction "3_3") (pintype "passive"))
      (node (ref "R151") (pin "2") (pinfunction "2_2") (pintype "passive"))
      (node (ref "R152") (pin "2") (pinfunction "2_2") (pintype "passive"))
      (node (ref "X2") (pin "1") (pinfunction "1_1") (pintype "passive"))
    )
    (net (code "148") (name "SBC_LINL") (class "Default")
      (node (ref "C184") (pin "2") (pinfunction "2_2") (pintype "passive"))
      (node (ref "J17") (pin "4") (pinfunction "4_4") (pintype "bidirectional"))
      (node (ref "J47") (pin "6") (pinfunction "6_6") (pintype "passive"))
    )
    (net (code "149") (name "SBC_LINR") (class "Default")
      (node (ref "C183") (pin "2") (pinfunction "2_2") (pintype "passive"))
      (node (ref "J17") (pin "5") (pinfunction "5_5") (pintype "bidirectional"))
      (node (ref "J47") (pin "2") (pinfunction "2_2") (pintype "passive"))
    )
    (net (code "150") (name "SBC_LOUTL") (class "Default")
      (node (ref "C175") (pin "1") (pinfunction "1_1") (pintype "passive"))
      (node (ref "J17") (pin "7") (pinfunction "7_7") (pintype "bidirectional"))
      (node (ref "J47") (pin "5") (pinfunction "5_5") (pintype "passive"))
    )
    (net (code "151") (name "SBC_LOUTR") (class "Default")
      (node (ref "C174") (pin "1") (pinfunction "1_1") (pintype "passive"))
      (node (ref "J17") (pin "8") (pinfunction "8_8") (pintype "bidirectional"))
      (node (ref "J47") (pin "1") (pinfunction "1_1") (pintype "passive"))
    )
    (net (code "152") (name "SBC_USB_B_D_N") (class "Default")
      (node (ref "IC18") (pin "16") (pinfunction "USBDM_16") (pintype "bidirectional"))
      (node (ref "X2") (pin "2") (pinfunction "2_2") (pintype "passive"))
    )
    (net (code "153") (name "SBC_USB_B_D_P") (class "Default")
      (node (ref "IC18") (pin "15") (pinfunction "USBDP_15") (pintype "bidirectional"))
      (node (ref "X2") (pin "3") (pinfunction "3_3") (pintype "passive"))
    )
    (net (code "154") (name "SCL1") (class "Default")
      (node (ref "IC3") (pin "57") (pinfunction "RG2/SCL1/CN83_57") (pintype "bidirectional"))
      (node (ref "IC5") (pin "2") (pinfunction "SCL_2") (pintype "input"))
      (node (ref "IC6") (pin "6") (pinfunction "SCL_6") (pintype "input"))
      (node (ref "J8") (pin "16") (pinfunction "16_16") (pintype "passive"))
      (node (ref "R16") (pin "1") (pinfunction "1_1") (pintype "passive"))
      (node (ref "R32") (pin "1") (pinfunction "1_1") (pintype "passive"))
      (node (ref "U3") (pin "1") (pinfunction "ADDR_1") (pintype "bidirectional"))
      (node (ref "U3") (pin "10") (pinfunction "SCL_10") (pintype "bidirectional"))
    )
    (net (code "155") (name "SCLK1") (class "Default")
      (node (ref "IC3") (pin "77") (pinfunction "CN51/RP23/RD2_77") (pintype "bidirectional"))
      (node (ref "IC7") (pin "10") (pinfunction "SCL_10") (pintype "input"))
      (node (ref "IC8") (pin "6") (pinfunction "C_6") (pintype "input"))
    )
    (net (code "156") (name "SCLK2") (class "Default")
      (node (ref "IC3") (pin "10") (pinfunction "RG6/CN8/RP21_10") (pintype "bidirectional"))
      (node (ref "J1") (pin "5") (pinfunction "5_5") (pintype "passive"))
      (node (ref "J8") (pin "12") (pinfunction "12_12") (pintype "passive"))
      (node (ref "U1") (pin "31") (pinfunction "ASYNC_31") (pintype "bidirectional"))
    )
    (net (code "157") (name "SCLK_SM_B") (class "Default")
      (node (ref "IC3") (pin "8") (pinfunction "RC3/CN47/RPI40_8") (pintype "bidirectional"))
      (node (ref "U1") (pin "26") (pinfunction "SCLK_26") (pintype "bidirectional"))
    )
    (net (code "158") (name "SDA1") (class "Default")
      (node (ref "IC3") (pin "56") (pinfunction "RG3/SDA1/CN84_56") (pintype "bidirectional"))
      (node (ref "IC5") (pin "1") (pinfunction "SDA_1") (pintype "bidirectional"))
      (node (ref "IC6") (pin "5") (pinfunction "SDA_5") (pintype "bidirectional"))
      (node (ref "J8") (pin "15") (pinfunction "15_15") (pintype "passive"))
      (node (ref "R17") (pin "1") (pinfunction "1_1") (pintype "passive"))
      (node (ref "R31") (pin "1") (pinfunction "1_1") (pintype "passive"))
      (node (ref "U3") (pin "9") (pinfunction "SDA_9") (pintype "bidirectional"))
    )
    (net (code "159") (name "SDI1") (class "Default")
      (node (ref "IC3") (pin "72") (pinfunction "CN49/RP11/RD0_72") (pintype "bidirectional"))
      (node (ref "IC7") (pin "8") (pinfunction "SDO_8") (pintype "output"))
      (node (ref "IC8") (pin "2") (pinfunction "Q_2") (pintype "bidirectional"))
    )
    (net (code "160") (name "SDI2") (class "Default")
      (node (ref "IC3") (pin "11") (pinfunction "RG7/CN9/RP26_11") (pintype "bidirectional"))
      (node (ref "J1") (pin "8") (pinfunction "8_8") (pintype "passive"))
      (node (ref "J8") (pin "11") (pinfunction "11_11") (pintype "passive"))
    )
    (net (code "161") (name "SDO1") (class "Default")
      (node (ref "IC3") (pin "76") (pinfunction "CN50/RP24/RD1_76") (pintype "bidirectional"))
      (node (ref "IC7") (pin "9") (pinfunction "SDI_9") (pintype "input"))
      (node (ref "IC8") (pin "5") (pinfunction "D_5") (pintype "input"))
    )
    (net (code "162") (name "SDO2") (class "Default")
      (node (ref "IC3") (pin "12") (pinfunction "CN10/RP19/RG8_12") (pintype "bidirectional"))
      (node (ref "J1") (pin "6") (pinfunction "6_6") (pintype "passive"))
      (node (ref "J8") (pin "14") (pinfunction "14_14") (pintype "passive"))
    )
    (net (code "163") (name "SMB_SCL") (class "Default")
      (node (ref "D31") (pin "6") (pinfunction "AK_6") (pintype "passive"))
      (node (ref "IC3") (pin "66") (pinfunction "RA14/RPI36/CN43_66") (pintype "bidirectional"))
      (node (ref "R190") (pin "1") (pinfunction "1_1") (pintype "passive"))
      (node (ref "R46") (pin "1") (pinfunction "1_1") (pintype "passive"))
    )
    (net (code "164") (name "SMB_SDA") (class "Default")
      (node (ref "D31") (pin "3") (pinfunction "AK_3") (pintype "passive"))
      (node (ref "IC3") (pin "67") (pinfunction "RA15/RPI35/CN44_67") (pintype "bidirectional"))
      (node (ref "R187") (pin "1") (pinfunction "1_1") (pintype "passive"))
      (node (ref "R45") (pin "1") (pinfunction "1_1") (pintype "passive"))
    )
    (net (code "165") (name "SM_C4A") (class "Default")
      (node (ref "J3") (pin "2") (pinfunction "2_2") (pintype "bidirectional"))
      (node (ref "U1") (pin "4") (pinfunction "C4A_4") (pintype "bidirectional"))
      (node (ref "X1") (pin "2") (pinfunction "1_2") (pintype "passive"))
    )
    (net (code "166") (name "SM_C8A") (class "Default")
      (node (ref "J3") (pin "1") (pinfunction "1_1") (pintype "bidirectional"))
      (node (ref "U1") (pin "3") (pinfunction "C8A_3") (pintype "bidirectional"))
      (node (ref "X1") (pin "1") (pinfunction "1_1") (pintype "passive"))
    )
    (net (code "167") (name "SM_CLK_A") (class "Default")
      (node (ref "J3") (pin "4") (pinfunction "4_4") (pintype "bidirectional"))
      (node (ref "U1") (pin "7") (pinfunction "CLKA_7") (pintype "bidirectional"))
      (node (ref "X1") (pin "4") (pinfunction "1_4") (pintype "passive"))
    )
    (net (code "168") (name "SM_DATA") (class "Default")
      (node (ref "IC3") (pin "14") (pinfunction "CN11/RP27/RG9_14") (pintype "bidirectional"))
      (node (ref "U1") (pin "29") (pinfunction "DATA_29") (pintype "bidirectional"))
    )
    (net (code "169") (name "SM_DET_A") (class "Default")
      (node (ref "J3") (pin "10") (pinfunction "10_10") (pintype "bidirectional"))
      (node (ref "U1") (pin "2") (pinfunction "PRESA_2") (pintype "bidirectional"))
      (node (ref "X1") (pin "10") (pinfunction "1_10") (pintype "passive"))
    )
    (net (code "170") (name "SM_IO_A") (class "Default")
      (node (ref "J3") (pin "3") (pinfunction "3_3") (pintype "bidirectional"))
      (node (ref "U1") (pin "5") (pinfunction "IOA_5") (pintype "bidirectional"))
      (node (ref "X1") (pin "3") (pinfunction "1_3") (pintype "passive"))
    )
    (net (code "171") (name "SM_RST") (class "Default")
      (node (ref "IC3") (pin "5") (pinfunction "CN65/SDA3/RE7_5") (pintype "bidirectional"))
      (node (ref "U1") (pin "30") (pinfunction "RIN_30") (pintype "bidirectional"))
    )
    (net (code "172") (name "SM_RST_A") (class "Default")
      (node (ref "J3") (pin "6") (pinfunction "6_6") (pintype "bidirectional"))
      (node (ref "U1") (pin "6") (pinfunction "RSTA_6") (pintype "bidirectional"))
      (node (ref "X1") (pin "6") (pinfunction "1_6") (pintype "passive"))
    )
    (net (code "173") (name "SM_SYNC") (class "Default")
      (node (ref "IC3") (pin "4") (pinfunction "CN64/SCL3/RE6_4") (pintype "bidirectional"))
      (node (ref "U1") (pin "32") (pinfunction "SYNC_32") (pintype "bidirectional"))
    )
    (net (code "174") (name "SM_VCC_A") (class "Default")
      (node (ref "J3") (pin "9") (pinfunction "9_9") (pintype "bidirectional"))
      (node (ref "U1") (pin "8") (pinfunction "VCCA_8") (pintype "bidirectional"))
      (node (ref "X1") (pin "9") (pinfunction "1_9") (pintype "passive"))
    )
    (net (code "175") (name "SPKR1_P") (class "Default")
      (node (ref "C176") (pin "1") (pinfunction "1_1") (pintype "passive"))
      (node (ref "J17") (pin "11") (pinfunction "11_11") (pintype "bidirectional"))
      (node (ref "J4") (pin "1") (pinfunction "1_1") (pintype "passive"))
      (node (ref "L15") (pin "1") (pinfunction "1_1") (pintype "passive"))
    )
    (net (code "176") (name "SPKR_N") (class "Default")
      (node (ref "C179") (pin "1") (pinfunction "1_1") (pintype "passive"))
      (node (ref "J17") (pin "10") (pinfunction "10_10") (pintype "bidirectional"))
      (node (ref "J4") (pin "2") (pinfunction "2_2") (pintype "passive"))
      (node (ref "L16") (pin "1") (pinfunction "1_1") (pintype "passive"))
    )
    (net (code "177") (name "STRIKE_EN") (class "Default")
      (node (ref "IC3") (pin "47") (pinfunction "CN20/RPI43/RD14_47") (pintype "bidirectional"))
      (node (ref "Q18") (pin "2") (pinfunction "G_2") (pintype "passive"))
      (node (ref "R174") (pin "1") (pinfunction "1_1") (pintype "passive"))
      (node (ref "R179") (pin "2") (pinfunction "2_2") (pintype "passive"))
      (node (ref "U7") (pin "15") (pinfunction "EN_15") (pintype "input"))
    )
    (net (code "178") (name "STR_BOOT") (class "Default")
      (node (ref "C140") (pin "1") (pinfunction "1_1") (pintype "passive"))
      (node (ref "U7") (pin "11") (pinfunction "BOOT_11") (pintype "passive"))
    )
    (net (code "179") (name "STR_COMP") (class "Default")
      (node (ref "C146") (pin "1") (pinfunction "1_1") (pintype "passive"))
      (node (ref "R181") (pin "2") (pinfunction "2_2") (pintype "passive"))
      (node (ref "U7") (pin "3") (pinfunction "COMP_3") (pintype "passive"))
    )
    (net (code "180") (name "STR_FB") (class "Default")
      (node (ref "R177") (pin "1") (pinfunction "1_1") (pintype "passive"))
      (node (ref "R185") (pin "2") (pinfunction "2_2") (pintype "passive"))
      (node (ref "U7") (pin "4") (pinfunction "FB_4") (pintype "input"))
    )
    (net (code "181") (name "STR_FEED") (class "Default")
      (node (ref "L12") (pin "2") (pinfunction "2_2") (pintype "passive"))
      (node (ref "R172") (pin "2") (pinfunction "2_2") (pintype "passive"))
      (node (ref "R44") (pin "2") (pinfunction "2_2") (pintype "passive"))
    )
    (net (code "182") (name "STR_HDRV") (class "Default")
      (node (ref "R178") (pin "2") (pinfunction "2_2") (pintype "passive"))
      (node (ref "U7") (pin "13") (pinfunction "HDRV_13") (pintype "output"))
    )
    (net (code "183") (name "STR_HG1") (class "Default")
      (node (ref "Q19") (pin "3") (pinfunction "TG_3") (pintype "passive"))
      (node (ref "R178") (pin "1") (pinfunction "1_1") (pintype "passive"))
    )
    (net (code "184") (name "STR_ISNS+") (class "Default")
      (node (ref "C138") (pin "1") (pinfunction "1_1") (pintype "passive"))
      (node (ref "R171") (pin "1") (pinfunction "1_1") (pintype "passive"))
      (node (ref "U7") (pin "6") (pinfunction "ISNS+_6") (pintype "input"))
    )
    (net (code "185") (name "STR_ISNS-") (class "Default")
      (node (ref "C138") (pin "2") (pinfunction "2_2") (pintype "passive"))
      (node (ref "R172") (pin "1") (pinfunction "1_1") (pintype "passive"))
      (node (ref "U7") (pin "5") (pinfunction "ISNS-_5") (pintype "input"))
    )
    (net (code "186") (name "STR_L") (class "Default")
      (node (ref "D22") (pin "A") (pinfunction "A_A") (pintype "passive"))
      (node (ref "L12") (pin "1") (pinfunction "1_1") (pintype "passive"))
      (node (ref "Q19") (pin "6") (pinfunction "VSW_6") (pintype "passive"))
      (node (ref "Q19") (pin "7") (pinfunction "VSW_7") (pintype "passive"))
      (node (ref "Q19") (pin "8") (pinfunction "VSW_8") (pintype "passive"))
    )
    (net (code "187") (name "STR_LDRV") (class "Default")
      (node (ref "R180") (pin "2") (pinfunction "2_2") (pintype "passive"))
      (node (ref "U7") (pin "8") (pinfunction "LDRV_8") (pintype "output"))
    )
    (net (code "188") (name "STR_LG1") (class "Default")
      (node (ref "Q19") (pin "5") (pinfunction "BG_5") (pintype "passive"))
      (node (ref "R180") (pin "1") (pinfunction "1_1") (pintype "passive"))
    )
    (net (code "189") (name "STR_PG") (class "Default")
      (node (ref "IC3") (pin "74") (pinfunction "RC14/SOSCO/CN0/RPI37_74") (pintype "bidirectional"))
      (node (ref "R186") (pin "1") (pinfunction "1_1") (pintype "passive"))
      (node (ref "U7") (pin "14") (pinfunction "PGOOD_14") (pintype "open_collector"))
    )
    (net (code "190") (name "STR_RC") (class "Default")
      (node (ref "C148") (pin "1") (pinfunction "1_1") (pintype "passive"))
      (node (ref "R181") (pin "1") (pinfunction "1_1") (pintype "passive"))
    )
    (net (code "191") (name "STR_RT") (class "Default")
      (node (ref "R182") (pin "2") (pinfunction "2_2") (pintype "passive"))
      (node (ref "U7") (pin "1") (pinfunction "RT/CLK_1") (pintype "passive"))
    )
    (net (code "192") (name "STR_SS") (class "Default")
      (node (ref "C147") (pin "1") (pinfunction "1_1") (pintype "passive"))
      (node (ref "U7") (pin "2") (pinfunction "SS_2") (pintype "passive"))
    )
    (net (code "193") (name "STR_SW") (class "Default")
      (node (ref "C140") (pin "2") (pinfunction "2_2") (pintype "passive"))
      (node (ref "Q19") (pin "4") (pinfunction "TGR_4") (pintype "passive"))
      (node (ref "U7") (pin "12") (pinfunction "SW_12") (pintype "output"))
    )
    (net (code "194") (name "STR_VCC") (class "Default")
      (node (ref "C141") (pin "1") (pinfunction "1_1") (pintype "passive"))
      (node (ref "U7") (pin "10") (pinfunction "VCC_10") (pintype "output"))
    )
    (net (code "195") (name "U1RX") (class "Default")
      (node (ref "IC18") (pin "1") (pinfunction "TXD_1") (pintype "output"))
      (node (ref "IC3") (pin "70") (pinfunction "CN55/RP3/RD10_70") (pintype "bidirectional"))
      (node (ref "J41") (pin "4") (pinfunction "4_4") (pintype "passive"))
    )
    (net (code "196") (name "U1TX") (class "Default")
      (node (ref "IC18") (pin "5") (pinfunction "RXD_5") (pintype "input"))
      (node (ref "IC3") (pin "71") (pinfunction "CN56/RP12/RD11_71") (pintype "bidirectional"))
      (node (ref "J41") (pin "5") (pinfunction "5_5") (pintype "passive"))
    )
    (net (code "197") (name "U2CTL") (class "Default")
      (node (ref "IC2") (pin "2") (pinfunction "/RE_2") (pintype "input"))
      (node (ref "IC2") (pin "3") (pinfunction "DE_3") (pintype "input"))
      (node (ref "IC3") (pin "19") (pinfunction "RPI34/CN67/RE9_19") (pintype "bidirectional"))
    )
    (net (code "198") (name "U2RX") (class "Default")
      (node (ref "IC2") (pin "1") (pinfunction "R_1") (pintype "output"))
      (node (ref "IC3") (pin "81") (pinfunction "CN13/RP25/RD4_81") (pintype "bidirectional"))
    )
    (net (code "199") (name "U2TX") (class "Default")
      (node (ref "IC2") (pin "4") (pinfunction "D_4") (pintype "input"))
      (node (ref "IC3") (pin "82") (pinfunction "CN14/RP20/RD5_82") (pintype "bidirectional"))
    )
    (net (code "200") (name "U3RX") (class "Default")
      (node (ref "IC3") (pin "23") (pinfunction "RB2/AN2/CN4/RP13_23") (pintype "bidirectional"))
      (node (ref "J2") (pin "3") (pinfunction "3_3") (pintype "passive"))
      (node (ref "JP1") (pin "3") (pinfunction "3_3") (pintype "passive"))
    )
    (net (code "201") (name "U3TX") (class "Default")
      (node (ref "IC3") (pin "33") (pinfunction "RB9/AN9/CN27/RP9_33") (pintype "bidirectional"))
      (node (ref "J2") (pin "4") (pinfunction "4_4") (pintype "passive"))
      (node (ref "JP1") (pin "4") (pinfunction "4_4") (pintype "passive"))
    )
    (net (code "202") (name "US-S_O") (class "Default")
      (node (ref "IC3") (pin "78") (pinfunction "CN52/RP22/RD3_78") (pintype "bidirectional"))
      (node (ref "J18") (pin "11") (pinfunction "11_11") (pintype "bidirectional"))
      (node (ref "J30") (pin "5") (pinfunction "SERIAL_5") (pintype "bidirectional"))
    )
    (net (code "203") (name "USRF_EN") (class "Default")
      (node (ref "IC3") (pin "97") (pinfunction "CN80/RG13_97") (pintype "bidirectional"))
      (node (ref "J18") (pin "12") (pinfunction "12_12") (pintype "bidirectional"))
      (node (ref "J30") (pin "4") (pinfunction "EN_4") (pintype "bidirectional"))
    )
    (net (code "204") (name "VACT") (class "Default")
      (node (ref "C142") (pin "1") (pinfunction "1_1") (pintype "passive"))
      (node (ref "C143") (pin "1") (pinfunction "1_1") (pintype "passive"))
      (node (ref "C144") (pin "1") (pinfunction "1_1") (pintype "passive"))
      (node (ref "C145") (pin "1") (pinfunction "1_1") (pintype "passive"))
      (node (ref "C43") (pin "+") (pinfunction "+_+") (pintype "passive"))
      (node (ref "D21") (pin "+") (pinfunction "C_+") (pintype "passive"))
      (node (ref "D22") (pin "K") (pinfunction "K_K") (pintype "passive"))
      (node (ref "D25") (pin "C") (pinfunction "K_C") (pintype "passive"))
      (node (ref "D26") (pin "C") (pinfunction "K_C") (pintype "passive"))
      (node (ref "J15") (pin "11") (pinfunction "11_11") (pintype "bidirectional"))
      (node (ref "J15") (pin "11A") (pinfunction "11_11A") (pintype "bidirectional"))
      (node (ref "J16") (pin "1") (pinfunction "1_1") (pintype "bidirectional"))
      (node (ref "J16") (pin "1A") (pinfunction "1_1A") (pintype "bidirectional"))
      (node (ref "J18") (pin "1") (pinfunction "1_1") (pintype "bidirectional"))
      (node (ref "Q19") (pin "1_2") (pinfunction "VIN_1_2") (pintype "passive"))
      (node (ref "R175") (pin "2") (pinfunction "2_2") (pintype "passive"))
      (node (ref "R176") (pin "2") (pinfunction "2_2") (pintype "passive"))
      (node (ref "R177") (pin "2") (pinfunction "2_2") (pintype "passive"))
      (node (ref "TP62") (pin "TP") (pinfunction "TP_TP") (pintype "input"))
    )
    (net (code "205") (name "VPS_ON") (class "Default")
      (node (ref "IC3") (pin "100") (pinfunction "CN62/RE4_100") (pintype "bidirectional"))
      (node (ref "Q2") (pin "5") (pinfunction "Q1G_5") (pintype "input"))
      (node (ref "R5") (pin "2") (pinfunction "2_2") (pintype "passive"))
    )
    (net (code "206") (name "VPS_PWR") (class "Default")
      (node (ref "J7") (pin "5") (pinfunction "5_5") (pintype "passive"))
      (node (ref "J9") (pin "5") (pinfunction "5_5") (pintype "passive"))
      (node (ref "Q2") (pin "2") (pinfunction "Q2D1_2") (pintype "bidirectional"))
      (node (ref "Q2") (pin "3") (pinfunction "Q2D2_3") (pintype "bidirectional"))
      (node (ref "R4") (pin "2") (pinfunction "2_2") (pintype "passive"))
    )
    (net (code "207") (name "VPS_SEN") (class "Default")
      (node (ref "IC3") (pin "99") (pinfunction "CN61/RE3_99") (pintype "bidirectional"))
      (node (ref "R4") (pin "1") (pinfunction "1_1") (pintype "passive"))
      (node (ref "R6") (pin "2") (pinfunction "2_2") (pintype "passive"))
    )
    (net (code "208") (name "VREF2.5") (class "Default")
      (node (ref "C4") (pin "1") (pinfunction "1_1") (pintype "passive"))
      (node (ref "IC1") (pin "2") (pinfunction "VOUT_2") (pintype "output"))
      (node (ref "IC3") (pin "29") (pinfunction "RA10/VR+/CN42_29") (pintype "bidirectional"))
      (node (ref "TP1") (pin "P$1") (pinfunction "TP_P$1") (pintype "passive"))
    )
    (net (code "209") (name "VSOLAR") (class "Default")
      (node (ref "J1") (pin "2") (pinfunction "2_2") (pintype "passive"))
    )
    (net (code "210") (name "XB_RTS") (class "Default")
      (node (ref "IC3") (pin "48") (pinfunction "CN21/RP5/RD15_48") (pintype "bidirectional"))
      (node (ref "J2") (pin "7") (pinfunction "7_7") (pintype "passive"))
    )
    (net (code "211") (name "XB_SLEEP") (class "Default")
      (node (ref "IC3") (pin "22") (pinfunction "RB3/AN3/CN5_22") (pintype "bidirectional"))
      (node (ref "J2") (pin "5") (pinfunction "5_5") (pintype "passive"))
      (node (ref "JP1") (pin "5") (pinfunction "5_5") (pintype "passive"))
    )
    (net (code "212") (name "unconnected-(B1-+-Pad+2)") (class "Default")
      (node (ref "B1") (pin "+2") (pinfunction "+_+2") (pintype "passive"))
    )
    (net (code "213") (name "unconnected-(IC3-CN15{slash}RD6-Pad83)") (class "Default")
      (node (ref "IC3") (pin "83") (pinfunction "CN15/RD6_83") (pintype "bidirectional"))
    )
    (net (code "214") (name "unconnected-(IC3-CN17{slash}RP10{slash}RF4-Pad49)") (class "Default")
      (node (ref "IC3") (pin "49") (pinfunction "CN17/RP10/RF4_49") (pintype "bidirectional"))
    )
    (net (code "215") (name "unconnected-(IC3-CN58{slash}RE0-Pad93)") (class "Default")
      (node (ref "IC3") (pin "93") (pinfunction "CN58/RE0_93") (pintype "bidirectional"))
    )
    (net (code "216") (name "unconnected-(IC3-CN60{slash}RE2-Pad98)") (class "Default")
      (node (ref "IC3") (pin "98") (pinfunction "CN60/RE2_98") (pintype "bidirectional"))
    )
    (net (code "217") (name "unconnected-(IC3-CN69{slash}RF1-Pad88)") (class "Default")
      (node (ref "IC3") (pin "88") (pinfunction "CN69/RF1_88") (pintype "bidirectional"))
    )
    (net (code "218") (name "unconnected-(IC3-CN73{slash}RPI44{slash}RF7-Pad54)") (class "Default")
      (node (ref "IC3") (pin "54") (pinfunction "CN73/RPI44/RF7_54") (pintype "bidirectional"))
    )
    (net (code "219") (name "unconnected-(IC3-CN76{slash}RP31{slash}RF13-Pad39)") (class "Default")
      (node (ref "IC3") (pin "39") (pinfunction "CN76/RP31/RF13_39") (pintype "bidirectional"))
    )
    (net (code "220") (name "unconnected-(IC3-RA2{slash}SCL2-Pad58)") (class "Default")
      (node (ref "IC3") (pin "58") (pinfunction "RA2/SCL2_58") (pintype "bidirectional"))
    )
    (net (code "221") (name "unconnected-(IC3-RA3{slash}SDA2-Pad59)") (class "Default")
      (node (ref "IC3") (pin "59") (pinfunction "RA3/SDA2_59") (pintype "bidirectional"))
    )
    (net (code "222") (name "unconnected-(IC3-RB8{slash}AN8{slash}CN26{slash}RP8-Pad32)") (class "Default")
      (node (ref "IC3") (pin "32") (pinfunction "RB8/AN8/CN26/RP8_32") (pintype "bidirectional"))
    )
    (net (code "223") (name "unconnected-(IC3-RB11{slash}AN11{slash}CN29-Pad35)") (class "Default")
      (node (ref "IC3") (pin "35") (pinfunction "RB11/AN11/CN29_35") (pintype "bidirectional"))
    )
    (net (code "224") (name "unconnected-(IC3-RB15{slash}AN15{slash}CN12{slash}RP29-Pad44)") (class "Default")
      (node (ref "IC3") (pin "44") (pinfunction "RB15/AN15/CN12/RP29_44") (pintype "bidirectional"))
    )
    (net (code "225") (name "unconnected-(IC5-OS-Pad3)") (class "Default")
      (node (ref "IC5") (pin "3") (pinfunction "OS_3") (pintype "output"))
    )
    (net (code "226") (name "unconnected-(IC7-CLKOUT-Pad13)") (class "Default")
      (node (ref "IC7") (pin "13") (pinfunction "CLKOUT_13") (pintype "output"))
    )
    (net (code "227") (name "unconnected-(IC7-TEST-Pad4)") (class "Default")
      (node (ref "IC7") (pin "4") (pinfunction "TEST_4") (pintype "output"))
    )
    (net (code "228") (name "unconnected-(IC18-AVCC-NC-Pad24)") (class "Default")
      (node (ref "IC18") (pin "24") (pinfunction "AVCC-NC_24") (pintype "no_connect"))
    )
    (net (code "229") (name "unconnected-(IC18-GPIO2-Pad13)") (class "Default")
      (node (ref "IC18") (pin "13") (pinfunction "GPIO2_13") (pintype "output"))
    )
    (net (code "230") (name "unconnected-(IC18-GPIO3-Pad14)") (class "Default")
      (node (ref "IC18") (pin "14") (pinfunction "GPIO3_14") (pintype "bidirectional"))
    )
    (net (code "231") (name "unconnected-(IC18-OSCI-Pad27)") (class "Default")
      (node (ref "IC18") (pin "27") (pinfunction "OSCI_27") (pintype "bidirectional"))
    )
    (net (code "232") (name "unconnected-(IC18-OSCO-Pad28)") (class "Default")
      (node (ref "IC18") (pin "28") (pinfunction "OSCO_28") (pintype "output"))
    )
    (net (code "233") (name "unconnected-(IC18-VCC3I-NC-Pad8)") (class "Default")
      (node (ref "IC18") (pin "8") (pinfunction "VCC3I-NC_8") (pintype "no_connect"))
    )
    (net (code "234") (name "unconnected-(IC18-{slash}DCD-Pad10)") (class "Default")
      (node (ref "IC18") (pin "10") (pinfunction "/DCD_10") (pintype "bidirectional"))
    )
    (net (code "235") (name "unconnected-(IC18-{slash}DSR-Pad9)") (class "Default")
      (node (ref "IC18") (pin "9") (pinfunction "/DSR_9") (pintype "bidirectional"))
    )
    (net (code "236") (name "unconnected-(IC18-{slash}DTR-Pad2)") (class "Default")
      (node (ref "IC18") (pin "2") (pinfunction "/DTR_2") (pintype "output"))
    )
    (net (code "237") (name "unconnected-(IC18-{slash}RI-Pad6)") (class "Default")
      (node (ref "IC18") (pin "6") (pinfunction "/RI_6") (pintype "bidirectional"))
    )
    (net (code "238") (name "unconnected-(IC18-{slash}SLEEP-Pad12)") (class "Default")
      (node (ref "IC18") (pin "12") (pinfunction "/SLEEP_12") (pintype "bidirectional"))
    )
    (net (code "239") (name "unconnected-(J8-Pad1)") (class "Default")
      (node (ref "J8") (pin "1") (pinfunction "1_1") (pintype "passive"))
    )
    (net (code "240") (name "unconnected-(J8-Pad2)") (class "Default")
      (node (ref "J8") (pin "2") (pinfunction "2_2") (pintype "passive"))
    )
    (net (code "241") (name "unconnected-(J8-Pad3)") (class "Default")
      (node (ref "J8") (pin "3") (pinfunction "3_3") (pintype "passive"))
    )
    (net (code "242") (name "unconnected-(J8-Pad4)") (class "Default")
      (node (ref "J8") (pin "4") (pinfunction "4_4") (pintype "passive"))
    )
    (net (code "243") (name "unconnected-(J8-Pad5)") (class "Default")
      (node (ref "J8") (pin "5") (pinfunction "5_5") (pintype "passive"))
    )
    (net (code "244") (name "unconnected-(J8-Pad6)") (class "Default")
      (node (ref "J8") (pin "6") (pinfunction "6_6") (pintype "passive"))
    )
    (net (code "245") (name "unconnected-(J8-Pad7)") (class "Default")
      (node (ref "J8") (pin "7") (pinfunction "7_7") (pintype "passive"))
    )
    (net (code "246") (name "unconnected-(J8-Pad8)") (class "Default")
      (node (ref "J8") (pin "8") (pinfunction "8_8") (pintype "passive"))
    )
    (net (code "247") (name "unconnected-(J10-PadC4)") (class "Default")
      (node (ref "J10") (pin "C4") (pinfunction "C4_C4") (pintype "bidirectional"))
    )
    (net (code "248") (name "unconnected-(J10-PadC6)") (class "Default")
      (node (ref "J10") (pin "C6") (pinfunction "C6_C6") (pintype "bidirectional"))
    )
    (net (code "249") (name "unconnected-(J10-PadC8)") (class "Default")
      (node (ref "J10") (pin "C8") (pinfunction "C8_C8") (pintype "bidirectional"))
    )
    (net (code "250") (name "unconnected-(J30-AN{slash}O-Pad3)") (class "Default")
      (node (ref "J30") (pin "3") (pinfunction "AN/O_3") (pintype "bidirectional"))
    )
    (net (code "251") (name "unconnected-(J30-PWM-Pad2)") (class "Default")
      (node (ref "J30") (pin "2") (pinfunction "PWM_2") (pintype "bidirectional"))
    )
    (net (code "252") (name "unconnected-(J30-TEMP(NC)-Pad1)") (class "Default")
      (node (ref "J30") (pin "1") (pinfunction "TEMP(NC)_1") (pintype "bidirectional"))
    )
    (net (code "253") (name "unconnected-(J47-Pad7)") (class "Default")
      (node (ref "J47") (pin "7") (pinfunction "7_7") (pintype "passive"))
    )
    (net (code "254") (name "unconnected-(J47-Pad8)") (class "Default")
      (node (ref "J47") (pin "8") (pinfunction "8_8") (pintype "passive"))
    )
    (net (code "255") (name "unconnected-(J47-Pad9)") (class "Default")
      (node (ref "J47") (pin "9") (pinfunction "9_9") (pintype "passive"))
    )
    (net (code "256") (name "unconnected-(J47-Pad10)") (class "Default")
      (node (ref "J47") (pin "10") (pinfunction "10_10") (pintype "passive"))
    )
    (net (code "257") (name "unconnected-(JP1-Pad8)") (class "Default")
      (node (ref "JP1") (pin "8") (pinfunction "8_8") (pintype "passive"))
    )
    (net (code "258") (name "unconnected-(Q3-Pad4)") (class "Default")
      (node (ref "Q3") (pin "4") (pinfunction "4_4") (pintype "passive"))
    )
    (net (code "259") (name "unconnected-(U1-NC-Pad16)") (class "Default")
      (node (ref "U1") (pin "16") (pinfunction "NC_16") (pintype "bidirectional"))
    )
    (net (code "260") (name "unconnected-(U3-ALERT{slash}RDY-Pad2)") (class "Default")
      (node (ref "U3") (pin "2") (pinfunction "ALERT/RDY_2") (pintype "bidirectional"))
    )
    (net (code "261") (name "unconnected-(U8-NC-Pad13)") (class "Default")
      (node (ref "U8") (pin "13") (pinfunction "NC_13") (pintype "no_connect"))
    )
    (net (code "262") (name "unconnected-(X1F-1-Pad5)") (class "Default")
      (node (ref "X1") (pin "5") (pinfunction "1_5") (pintype "passive"))
    )
    (net (code "263") (name "{slash}3.3V1_ON") (class "Default")
      (node (ref "IC3") (pin "95") (pinfunction "CN81/RG14_95") (pintype "bidirectional"))
      (node (ref "Q7") (pin "2") (pinfunction "G_2") (pintype "passive"))
    )
    (net (code "264") (name "{slash}3.3V2_ON") (class "Default")
      (node (ref "IC3") (pin "94") (pinfunction "CN59/RE1_94") (pintype "bidirectional"))
      (node (ref "Q7") (pin "5") (pinfunction "G_5") (pintype "passive"))
    )
    (net (code "265") (name "{slash}3.3V3_ON") (class "Default")
      (node (ref "IC3") (pin "61") (pinfunction "RA5/TDO/CN38_61") (pintype "bidirectional"))
    )
    (net (code "266") (name "{slash}CL_CS1") (class "Default")
      (node (ref "IC3") (pin "1") (pinfunction "CN82/RG15_1") (pintype "bidirectional"))
      (node (ref "TP10") (pin "P$1") (pinfunction "TP_P$1") (pintype "passive"))
    )
    (net (code "267") (name "{slash}CL_CS2") (class "Default")
      (node (ref "IC3") (pin "17") (pinfunction "RA0/TMS_17") (pintype "bidirectional"))
      (node (ref "J1") (pin "7") (pinfunction "7_7") (pintype "passive"))
    )
    (net (code "268") (name "{slash}CTS") (class "Default")
      (node (ref "IC18") (pin "11") (pinfunction "/CTS_11") (pintype "bidirectional"))
      (node (ref "J41") (pin "2") (pinfunction "2_2") (pintype "passive"))
    )
    (net (code "269") (name "{slash}FMEM1_CS") (class "Default")
      (node (ref "IC3") (pin "28") (pinfunction "RA9/VR-/CN41_28") (pintype "bidirectional"))
      (node (ref "IC8") (pin "1") (pinfunction "/S_1") (pintype "input"))
      (node (ref "R24") (pin "2") (pinfunction "2_2") (pintype "passive"))
    )
    (net (code "270") (name "{slash}MCLR") (class "Default")
      (node (ref "IC3") (pin "13") (pinfunction "MCLR_13") (pintype "input"))
      (node (ref "IC4") (pin "4") (pinfunction "GP2/T0CK_4") (pintype "bidirectional"))
      (node (ref "J11") (pin "1") (pinfunction "1_1") (pintype "passive"))
      (node (ref "R14") (pin "1") (pinfunction "1_1") (pintype "passive"))
    )
    (net (code "271") (name "{slash}MCLR2") (class "Default")
      (node (ref "IC4") (pin "6") (pinfunction "GP3/MCLR_6") (pintype "bidirectional"))
      (node (ref "J12") (pin "1") (pinfunction "1_1") (pintype "passive"))
    )
    (net (code "272") (name "{slash}RAM_CS") (class "Default")
      (node (ref "IC3") (pin "3") (pinfunction "CN63/RE5_3") (pintype "bidirectional"))
      (node (ref "J8") (pin "13") (pinfunction "13_13") (pintype "passive"))
    )
    (net (code "273") (name "{slash}RTS") (class "Default")
      (node (ref "IC18") (pin "3") (pinfunction "/RTS_3") (pintype "output"))
      (node (ref "J41") (pin "6") (pinfunction "6_6") (pintype "passive"))
    )
    (net (code "274") (name "{slash}SM_FAULT") (class "Default")
      (node (ref "IC3") (pin "21") (pinfunction "RB4/AN4/CN6/RP28_21") (pintype "bidirectional"))
      (node (ref "U1") (pin "24") (pinfunction "-FAULT_24") (pintype "bidirectional"))
    )
    (net (code "275") (name "{slash}XB_RESET") (class "Default")
      (node (ref "IC3") (pin "18") (pinfunction "RPI33/CN66/RE8_18") (pintype "bidirectional"))
      (node (ref "J2") (pin "6") (pinfunction "6_6") (pintype "passive"))
      (node (ref "JP1") (pin "7") (pinfunction "7_7") (pintype "passive"))
    )
  )
)
